# ETEST01.net
KiCad netlist of a schematic drawn in EAGLE
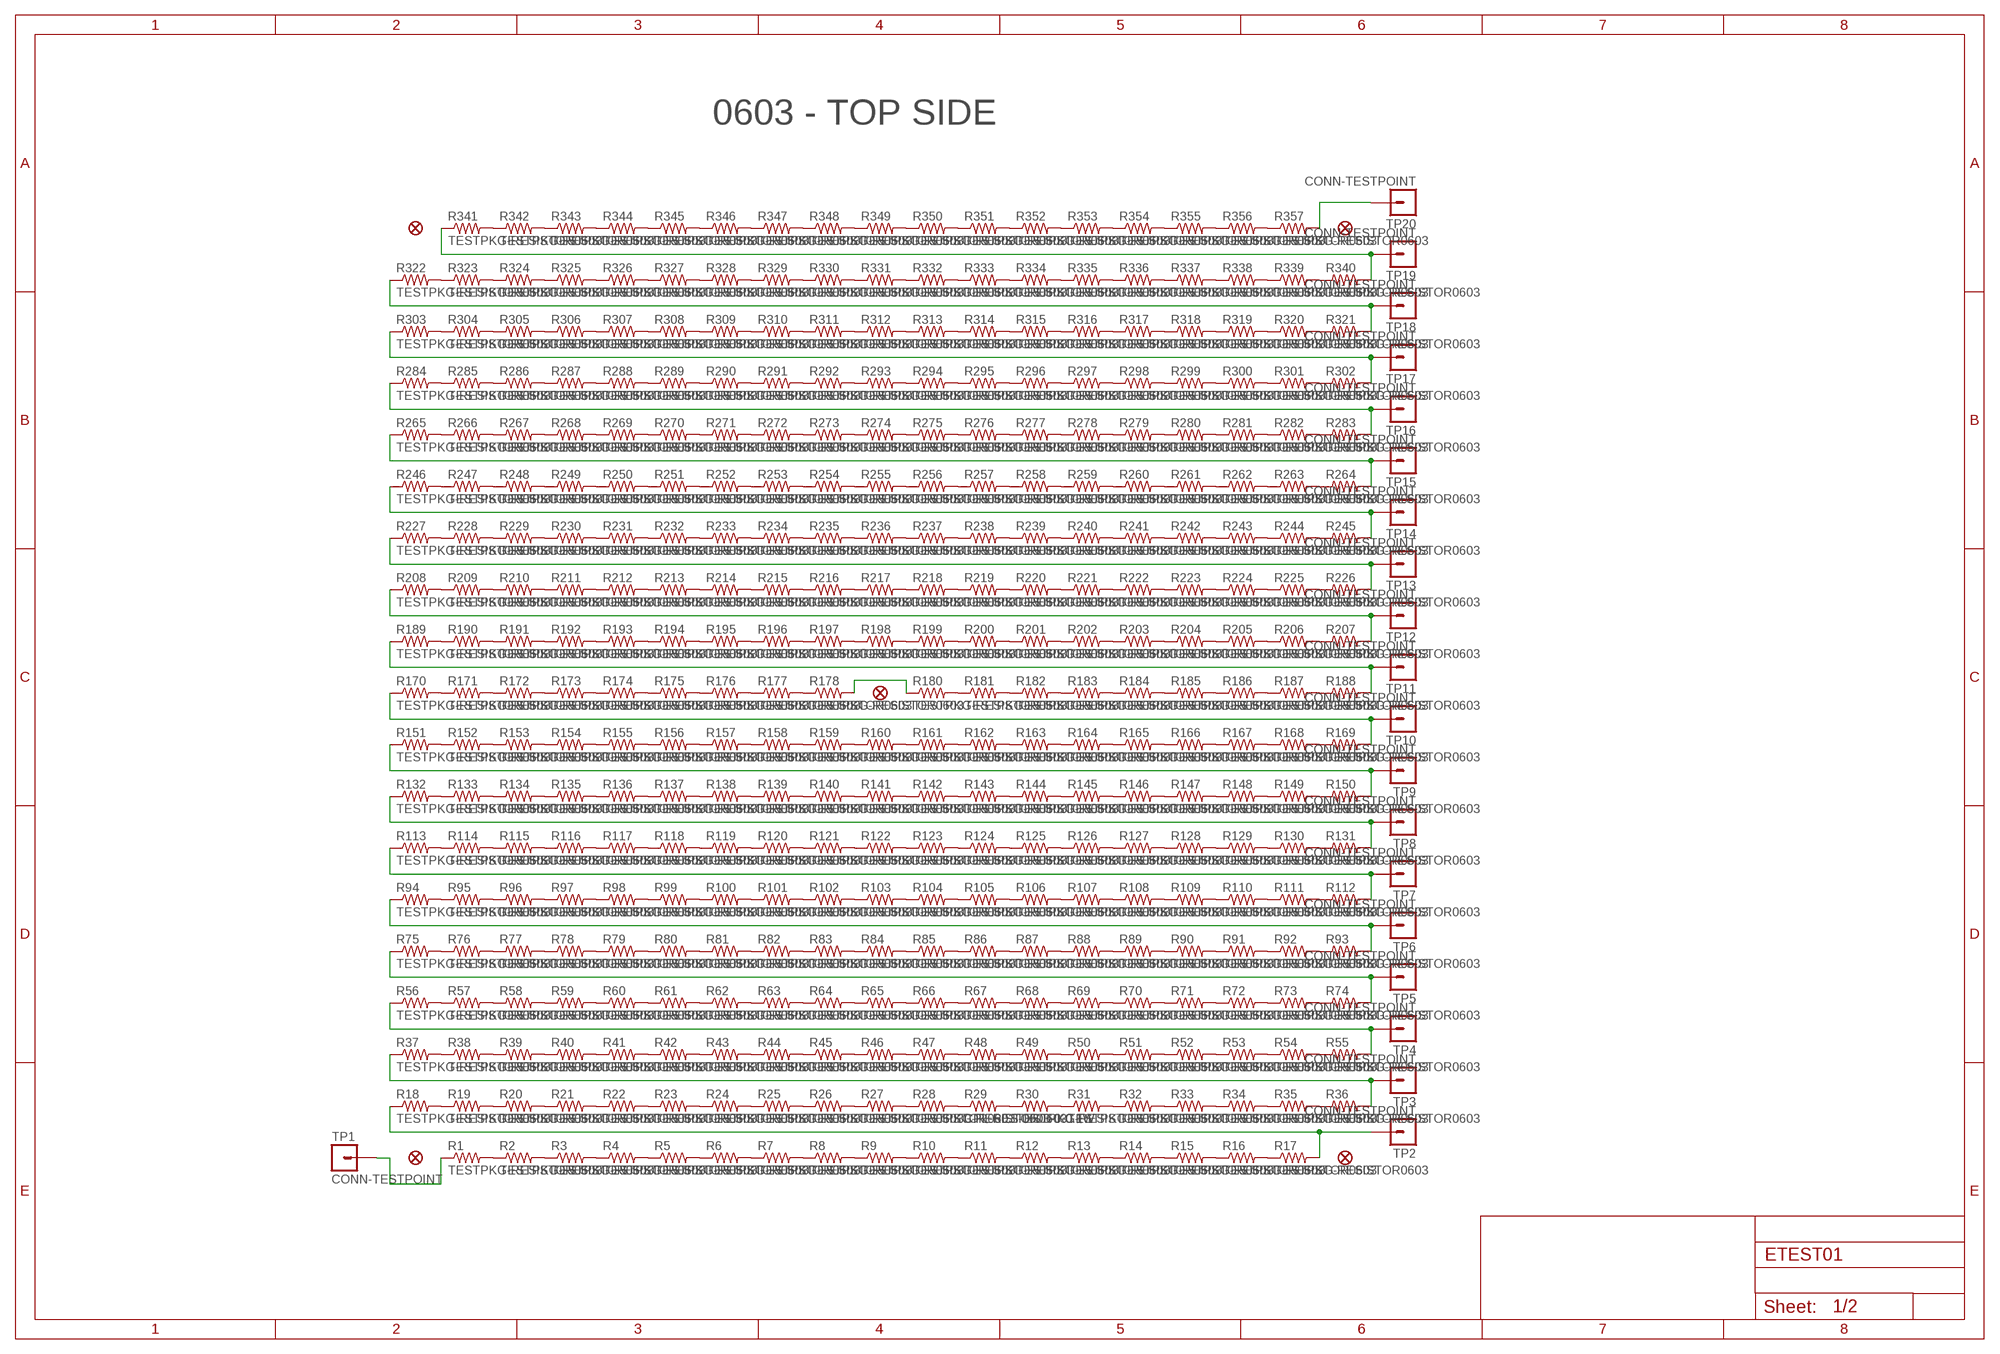
[diagram p0: schematic, sheet 1]
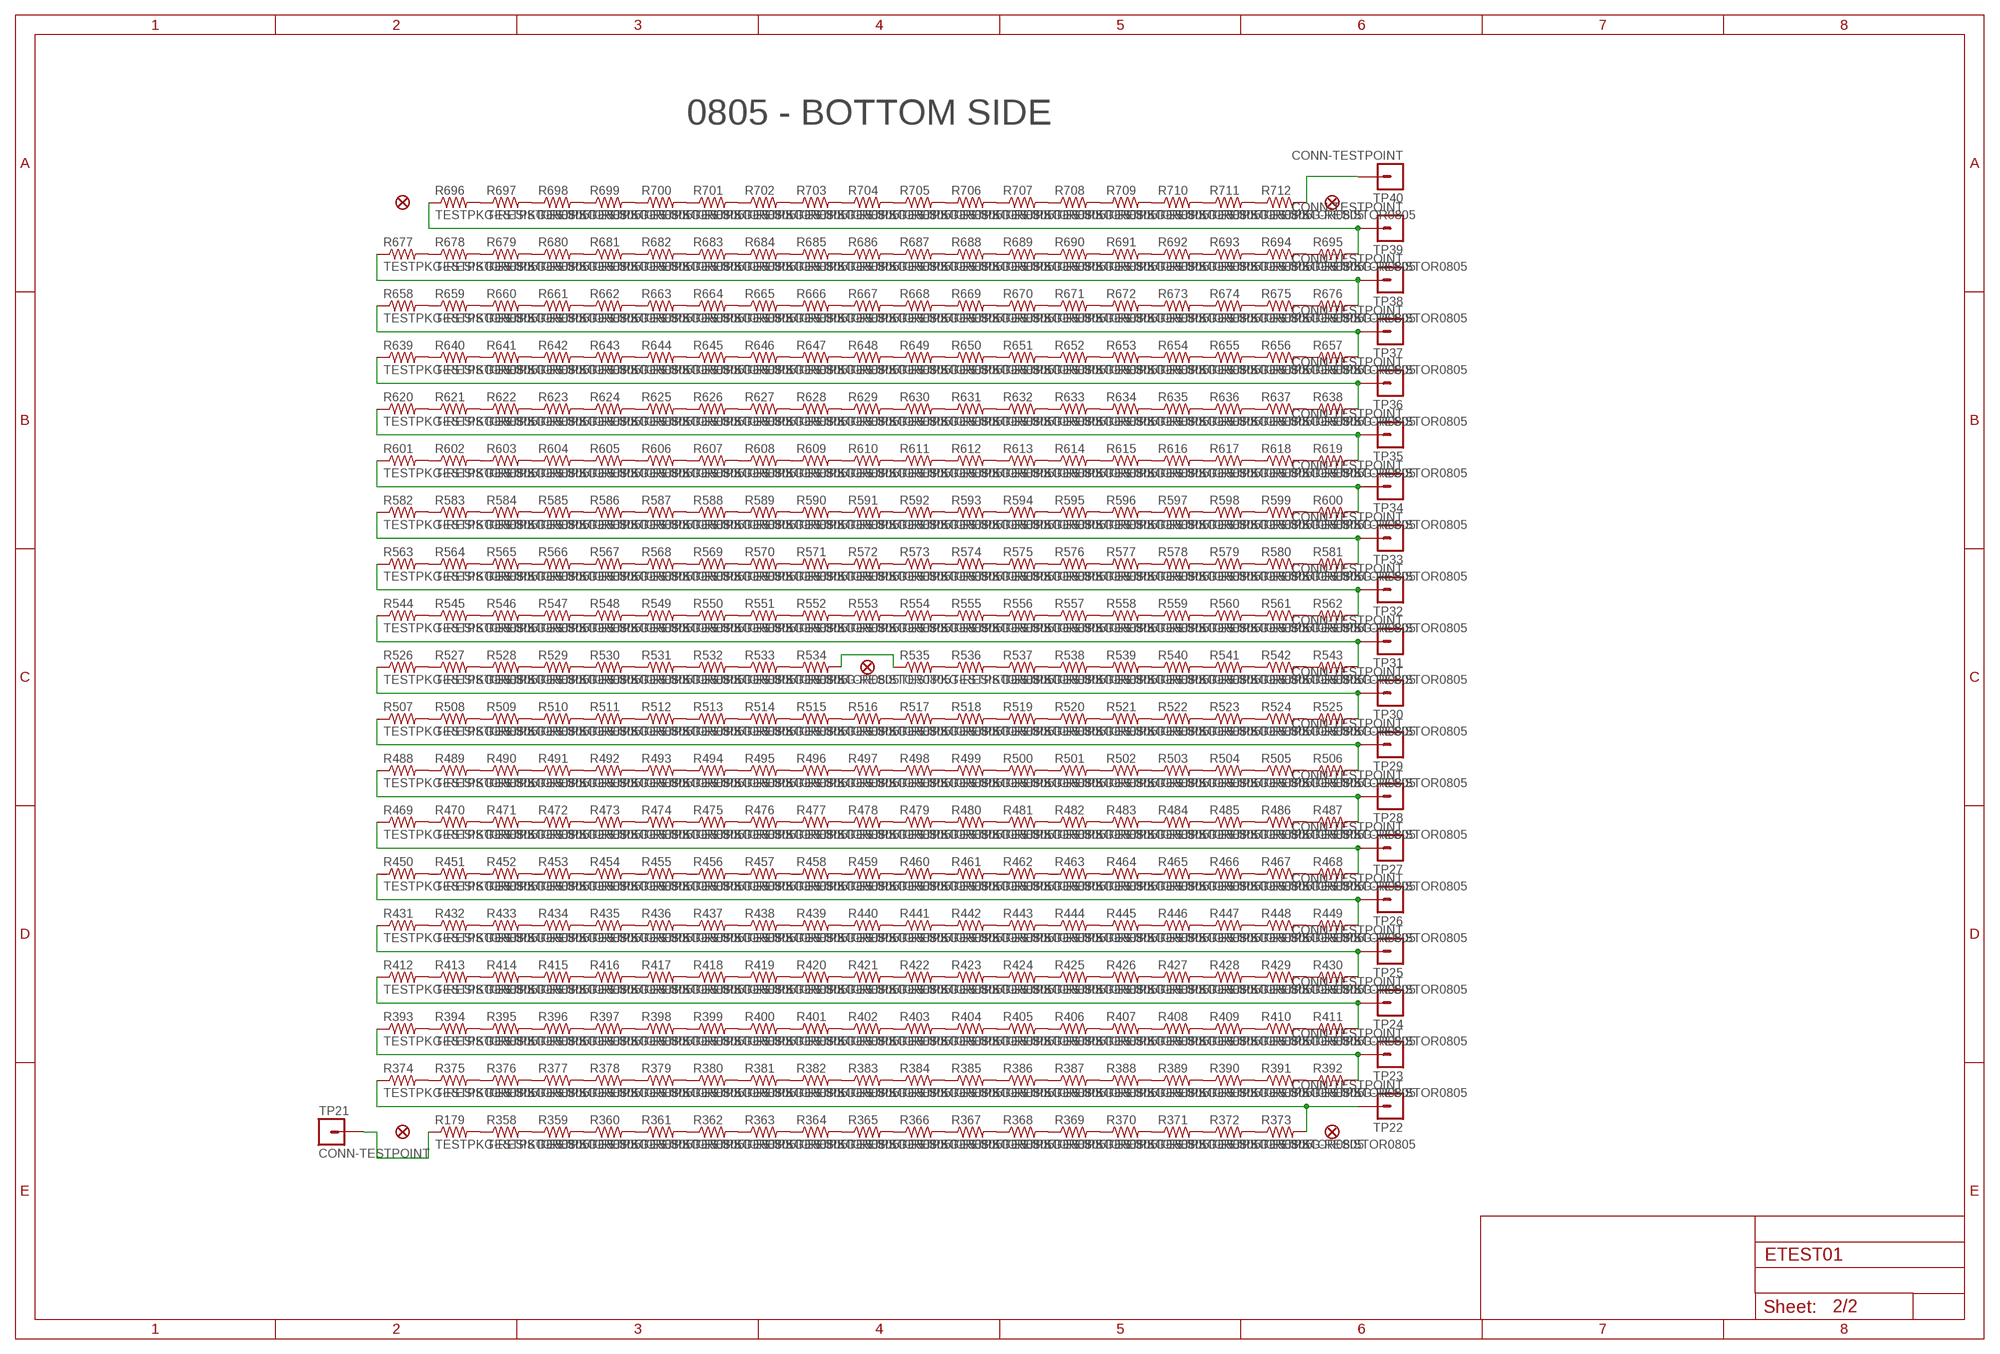
[diagram p1: schematic, sheet 2]

(export (version "E")
  (design (tool "Eeschema 10.0.6"))
  (components
    (comp (ref "FID1")
      (value "FIDUCIAL")
      (footprint "eagle-import:FIDUCIAL")
      (libsource (lib "eagle-import") (part "FIDUCIAL"))
    )
    (comp (ref "FID2")
      (value "FIDUCIAL")
      (footprint "eagle-import:FIDUCIAL")
      (libsource (lib "eagle-import") (part "FIDUCIAL"))
    )
    (comp (ref "FID3")
      (value "FIDUCIAL")
      (footprint "eagle-import:FIDUCIAL")
      (libsource (lib "eagle-import") (part "FIDUCIAL"))
    )
    (comp (ref "FID4")
      (value "FIDUCIAL")
      (footprint "eagle-import:FIDUCIAL")
      (libsource (lib "eagle-import") (part "FIDUCIAL"))
    )
    (comp (ref "FID5")
      (value "FIDUCIAL")
      (footprint "eagle-import:FIDUCIAL")
      (libsource (lib "eagle-import") (part "FIDUCIAL"))
    )
    (comp (ref "R1")
      (value "TESTPKG-RESISTOR0603")
      (footprint "eagle-import:TESTPKG-R0603")
      (libsource (lib "eagle-import") (part "TESTPKG-RESISTOR0603"))
    )
    (comp (ref "R2")
      (value "TESTPKG-RESISTOR0603")
      (footprint "eagle-import:TESTPKG-R0603")
      (libsource (lib "eagle-import") (part "TESTPKG-RESISTOR0603"))
    )
    (comp (ref "R3")
      (value "TESTPKG-RESISTOR0603")
      (footprint "eagle-import:TESTPKG-R0603")
      (libsource (lib "eagle-import") (part "TESTPKG-RESISTOR0603"))
    )
    (comp (ref "R4")
      (value "TESTPKG-RESISTOR0603")
      (footprint "eagle-import:TESTPKG-R0603")
      (libsource (lib "eagle-import") (part "TESTPKG-RESISTOR0603"))
    )
    (comp (ref "R5")
      (value "TESTPKG-RESISTOR0603")
      (footprint "eagle-import:TESTPKG-R0603")
      (libsource (lib "eagle-import") (part "TESTPKG-RESISTOR0603"))
    )
    (comp (ref "R6")
      (value "TESTPKG-RESISTOR0603")
      (footprint "eagle-import:TESTPKG-R0603")
      (libsource (lib "eagle-import") (part "TESTPKG-RESISTOR0603"))
    )
    (comp (ref "R7")
      (value "TESTPKG-RESISTOR0603")
      (footprint "eagle-import:TESTPKG-R0603")
      (libsource (lib "eagle-import") (part "TESTPKG-RESISTOR0603"))
    )
    (comp (ref "R8")
      (value "TESTPKG-RESISTOR0603")
      (footprint "eagle-import:TESTPKG-R0603")
      (libsource (lib "eagle-import") (part "TESTPKG-RESISTOR0603"))
    )
    (comp (ref "R9")
      (value "TESTPKG-RESISTOR0603")
      (footprint "eagle-import:TESTPKG-R0603")
      (libsource (lib "eagle-import") (part "TESTPKG-RESISTOR0603"))
    )
    (comp (ref "R10")
      (value "TESTPKG-RESISTOR0603")
      (footprint "eagle-import:TESTPKG-R0603")
      (libsource (lib "eagle-import") (part "TESTPKG-RESISTOR0603"))
    )
    (comp (ref "R11")
      (value "TESTPKG-RESISTOR0603")
      (footprint "eagle-import:TESTPKG-R0603")
      (libsource (lib "eagle-import") (part "TESTPKG-RESISTOR0603"))
    )
    (comp (ref "R12")
      (value "TESTPKG-RESISTOR0603")
      (footprint "eagle-import:TESTPKG-R0603")
      (libsource (lib "eagle-import") (part "TESTPKG-RESISTOR0603"))
    )
    (comp (ref "R13")
      (value "TESTPKG-RESISTOR0603")
      (footprint "eagle-import:TESTPKG-R0603")
      (libsource (lib "eagle-import") (part "TESTPKG-RESISTOR0603"))
    )
    (comp (ref "R14")
      (value "TESTPKG-RESISTOR0603")
      (footprint "eagle-import:TESTPKG-R0603")
      (libsource (lib "eagle-import") (part "TESTPKG-RESISTOR0603"))
    )
    (comp (ref "R15")
      (value "TESTPKG-RESISTOR0603")
      (footprint "eagle-import:TESTPKG-R0603")
      (libsource (lib "eagle-import") (part "TESTPKG-RESISTOR0603"))
    )
    (comp (ref "R16")
      (value "TESTPKG-RESISTOR0603")
      (footprint "eagle-import:TESTPKG-R0603")
      (libsource (lib "eagle-import") (part "TESTPKG-RESISTOR0603"))
    )
    (comp (ref "R17")
      (value "TESTPKG-RESISTOR0603")
      (footprint "eagle-import:TESTPKG-R0603")
      (libsource (lib "eagle-import") (part "TESTPKG-RESISTOR0603"))
    )
    (comp (ref "R18")
      (value "TESTPKG-RESISTOR0603")
      (footprint "eagle-import:TESTPKG-R0603")
      (libsource (lib "eagle-import") (part "TESTPKG-RESISTOR0603"))
    )
    (comp (ref "R19")
      (value "TESTPKG-RESISTOR0603")
      (footprint "eagle-import:TESTPKG-R0603")
      (libsource (lib "eagle-import") (part "TESTPKG-RESISTOR0603"))
    )
    (comp (ref "R20")
      (value "TESTPKG-RESISTOR0603")
      (footprint "eagle-import:TESTPKG-R0603")
      (libsource (lib "eagle-import") (part "TESTPKG-RESISTOR0603"))
    )
    (comp (ref "R21")
      (value "TESTPKG-RESISTOR0603")
      (footprint "eagle-import:TESTPKG-R0603")
      (libsource (lib "eagle-import") (part "TESTPKG-RESISTOR0603"))
    )
    (comp (ref "R22")
      (value "TESTPKG-RESISTOR0603")
      (footprint "eagle-import:TESTPKG-R0603")
      (libsource (lib "eagle-import") (part "TESTPKG-RESISTOR0603"))
    )
    (comp (ref "R23")
      (value "TESTPKG-RESISTOR0603")
      (footprint "eagle-import:TESTPKG-R0603")
      (libsource (lib "eagle-import") (part "TESTPKG-RESISTOR0603"))
    )
    (comp (ref "R24")
      (value "TESTPKG-RESISTOR0603")
      (footprint "eagle-import:TESTPKG-R0603")
      (libsource (lib "eagle-import") (part "TESTPKG-RESISTOR0603"))
    )
    (comp (ref "R25")
      (value "TESTPKG-RESISTOR0603")
      (footprint "eagle-import:TESTPKG-R0603")
      (libsource (lib "eagle-import") (part "TESTPKG-RESISTOR0603"))
    )
    (comp (ref "R26")
      (value "TESTPKG-RESISTOR0603")
      (footprint "eagle-import:TESTPKG-R0603")
      (libsource (lib "eagle-import") (part "TESTPKG-RESISTOR0603"))
    )
    (comp (ref "R27")
      (value "TESTPKG-RESISTOR0603")
      (footprint "eagle-import:TESTPKG-R0603")
      (libsource (lib "eagle-import") (part "TESTPKG-RESISTOR0603"))
    )
    (comp (ref "R28")
      (value "TESTPKG-RESISTOR0603")
      (footprint "eagle-import:TESTPKG-R0603")
      (libsource (lib "eagle-import") (part "TESTPKG-RESISTOR0603"))
    )
    (comp (ref "R29")
      (value "CPL-RES-0603-0-0.1W")
      (footprint "eagle-import:R0603")
      (libsource (lib "eagle-import") (part "CPL-RES-0603-0-0.1W"))
    )
    (comp (ref "R30")
      (value "TESTPKG-RESISTOR0603")
      (footprint "eagle-import:TESTPKG-R0603")
      (libsource (lib "eagle-import") (part "TESTPKG-RESISTOR0603"))
    )
    (comp (ref "R31")
      (value "TESTPKG-RESISTOR0603")
      (footprint "eagle-import:TESTPKG-R0603")
      (libsource (lib "eagle-import") (part "TESTPKG-RESISTOR0603"))
    )
    (comp (ref "R32")
      (value "TESTPKG-RESISTOR0603")
      (footprint "eagle-import:TESTPKG-R0603")
      (libsource (lib "eagle-import") (part "TESTPKG-RESISTOR0603"))
    )
    (comp (ref "R33")
      (value "TESTPKG-RESISTOR0603")
      (footprint "eagle-import:TESTPKG-R0603")
      (libsource (lib "eagle-import") (part "TESTPKG-RESISTOR0603"))
    )
    (comp (ref "R34")
      (value "TESTPKG-RESISTOR0603")
      (footprint "eagle-import:TESTPKG-R0603")
      (libsource (lib "eagle-import") (part "TESTPKG-RESISTOR0603"))
    )
    (comp (ref "R35")
      (value "TESTPKG-RESISTOR0603")
      (footprint "eagle-import:TESTPKG-R0603")
      (libsource (lib "eagle-import") (part "TESTPKG-RESISTOR0603"))
    )
    (comp (ref "R36")
      (value "TESTPKG-RESISTOR0603")
      (footprint "eagle-import:TESTPKG-R0603")
      (libsource (lib "eagle-import") (part "TESTPKG-RESISTOR0603"))
    )
    (comp (ref "R37")
      (value "TESTPKG-RESISTOR0603")
      (footprint "eagle-import:TESTPKG-R0603")
      (libsource (lib "eagle-import") (part "TESTPKG-RESISTOR0603"))
    )
    (comp (ref "R38")
      (value "TESTPKG-RESISTOR0603")
      (footprint "eagle-import:TESTPKG-R0603")
      (libsource (lib "eagle-import") (part "TESTPKG-RESISTOR0603"))
    )
    (comp (ref "R39")
      (value "TESTPKG-RESISTOR0603")
      (footprint "eagle-import:TESTPKG-R0603")
      (libsource (lib "eagle-import") (part "TESTPKG-RESISTOR0603"))
    )
    (comp (ref "R40")
      (value "TESTPKG-RESISTOR0603")
      (footprint "eagle-import:TESTPKG-R0603")
      (libsource (lib "eagle-import") (part "TESTPKG-RESISTOR0603"))
    )
    (comp (ref "R41")
      (value "TESTPKG-RESISTOR0603")
      (footprint "eagle-import:TESTPKG-R0603")
      (libsource (lib "eagle-import") (part "TESTPKG-RESISTOR0603"))
    )
    (comp (ref "R42")
      (value "TESTPKG-RESISTOR0603")
      (footprint "eagle-import:TESTPKG-R0603")
      (libsource (lib "eagle-import") (part "TESTPKG-RESISTOR0603"))
    )
    (comp (ref "R43")
      (value "TESTPKG-RESISTOR0603")
      (footprint "eagle-import:TESTPKG-R0603")
      (libsource (lib "eagle-import") (part "TESTPKG-RESISTOR0603"))
    )
    (comp (ref "R44")
      (value "TESTPKG-RESISTOR0603")
      (footprint "eagle-import:TESTPKG-R0603")
      (libsource (lib "eagle-import") (part "TESTPKG-RESISTOR0603"))
    )
    (comp (ref "R45")
      (value "TESTPKG-RESISTOR0603")
      (footprint "eagle-import:TESTPKG-R0603")
      (libsource (lib "eagle-import") (part "TESTPKG-RESISTOR0603"))
    )
    (comp (ref "R46")
      (value "TESTPKG-RESISTOR0603")
      (footprint "eagle-import:TESTPKG-R0603")
      (libsource (lib "eagle-import") (part "TESTPKG-RESISTOR0603"))
    )
    (comp (ref "R47")
      (value "TESTPKG-RESISTOR0603")
      (footprint "eagle-import:TESTPKG-R0603")
      (libsource (lib "eagle-import") (part "TESTPKG-RESISTOR0603"))
    )
    (comp (ref "R48")
      (value "TESTPKG-RESISTOR0603")
      (footprint "eagle-import:TESTPKG-R0603")
      (libsource (lib "eagle-import") (part "TESTPKG-RESISTOR0603"))
    )
    (comp (ref "R49")
      (value "TESTPKG-RESISTOR0603")
      (footprint "eagle-import:TESTPKG-R0603")
      (libsource (lib "eagle-import") (part "TESTPKG-RESISTOR0603"))
    )
    (comp (ref "R50")
      (value "TESTPKG-RESISTOR0603")
      (footprint "eagle-import:TESTPKG-R0603")
      (libsource (lib "eagle-import") (part "TESTPKG-RESISTOR0603"))
    )
    (comp (ref "R51")
      (value "TESTPKG-RESISTOR0603")
      (footprint "eagle-import:TESTPKG-R0603")
      (libsource (lib "eagle-import") (part "TESTPKG-RESISTOR0603"))
    )
    (comp (ref "R52")
      (value "TESTPKG-RESISTOR0603")
      (footprint "eagle-import:TESTPKG-R0603")
      (libsource (lib "eagle-import") (part "TESTPKG-RESISTOR0603"))
    )
    (comp (ref "R53")
      (value "TESTPKG-RESISTOR0603")
      (footprint "eagle-import:TESTPKG-R0603")
      (libsource (lib "eagle-import") (part "TESTPKG-RESISTOR0603"))
    )
    (comp (ref "R54")
      (value "TESTPKG-RESISTOR0603")
      (footprint "eagle-import:TESTPKG-R0603")
      (libsource (lib "eagle-import") (part "TESTPKG-RESISTOR0603"))
    )
    (comp (ref "R55")
      (value "TESTPKG-RESISTOR0603")
      (footprint "eagle-import:TESTPKG-R0603")
      (libsource (lib "eagle-import") (part "TESTPKG-RESISTOR0603"))
    )
    (comp (ref "R56")
      (value "TESTPKG-RESISTOR0603")
      (footprint "eagle-import:TESTPKG-R0603")
      (libsource (lib "eagle-import") (part "TESTPKG-RESISTOR0603"))
    )
    (comp (ref "R57")
      (value "TESTPKG-RESISTOR0603")
      (footprint "eagle-import:TESTPKG-R0603")
      (libsource (lib "eagle-import") (part "TESTPKG-RESISTOR0603"))
    )
    (comp (ref "R58")
      (value "TESTPKG-RESISTOR0603")
      (footprint "eagle-import:TESTPKG-R0603")
      (libsource (lib "eagle-import") (part "TESTPKG-RESISTOR0603"))
    )
    (comp (ref "R59")
      (value "TESTPKG-RESISTOR0603")
      (footprint "eagle-import:TESTPKG-R0603")
      (libsource (lib "eagle-import") (part "TESTPKG-RESISTOR0603"))
    )
    (comp (ref "R60")
      (value "TESTPKG-RESISTOR0603")
      (footprint "eagle-import:TESTPKG-R0603")
      (libsource (lib "eagle-import") (part "TESTPKG-RESISTOR0603"))
    )
    (comp (ref "R61")
      (value "TESTPKG-RESISTOR0603")
      (footprint "eagle-import:TESTPKG-R0603")
      (libsource (lib "eagle-import") (part "TESTPKG-RESISTOR0603"))
    )
    (comp (ref "R62")
      (value "TESTPKG-RESISTOR0603")
      (footprint "eagle-import:TESTPKG-R0603")
      (libsource (lib "eagle-import") (part "TESTPKG-RESISTOR0603"))
    )
    (comp (ref "R63")
      (value "TESTPKG-RESISTOR0603")
      (footprint "eagle-import:TESTPKG-R0603")
      (libsource (lib "eagle-import") (part "TESTPKG-RESISTOR0603"))
    )
    (comp (ref "R64")
      (value "TESTPKG-RESISTOR0603")
      (footprint "eagle-import:TESTPKG-R0603")
      (libsource (lib "eagle-import") (part "TESTPKG-RESISTOR0603"))
    )
    (comp (ref "R65")
      (value "TESTPKG-RESISTOR0603")
      (footprint "eagle-import:TESTPKG-R0603")
      (libsource (lib "eagle-import") (part "TESTPKG-RESISTOR0603"))
    )
    (comp (ref "R66")
      (value "TESTPKG-RESISTOR0603")
      (footprint "eagle-import:TESTPKG-R0603")
      (libsource (lib "eagle-import") (part "TESTPKG-RESISTOR0603"))
    )
    (comp (ref "R67")
      (value "TESTPKG-RESISTOR0603")
      (footprint "eagle-import:TESTPKG-R0603")
      (libsource (lib "eagle-import") (part "TESTPKG-RESISTOR0603"))
    )
    (comp (ref "R68")
      (value "TESTPKG-RESISTOR0603")
      (footprint "eagle-import:TESTPKG-R0603")
      (libsource (lib "eagle-import") (part "TESTPKG-RESISTOR0603"))
    )
    (comp (ref "R69")
      (value "TESTPKG-RESISTOR0603")
      (footprint "eagle-import:TESTPKG-R0603")
      (libsource (lib "eagle-import") (part "TESTPKG-RESISTOR0603"))
    )
    (comp (ref "R70")
      (value "TESTPKG-RESISTOR0603")
      (footprint "eagle-import:TESTPKG-R0603")
      (libsource (lib "eagle-import") (part "TESTPKG-RESISTOR0603"))
    )
    (comp (ref "R71")
      (value "TESTPKG-RESISTOR0603")
      (footprint "eagle-import:TESTPKG-R0603")
      (libsource (lib "eagle-import") (part "TESTPKG-RESISTOR0603"))
    )
    (comp (ref "R72")
      (value "TESTPKG-RESISTOR0603")
      (footprint "eagle-import:TESTPKG-R0603")
      (libsource (lib "eagle-import") (part "TESTPKG-RESISTOR0603"))
    )
    (comp (ref "R73")
      (value "TESTPKG-RESISTOR0603")
      (footprint "eagle-import:TESTPKG-R0603")
      (libsource (lib "eagle-import") (part "TESTPKG-RESISTOR0603"))
    )
    (comp (ref "R74")
      (value "TESTPKG-RESISTOR0603")
      (footprint "eagle-import:TESTPKG-R0603")
      (libsource (lib "eagle-import") (part "TESTPKG-RESISTOR0603"))
    )
    (comp (ref "R75")
      (value "TESTPKG-RESISTOR0603")
      (footprint "eagle-import:TESTPKG-R0603")
      (libsource (lib "eagle-import") (part "TESTPKG-RESISTOR0603"))
    )
    (comp (ref "R76")
      (value "TESTPKG-RESISTOR0603")
      (footprint "eagle-import:TESTPKG-R0603")
      (libsource (lib "eagle-import") (part "TESTPKG-RESISTOR0603"))
    )
    (comp (ref "R77")
      (value "TESTPKG-RESISTOR0603")
      (footprint "eagle-import:TESTPKG-R0603")
      (libsource (lib "eagle-import") (part "TESTPKG-RESISTOR0603"))
    )
    (comp (ref "R78")
      (value "TESTPKG-RESISTOR0603")
      (footprint "eagle-import:TESTPKG-R0603")
      (libsource (lib "eagle-import") (part "TESTPKG-RESISTOR0603"))
    )
    (comp (ref "R79")
      (value "TESTPKG-RESISTOR0603")
      (footprint "eagle-import:TESTPKG-R0603")
      (libsource (lib "eagle-import") (part "TESTPKG-RESISTOR0603"))
    )
    (comp (ref "R80")
      (value "TESTPKG-RESISTOR0603")
      (footprint "eagle-import:TESTPKG-R0603")
      (libsource (lib "eagle-import") (part "TESTPKG-RESISTOR0603"))
    )
    (comp (ref "R81")
      (value "TESTPKG-RESISTOR0603")
      (footprint "eagle-import:TESTPKG-R0603")
      (libsource (lib "eagle-import") (part "TESTPKG-RESISTOR0603"))
    )
    (comp (ref "R82")
      (value "TESTPKG-RESISTOR0603")
      (footprint "eagle-import:TESTPKG-R0603")
      (libsource (lib "eagle-import") (part "TESTPKG-RESISTOR0603"))
    )
    (comp (ref "R83")
      (value "TESTPKG-RESISTOR0603")
      (footprint "eagle-import:TESTPKG-R0603")
      (libsource (lib "eagle-import") (part "TESTPKG-RESISTOR0603"))
    )
    (comp (ref "R84")
      (value "TESTPKG-RESISTOR0603")
      (footprint "eagle-import:TESTPKG-R0603")
      (libsource (lib "eagle-import") (part "TESTPKG-RESISTOR0603"))
    )
    (comp (ref "R85")
      (value "TESTPKG-RESISTOR0603")
      (footprint "eagle-import:TESTPKG-R0603")
      (libsource (lib "eagle-import") (part "TESTPKG-RESISTOR0603"))
    )
    (comp (ref "R86")
      (value "TESTPKG-RESISTOR0603")
      (footprint "eagle-import:TESTPKG-R0603")
      (libsource (lib "eagle-import") (part "TESTPKG-RESISTOR0603"))
    )
    (comp (ref "R87")
      (value "TESTPKG-RESISTOR0603")
      (footprint "eagle-import:TESTPKG-R0603")
      (libsource (lib "eagle-import") (part "TESTPKG-RESISTOR0603"))
    )
    (comp (ref "R88")
      (value "TESTPKG-RESISTOR0603")
      (footprint "eagle-import:TESTPKG-R0603")
      (libsource (lib "eagle-import") (part "TESTPKG-RESISTOR0603"))
    )
    (comp (ref "R89")
      (value "TESTPKG-RESISTOR0603")
      (footprint "eagle-import:TESTPKG-R0603")
      (libsource (lib "eagle-import") (part "TESTPKG-RESISTOR0603"))
    )
    (comp (ref "R90")
      (value "TESTPKG-RESISTOR0603")
      (footprint "eagle-import:TESTPKG-R0603")
      (libsource (lib "eagle-import") (part "TESTPKG-RESISTOR0603"))
    )
    (comp (ref "R91")
      (value "TESTPKG-RESISTOR0603")
      (footprint "eagle-import:TESTPKG-R0603")
      (libsource (lib "eagle-import") (part "TESTPKG-RESISTOR0603"))
    )
    (comp (ref "R92")
      (value "TESTPKG-RESISTOR0603")
      (footprint "eagle-import:TESTPKG-R0603")
      (libsource (lib "eagle-import") (part "TESTPKG-RESISTOR0603"))
    )
    (comp (ref "R93")
      (value "TESTPKG-RESISTOR0603")
      (footprint "eagle-import:TESTPKG-R0603")
      (libsource (lib "eagle-import") (part "TESTPKG-RESISTOR0603"))
    )
    (comp (ref "R94")
      (value "TESTPKG-RESISTOR0603")
      (footprint "eagle-import:TESTPKG-R0603")
      (libsource (lib "eagle-import") (part "TESTPKG-RESISTOR0603"))
    )
    (comp (ref "R95")
      (value "TESTPKG-RESISTOR0603")
      (footprint "eagle-import:TESTPKG-R0603")
      (libsource (lib "eagle-import") (part "TESTPKG-RESISTOR0603"))
    )
    (comp (ref "R96")
      (value "TESTPKG-RESISTOR0603")
      (footprint "eagle-import:TESTPKG-R0603")
      (libsource (lib "eagle-import") (part "TESTPKG-RESISTOR0603"))
    )
    (comp (ref "R97")
      (value "TESTPKG-RESISTOR0603")
      (footprint "eagle-import:TESTPKG-R0603")
      (libsource (lib "eagle-import") (part "TESTPKG-RESISTOR0603"))
    )
    (comp (ref "R98")
      (value "TESTPKG-RESISTOR0603")
      (footprint "eagle-import:TESTPKG-R0603")
      (libsource (lib "eagle-import") (part "TESTPKG-RESISTOR0603"))
    )
    (comp (ref "R99")
      (value "TESTPKG-RESISTOR0603")
      (footprint "eagle-import:TESTPKG-R0603")
      (libsource (lib "eagle-import") (part "TESTPKG-RESISTOR0603"))
    )
    (comp (ref "R100")
      (value "TESTPKG-RESISTOR0603")
      (footprint "eagle-import:TESTPKG-R0603")
      (libsource (lib "eagle-import") (part "TESTPKG-RESISTOR0603"))
    )
    (comp (ref "R101")
      (value "TESTPKG-RESISTOR0603")
      (footprint "eagle-import:TESTPKG-R0603")
      (libsource (lib "eagle-import") (part "TESTPKG-RESISTOR0603"))
    )
    (comp (ref "R102")
      (value "TESTPKG-RESISTOR0603")
      (footprint "eagle-import:TESTPKG-R0603")
      (libsource (lib "eagle-import") (part "TESTPKG-RESISTOR0603"))
    )
    (comp (ref "R103")
      (value "TESTPKG-RESISTOR0603")
      (footprint "eagle-import:TESTPKG-R0603")
      (libsource (lib "eagle-import") (part "TESTPKG-RESISTOR0603"))
    )
    (comp (ref "R104")
      (value "TESTPKG-RESISTOR0603")
      (footprint "eagle-import:TESTPKG-R0603")
      (libsource (lib "eagle-import") (part "TESTPKG-RESISTOR0603"))
    )
    (comp (ref "R105")
      (value "TESTPKG-RESISTOR0603")
      (footprint "eagle-import:TESTPKG-R0603")
      (libsource (lib "eagle-import") (part "TESTPKG-RESISTOR0603"))
    )
    (comp (ref "R106")
      (value "TESTPKG-RESISTOR0603")
      (footprint "eagle-import:TESTPKG-R0603")
      (libsource (lib "eagle-import") (part "TESTPKG-RESISTOR0603"))
    )
    (comp (ref "R107")
      (value "TESTPKG-RESISTOR0603")
      (footprint "eagle-import:TESTPKG-R0603")
      (libsource (lib "eagle-import") (part "TESTPKG-RESISTOR0603"))
    )
    (comp (ref "R108")
      (value "TESTPKG-RESISTOR0603")
      (footprint "eagle-import:TESTPKG-R0603")
      (libsource (lib "eagle-import") (part "TESTPKG-RESISTOR0603"))
    )
    (comp (ref "R109")
      (value "TESTPKG-RESISTOR0603")
      (footprint "eagle-import:TESTPKG-R0603")
      (libsource (lib "eagle-import") (part "TESTPKG-RESISTOR0603"))
    )
    (comp (ref "R110")
      (value "TESTPKG-RESISTOR0603")
      (footprint "eagle-import:TESTPKG-R0603")
      (libsource (lib "eagle-import") (part "TESTPKG-RESISTOR0603"))
    )
    (comp (ref "R111")
      (value "TESTPKG-RESISTOR0603")
      (footprint "eagle-import:TESTPKG-R0603")
      (libsource (lib "eagle-import") (part "TESTPKG-RESISTOR0603"))
    )
    (comp (ref "R112")
      (value "TESTPKG-RESISTOR0603")
      (footprint "eagle-import:TESTPKG-R0603")
      (libsource (lib "eagle-import") (part "TESTPKG-RESISTOR0603"))
    )
    (comp (ref "R113")
      (value "TESTPKG-RESISTOR0603")
      (footprint "eagle-import:TESTPKG-R0603")
      (libsource (lib "eagle-import") (part "TESTPKG-RESISTOR0603"))
    )
    (comp (ref "R114")
      (value "TESTPKG-RESISTOR0603")
      (footprint "eagle-import:TESTPKG-R0603")
      (libsource (lib "eagle-import") (part "TESTPKG-RESISTOR0603"))
    )
    (comp (ref "R115")
      (value "TESTPKG-RESISTOR0603")
      (footprint "eagle-import:TESTPKG-R0603")
      (libsource (lib "eagle-import") (part "TESTPKG-RESISTOR0603"))
    )
    (comp (ref "R116")
      (value "TESTPKG-RESISTOR0603")
      (footprint "eagle-import:TESTPKG-R0603")
      (libsource (lib "eagle-import") (part "TESTPKG-RESISTOR0603"))
    )
    (comp (ref "R117")
      (value "TESTPKG-RESISTOR0603")
      (footprint "eagle-import:TESTPKG-R0603")
      (libsource (lib "eagle-import") (part "TESTPKG-RESISTOR0603"))
    )
    (comp (ref "R118")
      (value "TESTPKG-RESISTOR0603")
      (footprint "eagle-import:TESTPKG-R0603")
      (libsource (lib "eagle-import") (part "TESTPKG-RESISTOR0603"))
    )
    (comp (ref "R119")
      (value "TESTPKG-RESISTOR0603")
      (footprint "eagle-import:TESTPKG-R0603")
      (libsource (lib "eagle-import") (part "TESTPKG-RESISTOR0603"))
    )
    (comp (ref "R120")
      (value "TESTPKG-RESISTOR0603")
      (footprint "eagle-import:TESTPKG-R0603")
      (libsource (lib "eagle-import") (part "TESTPKG-RESISTOR0603"))
    )
    (comp (ref "R121")
      (value "TESTPKG-RESISTOR0603")
      (footprint "eagle-import:TESTPKG-R0603")
      (libsource (lib "eagle-import") (part "TESTPKG-RESISTOR0603"))
    )
    (comp (ref "R122")
      (value "TESTPKG-RESISTOR0603")
      (footprint "eagle-import:TESTPKG-R0603")
      (libsource (lib "eagle-import") (part "TESTPKG-RESISTOR0603"))
    )
    (comp (ref "R123")
      (value "TESTPKG-RESISTOR0603")
      (footprint "eagle-import:TESTPKG-R0603")
      (libsource (lib "eagle-import") (part "TESTPKG-RESISTOR0603"))
    )
    (comp (ref "R124")
      (value "TESTPKG-RESISTOR0603")
      (footprint "eagle-import:TESTPKG-R0603")
      (libsource (lib "eagle-import") (part "TESTPKG-RESISTOR0603"))
    )
    (comp (ref "R125")
      (value "TESTPKG-RESISTOR0603")
      (footprint "eagle-import:TESTPKG-R0603")
      (libsource (lib "eagle-import") (part "TESTPKG-RESISTOR0603"))
    )
    (comp (ref "R126")
      (value "TESTPKG-RESISTOR0603")
      (footprint "eagle-import:TESTPKG-R0603")
      (libsource (lib "eagle-import") (part "TESTPKG-RESISTOR0603"))
    )
    (comp (ref "R127")
      (value "TESTPKG-RESISTOR0603")
      (footprint "eagle-import:TESTPKG-R0603")
      (libsource (lib "eagle-import") (part "TESTPKG-RESISTOR0603"))
    )
    (comp (ref "R128")
      (value "TESTPKG-RESISTOR0603")
      (footprint "eagle-import:TESTPKG-R0603")
      (libsource (lib "eagle-import") (part "TESTPKG-RESISTOR0603"))
    )
    (comp (ref "R129")
      (value "TESTPKG-RESISTOR0603")
      (footprint "eagle-import:TESTPKG-R0603")
      (libsource (lib "eagle-import") (part "TESTPKG-RESISTOR0603"))
    )
    (comp (ref "R130")
      (value "TESTPKG-RESISTOR0603")
      (footprint "eagle-import:TESTPKG-R0603")
      (libsource (lib "eagle-import") (part "TESTPKG-RESISTOR0603"))
    )
    (comp (ref "R131")
      (value "TESTPKG-RESISTOR0603")
      (footprint "eagle-import:TESTPKG-R0603")
      (libsource (lib "eagle-import") (part "TESTPKG-RESISTOR0603"))
    )
    (comp (ref "R132")
      (value "TESTPKG-RESISTOR0603")
      (footprint "eagle-import:TESTPKG-R0603")
      (libsource (lib "eagle-import") (part "TESTPKG-RESISTOR0603"))
    )
    (comp (ref "R133")
      (value "TESTPKG-RESISTOR0603")
      (footprint "eagle-import:TESTPKG-R0603")
      (libsource (lib "eagle-import") (part "TESTPKG-RESISTOR0603"))
    )
    (comp (ref "R134")
      (value "TESTPKG-RESISTOR0603")
      (footprint "eagle-import:TESTPKG-R0603")
      (libsource (lib "eagle-import") (part "TESTPKG-RESISTOR0603"))
    )
    (comp (ref "R135")
      (value "TESTPKG-RESISTOR0603")
      (footprint "eagle-import:TESTPKG-R0603")
      (libsource (lib "eagle-import") (part "TESTPKG-RESISTOR0603"))
    )
    (comp (ref "R136")
      (value "TESTPKG-RESISTOR0603")
      (footprint "eagle-import:TESTPKG-R0603")
      (libsource (lib "eagle-import") (part "TESTPKG-RESISTOR0603"))
    )
    (comp (ref "R137")
      (value "TESTPKG-RESISTOR0603")
      (footprint "eagle-import:TESTPKG-R0603")
      (libsource (lib "eagle-import") (part "TESTPKG-RESISTOR0603"))
    )
    (comp (ref "R138")
      (value "TESTPKG-RESISTOR0603")
      (footprint "eagle-import:TESTPKG-R0603")
      (libsource (lib "eagle-import") (part "TESTPKG-RESISTOR0603"))
    )
    (comp (ref "R139")
      (value "TESTPKG-RESISTOR0603")
      (footprint "eagle-import:TESTPKG-R0603")
      (libsource (lib "eagle-import") (part "TESTPKG-RESISTOR0603"))
    )
    (comp (ref "R140")
      (value "TESTPKG-RESISTOR0603")
      (footprint "eagle-import:TESTPKG-R0603")
      (libsource (lib "eagle-import") (part "TESTPKG-RESISTOR0603"))
    )
    (comp (ref "R141")
      (value "TESTPKG-RESISTOR0603")
      (footprint "eagle-import:TESTPKG-R0603")
      (libsource (lib "eagle-import") (part "TESTPKG-RESISTOR0603"))
    )
    (comp (ref "R142")
      (value "TESTPKG-RESISTOR0603")
      (footprint "eagle-import:TESTPKG-R0603")
      (libsource (lib "eagle-import") (part "TESTPKG-RESISTOR0603"))
    )
    (comp (ref "R143")
      (value "TESTPKG-RESISTOR0603")
      (footprint "eagle-import:TESTPKG-R0603")
      (libsource (lib "eagle-import") (part "TESTPKG-RESISTOR0603"))
    )
    (comp (ref "R144")
      (value "TESTPKG-RESISTOR0603")
      (footprint "eagle-import:TESTPKG-R0603")
      (libsource (lib "eagle-import") (part "TESTPKG-RESISTOR0603"))
    )
    (comp (ref "R145")
      (value "TESTPKG-RESISTOR0603")
      (footprint "eagle-import:TESTPKG-R0603")
      (libsource (lib "eagle-import") (part "TESTPKG-RESISTOR0603"))
    )
    (comp (ref "R146")
      (value "TESTPKG-RESISTOR0603")
      (footprint "eagle-import:TESTPKG-R0603")
      (libsource (lib "eagle-import") (part "TESTPKG-RESISTOR0603"))
    )
    (comp (ref "R147")
      (value "TESTPKG-RESISTOR0603")
      (footprint "eagle-import:TESTPKG-R0603")
      (libsource (lib "eagle-import") (part "TESTPKG-RESISTOR0603"))
    )
    (comp (ref "R148")
      (value "TESTPKG-RESISTOR0603")
      (footprint "eagle-import:TESTPKG-R0603")
      (libsource (lib "eagle-import") (part "TESTPKG-RESISTOR0603"))
    )
    (comp (ref "R149")
      (value "TESTPKG-RESISTOR0603")
      (footprint "eagle-import:TESTPKG-R0603")
      (libsource (lib "eagle-import") (part "TESTPKG-RESISTOR0603"))
    )
    (comp (ref "R150")
      (value "TESTPKG-RESISTOR0603")
      (footprint "eagle-import:TESTPKG-R0603")
      (libsource (lib "eagle-import") (part "TESTPKG-RESISTOR0603"))
    )
    (comp (ref "R151")
      (value "TESTPKG-RESISTOR0603")
      (footprint "eagle-import:TESTPKG-R0603")
      (libsource (lib "eagle-import") (part "TESTPKG-RESISTOR0603"))
    )
    (comp (ref "R152")
      (value "TESTPKG-RESISTOR0603")
      (footprint "eagle-import:TESTPKG-R0603")
      (libsource (lib "eagle-import") (part "TESTPKG-RESISTOR0603"))
    )
    (comp (ref "R153")
      (value "TESTPKG-RESISTOR0603")
      (footprint "eagle-import:TESTPKG-R0603")
      (libsource (lib "eagle-import") (part "TESTPKG-RESISTOR0603"))
    )
    (comp (ref "R154")
      (value "TESTPKG-RESISTOR0603")
      (footprint "eagle-import:TESTPKG-R0603")
      (libsource (lib "eagle-import") (part "TESTPKG-RESISTOR0603"))
    )
    (comp (ref "R155")
      (value "TESTPKG-RESISTOR0603")
      (footprint "eagle-import:TESTPKG-R0603")
      (libsource (lib "eagle-import") (part "TESTPKG-RESISTOR0603"))
    )
    (comp (ref "R156")
      (value "TESTPKG-RESISTOR0603")
      (footprint "eagle-import:TESTPKG-R0603")
      (libsource (lib "eagle-import") (part "TESTPKG-RESISTOR0603"))
    )
    (comp (ref "R157")
      (value "TESTPKG-RESISTOR0603")
      (footprint "eagle-import:TESTPKG-R0603")
      (libsource (lib "eagle-import") (part "TESTPKG-RESISTOR0603"))
    )
    (comp (ref "R158")
      (value "TESTPKG-RESISTOR0603")
      (footprint "eagle-import:TESTPKG-R0603")
      (libsource (lib "eagle-import") (part "TESTPKG-RESISTOR0603"))
    )
    (comp (ref "R159")
      (value "TESTPKG-RESISTOR0603")
      (footprint "eagle-import:TESTPKG-R0603")
      (libsource (lib "eagle-import") (part "TESTPKG-RESISTOR0603"))
    )
    (comp (ref "R160")
      (value "TESTPKG-RESISTOR0603")
      (footprint "eagle-import:TESTPKG-R0603")
      (libsource (lib "eagle-import") (part "TESTPKG-RESISTOR0603"))
    )
    (comp (ref "R161")
      (value "TESTPKG-RESISTOR0603")
      (footprint "eagle-import:TESTPKG-R0603")
      (libsource (lib "eagle-import") (part "TESTPKG-RESISTOR0603"))
    )
    (comp (ref "R162")
      (value "TESTPKG-RESISTOR0603")
      (footprint "eagle-import:TESTPKG-R0603")
      (libsource (lib "eagle-import") (part "TESTPKG-RESISTOR0603"))
    )
    (comp (ref "R163")
      (value "TESTPKG-RESISTOR0603")
      (footprint "eagle-import:TESTPKG-R0603")
      (libsource (lib "eagle-import") (part "TESTPKG-RESISTOR0603"))
    )
    (comp (ref "R164")
      (value "TESTPKG-RESISTOR0603")
      (footprint "eagle-import:TESTPKG-R0603")
      (libsource (lib "eagle-import") (part "TESTPKG-RESISTOR0603"))
    )
    (comp (ref "R165")
      (value "TESTPKG-RESISTOR0603")
      (footprint "eagle-import:TESTPKG-R0603")
      (libsource (lib "eagle-import") (part "TESTPKG-RESISTOR0603"))
    )
    (comp (ref "R166")
      (value "TESTPKG-RESISTOR0603")
      (footprint "eagle-import:TESTPKG-R0603")
      (libsource (lib "eagle-import") (part "TESTPKG-RESISTOR0603"))
    )
    (comp (ref "R167")
      (value "TESTPKG-RESISTOR0603")
      (footprint "eagle-import:TESTPKG-R0603")
      (libsource (lib "eagle-import") (part "TESTPKG-RESISTOR0603"))
    )
    (comp (ref "R168")
      (value "TESTPKG-RESISTOR0603")
      (footprint "eagle-import:TESTPKG-R0603")
      (libsource (lib "eagle-import") (part "TESTPKG-RESISTOR0603"))
    )
    (comp (ref "R169")
      (value "TESTPKG-RESISTOR0603")
      (footprint "eagle-import:TESTPKG-R0603")
      (libsource (lib "eagle-import") (part "TESTPKG-RESISTOR0603"))
    )
    (comp (ref "R170")
      (value "TESTPKG-RESISTOR0603")
      (footprint "eagle-import:TESTPKG-R0603")
      (libsource (lib "eagle-import") (part "TESTPKG-RESISTOR0603"))
    )
    (comp (ref "R171")
      (value "TESTPKG-RESISTOR0603")
      (footprint "eagle-import:TESTPKG-R0603")
      (libsource (lib "eagle-import") (part "TESTPKG-RESISTOR0603"))
    )
    (comp (ref "R172")
      (value "TESTPKG-RESISTOR0603")
      (footprint "eagle-import:TESTPKG-R0603")
      (libsource (lib "eagle-import") (part "TESTPKG-RESISTOR0603"))
    )
    (comp (ref "R173")
      (value "TESTPKG-RESISTOR0603")
      (footprint "eagle-import:TESTPKG-R0603")
      (libsource (lib "eagle-import") (part "TESTPKG-RESISTOR0603"))
    )
    (comp (ref "R174")
      (value "TESTPKG-RESISTOR0603")
      (footprint "eagle-import:TESTPKG-R0603")
      (libsource (lib "eagle-import") (part "TESTPKG-RESISTOR0603"))
    )
    (comp (ref "R175")
      (value "TESTPKG-RESISTOR0603")
      (footprint "eagle-import:TESTPKG-R0603")
      (libsource (lib "eagle-import") (part "TESTPKG-RESISTOR0603"))
    )
    (comp (ref "R176")
      (value "TESTPKG-RESISTOR0603")
      (footprint "eagle-import:TESTPKG-R0603")
      (libsource (lib "eagle-import") (part "TESTPKG-RESISTOR0603"))
    )
    (comp (ref "R177")
      (value "TESTPKG-RESISTOR0603")
      (footprint "eagle-import:TESTPKG-R0603")
      (libsource (lib "eagle-import") (part "TESTPKG-RESISTOR0603"))
    )
    (comp (ref "R178")
      (value "TESTPKG-RESISTOR0603")
      (footprint "eagle-import:TESTPKG-R0603")
      (libsource (lib "eagle-import") (part "TESTPKG-RESISTOR0603"))
    )
    (comp (ref "R180")
      (value "TESTPKG-RESISTOR0603")
      (footprint "eagle-import:TESTPKG-R0603")
      (libsource (lib "eagle-import") (part "TESTPKG-RESISTOR0603"))
    )
    (comp (ref "R181")
      (value "TESTPKG-RESISTOR0603")
      (footprint "eagle-import:TESTPKG-R0603")
      (libsource (lib "eagle-import") (part "TESTPKG-RESISTOR0603"))
    )
    (comp (ref "R182")
      (value "TESTPKG-RESISTOR0603")
      (footprint "eagle-import:TESTPKG-R0603")
      (libsource (lib "eagle-import") (part "TESTPKG-RESISTOR0603"))
    )
    (comp (ref "R183")
      (value "TESTPKG-RESISTOR0603")
      (footprint "eagle-import:TESTPKG-R0603")
      (libsource (lib "eagle-import") (part "TESTPKG-RESISTOR0603"))
    )
    (comp (ref "R184")
      (value "TESTPKG-RESISTOR0603")
      (footprint "eagle-import:TESTPKG-R0603")
      (libsource (lib "eagle-import") (part "TESTPKG-RESISTOR0603"))
    )
    (comp (ref "R185")
      (value "TESTPKG-RESISTOR0603")
      (footprint "eagle-import:TESTPKG-R0603")
      (libsource (lib "eagle-import") (part "TESTPKG-RESISTOR0603"))
    )
    (comp (ref "R186")
      (value "TESTPKG-RESISTOR0603")
      (footprint "eagle-import:TESTPKG-R0603")
      (libsource (lib "eagle-import") (part "TESTPKG-RESISTOR0603"))
    )
    (comp (ref "R187")
      (value "TESTPKG-RESISTOR0603")
      (footprint "eagle-import:TESTPKG-R0603")
      (libsource (lib "eagle-import") (part "TESTPKG-RESISTOR0603"))
    )
    (comp (ref "R188")
      (value "TESTPKG-RESISTOR0603")
      (footprint "eagle-import:TESTPKG-R0603")
      (libsource (lib "eagle-import") (part "TESTPKG-RESISTOR0603"))
    )
    (comp (ref "R189")
      (value "TESTPKG-RESISTOR0603")
      (footprint "eagle-import:TESTPKG-R0603")
      (libsource (lib "eagle-import") (part "TESTPKG-RESISTOR0603"))
    )
    (comp (ref "R190")
      (value "TESTPKG-RESISTOR0603")
      (footprint "eagle-import:TESTPKG-R0603")
      (libsource (lib "eagle-import") (part "TESTPKG-RESISTOR0603"))
    )
    (comp (ref "R191")
      (value "TESTPKG-RESISTOR0603")
      (footprint "eagle-import:TESTPKG-R0603")
      (libsource (lib "eagle-import") (part "TESTPKG-RESISTOR0603"))
    )
    (comp (ref "R192")
      (value "TESTPKG-RESISTOR0603")
      (footprint "eagle-import:TESTPKG-R0603")
      (libsource (lib "eagle-import") (part "TESTPKG-RESISTOR0603"))
    )
    (comp (ref "R193")
      (value "TESTPKG-RESISTOR0603")
      (footprint "eagle-import:TESTPKG-R0603")
      (libsource (lib "eagle-import") (part "TESTPKG-RESISTOR0603"))
    )
    (comp (ref "R194")
      (value "TESTPKG-RESISTOR0603")
      (footprint "eagle-import:TESTPKG-R0603")
      (libsource (lib "eagle-import") (part "TESTPKG-RESISTOR0603"))
    )
    (comp (ref "R195")
      (value "TESTPKG-RESISTOR0603")
      (footprint "eagle-import:TESTPKG-R0603")
      (libsource (lib "eagle-import") (part "TESTPKG-RESISTOR0603"))
    )
    (comp (ref "R196")
      (value "TESTPKG-RESISTOR0603")
      (footprint "eagle-import:TESTPKG-R0603")
      (libsource (lib "eagle-import") (part "TESTPKG-RESISTOR0603"))
    )
    (comp (ref "R197")
      (value "TESTPKG-RESISTOR0603")
      (footprint "eagle-import:TESTPKG-R0603")
      (libsource (lib "eagle-import") (part "TESTPKG-RESISTOR0603"))
    )
    (comp (ref "R198")
      (value "TESTPKG-RESISTOR0603")
      (footprint "eagle-import:TESTPKG-R0603")
      (libsource (lib "eagle-import") (part "TESTPKG-RESISTOR0603"))
    )
    (comp (ref "R199")
      (value "TESTPKG-RESISTOR0603")
      (footprint "eagle-import:TESTPKG-R0603")
      (libsource (lib "eagle-import") (part "TESTPKG-RESISTOR0603"))
    )
    (comp (ref "R200")
      (value "TESTPKG-RESISTOR0603")
      (footprint "eagle-import:TESTPKG-R0603")
      (libsource (lib "eagle-import") (part "TESTPKG-RESISTOR0603"))
    )
    (comp (ref "R201")
      (value "TESTPKG-RESISTOR0603")
      (footprint "eagle-import:TESTPKG-R0603")
      (libsource (lib "eagle-import") (part "TESTPKG-RESISTOR0603"))
    )
    (comp (ref "R202")
      (value "TESTPKG-RESISTOR0603")
      (footprint "eagle-import:TESTPKG-R0603")
      (libsource (lib "eagle-import") (part "TESTPKG-RESISTOR0603"))
    )
    (comp (ref "R203")
      (value "TESTPKG-RESISTOR0603")
      (footprint "eagle-import:TESTPKG-R0603")
      (libsource (lib "eagle-import") (part "TESTPKG-RESISTOR0603"))
    )
    (comp (ref "R204")
      (value "TESTPKG-RESISTOR0603")
      (footprint "eagle-import:TESTPKG-R0603")
      (libsource (lib "eagle-import") (part "TESTPKG-RESISTOR0603"))
    )
    (comp (ref "R205")
      (value "TESTPKG-RESISTOR0603")
      (footprint "eagle-import:TESTPKG-R0603")
      (libsource (lib "eagle-import") (part "TESTPKG-RESISTOR0603"))
    )
    (comp (ref "R206")
      (value "TESTPKG-RESISTOR0603")
      (footprint "eagle-import:TESTPKG-R0603")
      (libsource (lib "eagle-import") (part "TESTPKG-RESISTOR0603"))
    )
    (comp (ref "R207")
      (value "TESTPKG-RESISTOR0603")
      (footprint "eagle-import:TESTPKG-R0603")
      (libsource (lib "eagle-import") (part "TESTPKG-RESISTOR0603"))
    )
    (comp (ref "R208")
      (value "TESTPKG-RESISTOR0603")
      (footprint "eagle-import:TESTPKG-R0603")
      (libsource (lib "eagle-import") (part "TESTPKG-RESISTOR0603"))
    )
    (comp (ref "R209")
      (value "TESTPKG-RESISTOR0603")
      (footprint "eagle-import:TESTPKG-R0603")
      (libsource (lib "eagle-import") (part "TESTPKG-RESISTOR0603"))
    )
    (comp (ref "R210")
      (value "TESTPKG-RESISTOR0603")
      (footprint "eagle-import:TESTPKG-R0603")
      (libsource (lib "eagle-import") (part "TESTPKG-RESISTOR0603"))
    )
    (comp (ref "R211")
      (value "TESTPKG-RESISTOR0603")
      (footprint "eagle-import:TESTPKG-R0603")
      (libsource (lib "eagle-import") (part "TESTPKG-RESISTOR0603"))
    )
    (comp (ref "R212")
      (value "TESTPKG-RESISTOR0603")
      (footprint "eagle-import:TESTPKG-R0603")
      (libsource (lib "eagle-import") (part "TESTPKG-RESISTOR0603"))
    )
    (comp (ref "R213")
      (value "TESTPKG-RESISTOR0603")
      (footprint "eagle-import:TESTPKG-R0603")
      (libsource (lib "eagle-import") (part "TESTPKG-RESISTOR0603"))
    )
    (comp (ref "R214")
      (value "TESTPKG-RESISTOR0603")
      (footprint "eagle-import:TESTPKG-R0603")
      (libsource (lib "eagle-import") (part "TESTPKG-RESISTOR0603"))
    )
    (comp (ref "R215")
      (value "TESTPKG-RESISTOR0603")
      (footprint "eagle-import:TESTPKG-R0603")
      (libsource (lib "eagle-import") (part "TESTPKG-RESISTOR0603"))
    )
    (comp (ref "R216")
      (value "TESTPKG-RESISTOR0603")
      (footprint "eagle-import:TESTPKG-R0603")
      (libsource (lib "eagle-import") (part "TESTPKG-RESISTOR0603"))
    )
    (comp (ref "R217")
      (value "TESTPKG-RESISTOR0603")
      (footprint "eagle-import:TESTPKG-R0603")
      (libsource (lib "eagle-import") (part "TESTPKG-RESISTOR0603"))
    )
    (comp (ref "R218")
      (value "TESTPKG-RESISTOR0603")
      (footprint "eagle-import:TESTPKG-R0603")
      (libsource (lib "eagle-import") (part "TESTPKG-RESISTOR0603"))
    )
    (comp (ref "R219")
      (value "TESTPKG-RESISTOR0603")
      (footprint "eagle-import:TESTPKG-R0603")
      (libsource (lib "eagle-import") (part "TESTPKG-RESISTOR0603"))
    )
    (comp (ref "R220")
      (value "TESTPKG-RESISTOR0603")
      (footprint "eagle-import:TESTPKG-R0603")
      (libsource (lib "eagle-import") (part "TESTPKG-RESISTOR0603"))
    )
    (comp (ref "R221")
      (value "TESTPKG-RESISTOR0603")
      (footprint "eagle-import:TESTPKG-R0603")
      (libsource (lib "eagle-import") (part "TESTPKG-RESISTOR0603"))
    )
    (comp (ref "R222")
      (value "TESTPKG-RESISTOR0603")
      (footprint "eagle-import:TESTPKG-R0603")
      (libsource (lib "eagle-import") (part "TESTPKG-RESISTOR0603"))
    )
    (comp (ref "R223")
      (value "TESTPKG-RESISTOR0603")
      (footprint "eagle-import:TESTPKG-R0603")
      (libsource (lib "eagle-import") (part "TESTPKG-RESISTOR0603"))
    )
    (comp (ref "R224")
      (value "TESTPKG-RESISTOR0603")
      (footprint "eagle-import:TESTPKG-R0603")
      (libsource (lib "eagle-import") (part "TESTPKG-RESISTOR0603"))
    )
    (comp (ref "R225")
      (value "TESTPKG-RESISTOR0603")
      (footprint "eagle-import:TESTPKG-R0603")
      (libsource (lib "eagle-import") (part "TESTPKG-RESISTOR0603"))
    )
    (comp (ref "R226")
      (value "TESTPKG-RESISTOR0603")
      (footprint "eagle-import:TESTPKG-R0603")
      (libsource (lib "eagle-import") (part "TESTPKG-RESISTOR0603"))
    )
    (comp (ref "R227")
      (value "TESTPKG-RESISTOR0603")
      (footprint "eagle-import:TESTPKG-R0603")
      (libsource (lib "eagle-import") (part "TESTPKG-RESISTOR0603"))
    )
    (comp (ref "R228")
      (value "TESTPKG-RESISTOR0603")
      (footprint "eagle-import:TESTPKG-R0603")
      (libsource (lib "eagle-import") (part "TESTPKG-RESISTOR0603"))
    )
    (comp (ref "R229")
      (value "TESTPKG-RESISTOR0603")
      (footprint "eagle-import:TESTPKG-R0603")
      (libsource (lib "eagle-import") (part "TESTPKG-RESISTOR0603"))
    )
    (comp (ref "R230")
      (value "TESTPKG-RESISTOR0603")
      (footprint "eagle-import:TESTPKG-R0603")
      (libsource (lib "eagle-import") (part "TESTPKG-RESISTOR0603"))
    )
    (comp (ref "R231")
      (value "TESTPKG-RESISTOR0603")
      (footprint "eagle-import:TESTPKG-R0603")
      (libsource (lib "eagle-import") (part "TESTPKG-RESISTOR0603"))
    )
    (comp (ref "R232")
      (value "TESTPKG-RESISTOR0603")
      (footprint "eagle-import:TESTPKG-R0603")
      (libsource (lib "eagle-import") (part "TESTPKG-RESISTOR0603"))
    )
    (comp (ref "R233")
      (value "TESTPKG-RESISTOR0603")
      (footprint "eagle-import:TESTPKG-R0603")
      (libsource (lib "eagle-import") (part "TESTPKG-RESISTOR0603"))
    )
    (comp (ref "R234")
      (value "TESTPKG-RESISTOR0603")
      (footprint "eagle-import:TESTPKG-R0603")
      (libsource (lib "eagle-import") (part "TESTPKG-RESISTOR0603"))
    )
    (comp (ref "R235")
      (value "TESTPKG-RESISTOR0603")
      (footprint "eagle-import:TESTPKG-R0603")
      (libsource (lib "eagle-import") (part "TESTPKG-RESISTOR0603"))
    )
    (comp (ref "R236")
      (value "TESTPKG-RESISTOR0603")
      (footprint "eagle-import:TESTPKG-R0603")
      (libsource (lib "eagle-import") (part "TESTPKG-RESISTOR0603"))
    )
    (comp (ref "R237")
      (value "TESTPKG-RESISTOR0603")
      (footprint "eagle-import:TESTPKG-R0603")
      (libsource (lib "eagle-import") (part "TESTPKG-RESISTOR0603"))
    )
    (comp (ref "R238")
      (value "TESTPKG-RESISTOR0603")
      (footprint "eagle-import:TESTPKG-R0603")
      (libsource (lib "eagle-import") (part "TESTPKG-RESISTOR0603"))
    )
    (comp (ref "R239")
      (value "TESTPKG-RESISTOR0603")
      (footprint "eagle-import:TESTPKG-R0603")
      (libsource (lib "eagle-import") (part "TESTPKG-RESISTOR0603"))
    )
    (comp (ref "R240")
      (value "TESTPKG-RESISTOR0603")
      (footprint "eagle-import:TESTPKG-R0603")
      (libsource (lib "eagle-import") (part "TESTPKG-RESISTOR0603"))
    )
    (comp (ref "R241")
      (value "TESTPKG-RESISTOR0603")
      (footprint "eagle-import:TESTPKG-R0603")
      (libsource (lib "eagle-import") (part "TESTPKG-RESISTOR0603"))
    )
    (comp (ref "R242")
      (value "TESTPKG-RESISTOR0603")
      (footprint "eagle-import:TESTPKG-R0603")
      (libsource (lib "eagle-import") (part "TESTPKG-RESISTOR0603"))
    )
    (comp (ref "R243")
      (value "TESTPKG-RESISTOR0603")
      (footprint "eagle-import:TESTPKG-R0603")
      (libsource (lib "eagle-import") (part "TESTPKG-RESISTOR0603"))
    )
    (comp (ref "R244")
      (value "TESTPKG-RESISTOR0603")
      (footprint "eagle-import:TESTPKG-R0603")
      (libsource (lib "eagle-import") (part "TESTPKG-RESISTOR0603"))
    )
    (comp (ref "R245")
      (value "TESTPKG-RESISTOR0603")
      (footprint "eagle-import:TESTPKG-R0603")
      (libsource (lib "eagle-import") (part "TESTPKG-RESISTOR0603"))
    )
    (comp (ref "R246")
      (value "TESTPKG-RESISTOR0603")
      (footprint "eagle-import:TESTPKG-R0603")
      (libsource (lib "eagle-import") (part "TESTPKG-RESISTOR0603"))
    )
    (comp (ref "R247")
      (value "TESTPKG-RESISTOR0603")
      (footprint "eagle-import:TESTPKG-R0603")
      (libsource (lib "eagle-import") (part "TESTPKG-RESISTOR0603"))
    )
    (comp (ref "R248")
      (value "TESTPKG-RESISTOR0603")
      (footprint "eagle-import:TESTPKG-R0603")
      (libsource (lib "eagle-import") (part "TESTPKG-RESISTOR0603"))
    )
    (comp (ref "R249")
      (value "TESTPKG-RESISTOR0603")
      (footprint "eagle-import:TESTPKG-R0603")
      (libsource (lib "eagle-import") (part "TESTPKG-RESISTOR0603"))
    )
    (comp (ref "R250")
      (value "TESTPKG-RESISTOR0603")
      (footprint "eagle-import:TESTPKG-R0603")
      (libsource (lib "eagle-import") (part "TESTPKG-RESISTOR0603"))
    )
    (comp (ref "R251")
      (value "TESTPKG-RESISTOR0603")
      (footprint "eagle-import:TESTPKG-R0603")
      (libsource (lib "eagle-import") (part "TESTPKG-RESISTOR0603"))
    )
    (comp (ref "R252")
      (value "TESTPKG-RESISTOR0603")
      (footprint "eagle-import:TESTPKG-R0603")
      (libsource (lib "eagle-import") (part "TESTPKG-RESISTOR0603"))
    )
    (comp (ref "R253")
      (value "TESTPKG-RESISTOR0603")
      (footprint "eagle-import:TESTPKG-R0603")
      (libsource (lib "eagle-import") (part "TESTPKG-RESISTOR0603"))
    )
    (comp (ref "R254")
      (value "TESTPKG-RESISTOR0603")
      (footprint "eagle-import:TESTPKG-R0603")
      (libsource (lib "eagle-import") (part "TESTPKG-RESISTOR0603"))
    )
    (comp (ref "R255")
      (value "TESTPKG-RESISTOR0603")
      (footprint "eagle-import:TESTPKG-R0603")
      (libsource (lib "eagle-import") (part "TESTPKG-RESISTOR0603"))
    )
    (comp (ref "R256")
      (value "TESTPKG-RESISTOR0603")
      (footprint "eagle-import:TESTPKG-R0603")
      (libsource (lib "eagle-import") (part "TESTPKG-RESISTOR0603"))
    )
    (comp (ref "R257")
      (value "TESTPKG-RESISTOR0603")
      (footprint "eagle-import:TESTPKG-R0603")
      (libsource (lib "eagle-import") (part "TESTPKG-RESISTOR0603"))
    )
    (comp (ref "R258")
      (value "TESTPKG-RESISTOR0603")
      (footprint "eagle-import:TESTPKG-R0603")
      (libsource (lib "eagle-import") (part "TESTPKG-RESISTOR0603"))
    )
    (comp (ref "R259")
      (value "TESTPKG-RESISTOR0603")
      (footprint "eagle-import:TESTPKG-R0603")
      (libsource (lib "eagle-import") (part "TESTPKG-RESISTOR0603"))
    )
    (comp (ref "R260")
      (value "TESTPKG-RESISTOR0603")
      (footprint "eagle-import:TESTPKG-R0603")
      (libsource (lib "eagle-import") (part "TESTPKG-RESISTOR0603"))
    )
    (comp (ref "R261")
      (value "TESTPKG-RESISTOR0603")
      (footprint "eagle-import:TESTPKG-R0603")
      (libsource (lib "eagle-import") (part "TESTPKG-RESISTOR0603"))
    )
    (comp (ref "R262")
      (value "TESTPKG-RESISTOR0603")
      (footprint "eagle-import:TESTPKG-R0603")
      (libsource (lib "eagle-import") (part "TESTPKG-RESISTOR0603"))
    )
    (comp (ref "R263")
      (value "TESTPKG-RESISTOR0603")
      (footprint "eagle-import:TESTPKG-R0603")
      (libsource (lib "eagle-import") (part "TESTPKG-RESISTOR0603"))
    )
    (comp (ref "R264")
      (value "TESTPKG-RESISTOR0603")
      (footprint "eagle-import:TESTPKG-R0603")
      (libsource (lib "eagle-import") (part "TESTPKG-RESISTOR0603"))
    )
    (comp (ref "R265")
      (value "TESTPKG-RESISTOR0603")
      (footprint "eagle-import:TESTPKG-R0603")
      (libsource (lib "eagle-import") (part "TESTPKG-RESISTOR0603"))
    )
    (comp (ref "R266")
      (value "TESTPKG-RESISTOR0603")
      (footprint "eagle-import:TESTPKG-R0603")
      (libsource (lib "eagle-import") (part "TESTPKG-RESISTOR0603"))
    )
    (comp (ref "R267")
      (value "TESTPKG-RESISTOR0603")
      (footprint "eagle-import:TESTPKG-R0603")
      (libsource (lib "eagle-import") (part "TESTPKG-RESISTOR0603"))
    )
    (comp (ref "R268")
      (value "TESTPKG-RESISTOR0603")
      (footprint "eagle-import:TESTPKG-R0603")
      (libsource (lib "eagle-import") (part "TESTPKG-RESISTOR0603"))
    )
    (comp (ref "R269")
      (value "TESTPKG-RESISTOR0603")
      (footprint "eagle-import:TESTPKG-R0603")
      (libsource (lib "eagle-import") (part "TESTPKG-RESISTOR0603"))
    )
    (comp (ref "R270")
      (value "TESTPKG-RESISTOR0603")
      (footprint "eagle-import:TESTPKG-R0603")
      (libsource (lib "eagle-import") (part "TESTPKG-RESISTOR0603"))
    )
    (comp (ref "R271")
      (value "TESTPKG-RESISTOR0603")
      (footprint "eagle-import:TESTPKG-R0603")
      (libsource (lib "eagle-import") (part "TESTPKG-RESISTOR0603"))
    )
    (comp (ref "R272")
      (value "TESTPKG-RESISTOR0603")
      (footprint "eagle-import:TESTPKG-R0603")
      (libsource (lib "eagle-import") (part "TESTPKG-RESISTOR0603"))
    )
    (comp (ref "R273")
      (value "TESTPKG-RESISTOR0603")
      (footprint "eagle-import:TESTPKG-R0603")
      (libsource (lib "eagle-import") (part "TESTPKG-RESISTOR0603"))
    )
    (comp (ref "R274")
      (value "TESTPKG-RESISTOR0603")
      (footprint "eagle-import:TESTPKG-R0603")
      (libsource (lib "eagle-import") (part "TESTPKG-RESISTOR0603"))
    )
    (comp (ref "R275")
      (value "TESTPKG-RESISTOR0603")
      (footprint "eagle-import:TESTPKG-R0603")
      (libsource (lib "eagle-import") (part "TESTPKG-RESISTOR0603"))
    )
    (comp (ref "R276")
      (value "TESTPKG-RESISTOR0603")
      (footprint "eagle-import:TESTPKG-R0603")
      (libsource (lib "eagle-import") (part "TESTPKG-RESISTOR0603"))
    )
    (comp (ref "R277")
      (value "TESTPKG-RESISTOR0603")
      (footprint "eagle-import:TESTPKG-R0603")
      (libsource (lib "eagle-import") (part "TESTPKG-RESISTOR0603"))
    )
    (comp (ref "R278")
      (value "TESTPKG-RESISTOR0603")
      (footprint "eagle-import:TESTPKG-R0603")
      (libsource (lib "eagle-import") (part "TESTPKG-RESISTOR0603"))
    )
    (comp (ref "R279")
      (value "TESTPKG-RESISTOR0603")
      (footprint "eagle-import:TESTPKG-R0603")
      (libsource (lib "eagle-import") (part "TESTPKG-RESISTOR0603"))
    )
    (comp (ref "R280")
      (value "TESTPKG-RESISTOR0603")
      (footprint "eagle-import:TESTPKG-R0603")
      (libsource (lib "eagle-import") (part "TESTPKG-RESISTOR0603"))
    )
    (comp (ref "R281")
      (value "TESTPKG-RESISTOR0603")
      (footprint "eagle-import:TESTPKG-R0603")
      (libsource (lib "eagle-import") (part "TESTPKG-RESISTOR0603"))
    )
    (comp (ref "R282")
      (value "TESTPKG-RESISTOR0603")
      (footprint "eagle-import:TESTPKG-R0603")
      (libsource (lib "eagle-import") (part "TESTPKG-RESISTOR0603"))
    )
    (comp (ref "R283")
      (value "TESTPKG-RESISTOR0603")
      (footprint "eagle-import:TESTPKG-R0603")
      (libsource (lib "eagle-import") (part "TESTPKG-RESISTOR0603"))
    )
    (comp (ref "R284")
      (value "TESTPKG-RESISTOR0603")
      (footprint "eagle-import:TESTPKG-R0603")
      (libsource (lib "eagle-import") (part "TESTPKG-RESISTOR0603"))
    )
    (comp (ref "R285")
      (value "TESTPKG-RESISTOR0603")
      (footprint "eagle-import:TESTPKG-R0603")
      (libsource (lib "eagle-import") (part "TESTPKG-RESISTOR0603"))
    )
    (comp (ref "R286")
      (value "TESTPKG-RESISTOR0603")
      (footprint "eagle-import:TESTPKG-R0603")
      (libsource (lib "eagle-import") (part "TESTPKG-RESISTOR0603"))
    )
    (comp (ref "R287")
      (value "TESTPKG-RESISTOR0603")
      (footprint "eagle-import:TESTPKG-R0603")
      (libsource (lib "eagle-import") (part "TESTPKG-RESISTOR0603"))
    )
    (comp (ref "R288")
      (value "TESTPKG-RESISTOR0603")
      (footprint "eagle-import:TESTPKG-R0603")
      (libsource (lib "eagle-import") (part "TESTPKG-RESISTOR0603"))
    )
    (comp (ref "R289")
      (value "TESTPKG-RESISTOR0603")
      (footprint "eagle-import:TESTPKG-R0603")
      (libsource (lib "eagle-import") (part "TESTPKG-RESISTOR0603"))
    )
    (comp (ref "R290")
      (value "TESTPKG-RESISTOR0603")
      (footprint "eagle-import:TESTPKG-R0603")
      (libsource (lib "eagle-import") (part "TESTPKG-RESISTOR0603"))
    )
    (comp (ref "R291")
      (value "TESTPKG-RESISTOR0603")
      (footprint "eagle-import:TESTPKG-R0603")
      (libsource (lib "eagle-import") (part "TESTPKG-RESISTOR0603"))
    )
    (comp (ref "R292")
      (value "TESTPKG-RESISTOR0603")
      (footprint "eagle-import:TESTPKG-R0603")
      (libsource (lib "eagle-import") (part "TESTPKG-RESISTOR0603"))
    )
    (comp (ref "R293")
      (value "TESTPKG-RESISTOR0603")
      (footprint "eagle-import:TESTPKG-R0603")
      (libsource (lib "eagle-import") (part "TESTPKG-RESISTOR0603"))
    )
    (comp (ref "R294")
      (value "TESTPKG-RESISTOR0603")
      (footprint "eagle-import:TESTPKG-R0603")
      (libsource (lib "eagle-import") (part "TESTPKG-RESISTOR0603"))
    )
    (comp (ref "R295")
      (value "TESTPKG-RESISTOR0603")
      (footprint "eagle-import:TESTPKG-R0603")
      (libsource (lib "eagle-import") (part "TESTPKG-RESISTOR0603"))
    )
    (comp (ref "R296")
      (value "TESTPKG-RESISTOR0603")
      (footprint "eagle-import:TESTPKG-R0603")
      (libsource (lib "eagle-import") (part "TESTPKG-RESISTOR0603"))
    )
    (comp (ref "R297")
      (value "TESTPKG-RESISTOR0603")
      (footprint "eagle-import:TESTPKG-R0603")
      (libsource (lib "eagle-import") (part "TESTPKG-RESISTOR0603"))
    )
    (comp (ref "R298")
      (value "TESTPKG-RESISTOR0603")
      (footprint "eagle-import:TESTPKG-R0603")
      (libsource (lib "eagle-import") (part "TESTPKG-RESISTOR0603"))
    )
    (comp (ref "R299")
      (value "TESTPKG-RESISTOR0603")
      (footprint "eagle-import:TESTPKG-R0603")
      (libsource (lib "eagle-import") (part "TESTPKG-RESISTOR0603"))
    )
    (comp (ref "R300")
      (value "TESTPKG-RESISTOR0603")
      (footprint "eagle-import:TESTPKG-R0603")
      (libsource (lib "eagle-import") (part "TESTPKG-RESISTOR0603"))
    )
    (comp (ref "R301")
      (value "TESTPKG-RESISTOR0603")
      (footprint "eagle-import:TESTPKG-R0603")
      (libsource (lib "eagle-import") (part "TESTPKG-RESISTOR0603"))
    )
    (comp (ref "R302")
      (value "TESTPKG-RESISTOR0603")
      (footprint "eagle-import:TESTPKG-R0603")
      (libsource (lib "eagle-import") (part "TESTPKG-RESISTOR0603"))
    )
    (comp (ref "R303")
      (value "TESTPKG-RESISTOR0603")
      (footprint "eagle-import:TESTPKG-R0603")
      (libsource (lib "eagle-import") (part "TESTPKG-RESISTOR0603"))
    )
    (comp (ref "R304")
      (value "TESTPKG-RESISTOR0603")
      (footprint "eagle-import:TESTPKG-R0603")
      (libsource (lib "eagle-import") (part "TESTPKG-RESISTOR0603"))
    )
    (comp (ref "R305")
      (value "TESTPKG-RESISTOR0603")
      (footprint "eagle-import:TESTPKG-R0603")
      (libsource (lib "eagle-import") (part "TESTPKG-RESISTOR0603"))
    )
    (comp (ref "R306")
      (value "TESTPKG-RESISTOR0603")
      (footprint "eagle-import:TESTPKG-R0603")
      (libsource (lib "eagle-import") (part "TESTPKG-RESISTOR0603"))
    )
    (comp (ref "R307")
      (value "TESTPKG-RESISTOR0603")
      (footprint "eagle-import:TESTPKG-R0603")
      (libsource (lib "eagle-import") (part "TESTPKG-RESISTOR0603"))
    )
    (comp (ref "R308")
      (value "TESTPKG-RESISTOR0603")
      (footprint "eagle-import:TESTPKG-R0603")
      (libsource (lib "eagle-import") (part "TESTPKG-RESISTOR0603"))
    )
    (comp (ref "R309")
      (value "TESTPKG-RESISTOR0603")
      (footprint "eagle-import:TESTPKG-R0603")
      (libsource (lib "eagle-import") (part "TESTPKG-RESISTOR0603"))
    )
    (comp (ref "R310")
      (value "TESTPKG-RESISTOR0603")
      (footprint "eagle-import:TESTPKG-R0603")
      (libsource (lib "eagle-import") (part "TESTPKG-RESISTOR0603"))
    )
    (comp (ref "R311")
      (value "TESTPKG-RESISTOR0603")
      (footprint "eagle-import:TESTPKG-R0603")
      (libsource (lib "eagle-import") (part "TESTPKG-RESISTOR0603"))
    )
    (comp (ref "R312")
      (value "TESTPKG-RESISTOR0603")
      (footprint "eagle-import:TESTPKG-R0603")
      (libsource (lib "eagle-import") (part "TESTPKG-RESISTOR0603"))
    )
    (comp (ref "R313")
      (value "TESTPKG-RESISTOR0603")
      (footprint "eagle-import:TESTPKG-R0603")
      (libsource (lib "eagle-import") (part "TESTPKG-RESISTOR0603"))
    )
    (comp (ref "R314")
      (value "TESTPKG-RESISTOR0603")
      (footprint "eagle-import:TESTPKG-R0603")
      (libsource (lib "eagle-import") (part "TESTPKG-RESISTOR0603"))
    )
    (comp (ref "R315")
      (value "TESTPKG-RESISTOR0603")
      (footprint "eagle-import:TESTPKG-R0603")
      (libsource (lib "eagle-import") (part "TESTPKG-RESISTOR0603"))
    )
    (comp (ref "R316")
      (value "TESTPKG-RESISTOR0603")
      (footprint "eagle-import:TESTPKG-R0603")
      (libsource (lib "eagle-import") (part "TESTPKG-RESISTOR0603"))
    )
    (comp (ref "R317")
      (value "TESTPKG-RESISTOR0603")
      (footprint "eagle-import:TESTPKG-R0603")
      (libsource (lib "eagle-import") (part "TESTPKG-RESISTOR0603"))
    )
    (comp (ref "R318")
      (value "TESTPKG-RESISTOR0603")
      (footprint "eagle-import:TESTPKG-R0603")
      (libsource (lib "eagle-import") (part "TESTPKG-RESISTOR0603"))
    )
    (comp (ref "R319")
      (value "TESTPKG-RESISTOR0603")
      (footprint "eagle-import:TESTPKG-R0603")
      (libsource (lib "eagle-import") (part "TESTPKG-RESISTOR0603"))
    )
    (comp (ref "R320")
      (value "TESTPKG-RESISTOR0603")
      (footprint "eagle-import:TESTPKG-R0603")
      (libsource (lib "eagle-import") (part "TESTPKG-RESISTOR0603"))
    )
    (comp (ref "R321")
      (value "TESTPKG-RESISTOR0603")
      (footprint "eagle-import:TESTPKG-R0603")
      (libsource (lib "eagle-import") (part "TESTPKG-RESISTOR0603"))
    )
    (comp (ref "R322")
      (value "TESTPKG-RESISTOR0603")
      (footprint "eagle-import:TESTPKG-R0603")
      (libsource (lib "eagle-import") (part "TESTPKG-RESISTOR0603"))
    )
    (comp (ref "R323")
      (value "TESTPKG-RESISTOR0603")
      (footprint "eagle-import:TESTPKG-R0603")
      (libsource (lib "eagle-import") (part "TESTPKG-RESISTOR0603"))
    )
    (comp (ref "R324")
      (value "TESTPKG-RESISTOR0603")
      (footprint "eagle-import:TESTPKG-R0603")
      (libsource (lib "eagle-import") (part "TESTPKG-RESISTOR0603"))
    )
    (comp (ref "R325")
      (value "TESTPKG-RESISTOR0603")
      (footprint "eagle-import:TESTPKG-R0603")
      (libsource (lib "eagle-import") (part "TESTPKG-RESISTOR0603"))
    )
    (comp (ref "R326")
      (value "TESTPKG-RESISTOR0603")
      (footprint "eagle-import:TESTPKG-R0603")
      (libsource (lib "eagle-import") (part "TESTPKG-RESISTOR0603"))
    )
    (comp (ref "R327")
      (value "TESTPKG-RESISTOR0603")
      (footprint "eagle-import:TESTPKG-R0603")
      (libsource (lib "eagle-import") (part "TESTPKG-RESISTOR0603"))
    )
    (comp (ref "R328")
      (value "TESTPKG-RESISTOR0603")
      (footprint "eagle-import:TESTPKG-R0603")
      (libsource (lib "eagle-import") (part "TESTPKG-RESISTOR0603"))
    )
    (comp (ref "R329")
      (value "TESTPKG-RESISTOR0603")
      (footprint "eagle-import:TESTPKG-R0603")
      (libsource (lib "eagle-import") (part "TESTPKG-RESISTOR0603"))
    )
    (comp (ref "R330")
      (value "TESTPKG-RESISTOR0603")
      (footprint "eagle-import:TESTPKG-R0603")
      (libsource (lib "eagle-import") (part "TESTPKG-RESISTOR0603"))
    )
    (comp (ref "R331")
      (value "TESTPKG-RESISTOR0603")
      (footprint "eagle-import:TESTPKG-R0603")
      (libsource (lib "eagle-import") (part "TESTPKG-RESISTOR0603"))
    )
    (comp (ref "R332")
      (value "TESTPKG-RESISTOR0603")
      (footprint "eagle-import:TESTPKG-R0603")
      (libsource (lib "eagle-import") (part "TESTPKG-RESISTOR0603"))
    )
    (comp (ref "R333")
      (value "TESTPKG-RESISTOR0603")
      (footprint "eagle-import:TESTPKG-R0603")
      (libsource (lib "eagle-import") (part "TESTPKG-RESISTOR0603"))
    )
    (comp (ref "R334")
      (value "TESTPKG-RESISTOR0603")
      (footprint "eagle-import:TESTPKG-R0603")
      (libsource (lib "eagle-import") (part "TESTPKG-RESISTOR0603"))
    )
    (comp (ref "R335")
      (value "TESTPKG-RESISTOR0603")
      (footprint "eagle-import:TESTPKG-R0603")
      (libsource (lib "eagle-import") (part "TESTPKG-RESISTOR0603"))
    )
    (comp (ref "R336")
      (value "TESTPKG-RESISTOR0603")
      (footprint "eagle-import:TESTPKG-R0603")
      (libsource (lib "eagle-import") (part "TESTPKG-RESISTOR0603"))
    )
    (comp (ref "R337")
      (value "TESTPKG-RESISTOR0603")
      (footprint "eagle-import:TESTPKG-R0603")
      (libsource (lib "eagle-import") (part "TESTPKG-RESISTOR0603"))
    )
    (comp (ref "R338")
      (value "TESTPKG-RESISTOR0603")
      (footprint "eagle-import:TESTPKG-R0603")
      (libsource (lib "eagle-import") (part "TESTPKG-RESISTOR0603"))
    )
    (comp (ref "R339")
      (value "TESTPKG-RESISTOR0603")
      (footprint "eagle-import:TESTPKG-R0603")
      (libsource (lib "eagle-import") (part "TESTPKG-RESISTOR0603"))
    )
    (comp (ref "R340")
      (value "TESTPKG-RESISTOR0603")
      (footprint "eagle-import:TESTPKG-R0603")
      (libsource (lib "eagle-import") (part "TESTPKG-RESISTOR0603"))
    )
    (comp (ref "R341")
      (value "TESTPKG-RESISTOR0603")
      (footprint "eagle-import:TESTPKG-R0603")
      (libsource (lib "eagle-import") (part "TESTPKG-RESISTOR0603"))
    )
    (comp (ref "R342")
      (value "TESTPKG-RESISTOR0603")
      (footprint "eagle-import:TESTPKG-R0603")
      (libsource (lib "eagle-import") (part "TESTPKG-RESISTOR0603"))
    )
    (comp (ref "R343")
      (value "TESTPKG-RESISTOR0603")
      (footprint "eagle-import:TESTPKG-R0603")
      (libsource (lib "eagle-import") (part "TESTPKG-RESISTOR0603"))
    )
    (comp (ref "R344")
      (value "TESTPKG-RESISTOR0603")
      (footprint "eagle-import:TESTPKG-R0603")
      (libsource (lib "eagle-import") (part "TESTPKG-RESISTOR0603"))
    )
    (comp (ref "R345")
      (value "TESTPKG-RESISTOR0603")
      (footprint "eagle-import:TESTPKG-R0603")
      (libsource (lib "eagle-import") (part "TESTPKG-RESISTOR0603"))
    )
    (comp (ref "R346")
      (value "TESTPKG-RESISTOR0603")
      (footprint "eagle-import:TESTPKG-R0603")
      (libsource (lib "eagle-import") (part "TESTPKG-RESISTOR0603"))
    )
    (comp (ref "R347")
      (value "TESTPKG-RESISTOR0603")
      (footprint "eagle-import:TESTPKG-R0603")
      (libsource (lib "eagle-import") (part "TESTPKG-RESISTOR0603"))
    )
    (comp (ref "R348")
      (value "TESTPKG-RESISTOR0603")
      (footprint "eagle-import:TESTPKG-R0603")
      (libsource (lib "eagle-import") (part "TESTPKG-RESISTOR0603"))
    )
    (comp (ref "R349")
      (value "TESTPKG-RESISTOR0603")
      (footprint "eagle-import:TESTPKG-R0603")
      (libsource (lib "eagle-import") (part "TESTPKG-RESISTOR0603"))
    )
    (comp (ref "R350")
      (value "TESTPKG-RESISTOR0603")
      (footprint "eagle-import:TESTPKG-R0603")
      (libsource (lib "eagle-import") (part "TESTPKG-RESISTOR0603"))
    )
    (comp (ref "R351")
      (value "TESTPKG-RESISTOR0603")
      (footprint "eagle-import:TESTPKG-R0603")
      (libsource (lib "eagle-import") (part "TESTPKG-RESISTOR0603"))
    )
    (comp (ref "R352")
      (value "TESTPKG-RESISTOR0603")
      (footprint "eagle-import:TESTPKG-R0603")
      (libsource (lib "eagle-import") (part "TESTPKG-RESISTOR0603"))
    )
    (comp (ref "R353")
      (value "TESTPKG-RESISTOR0603")
      (footprint "eagle-import:TESTPKG-R0603")
      (libsource (lib "eagle-import") (part "TESTPKG-RESISTOR0603"))
    )
    (comp (ref "R354")
      (value "TESTPKG-RESISTOR0603")
      (footprint "eagle-import:TESTPKG-R0603")
      (libsource (lib "eagle-import") (part "TESTPKG-RESISTOR0603"))
    )
    (comp (ref "R355")
      (value "TESTPKG-RESISTOR0603")
      (footprint "eagle-import:TESTPKG-R0603")
      (libsource (lib "eagle-import") (part "TESTPKG-RESISTOR0603"))
    )
    (comp (ref "R356")
      (value "TESTPKG-RESISTOR0603")
      (footprint "eagle-import:TESTPKG-R0603")
      (libsource (lib "eagle-import") (part "TESTPKG-RESISTOR0603"))
    )
    (comp (ref "R357")
      (value "TESTPKG-RESISTOR0603")
      (footprint "eagle-import:TESTPKG-R0603")
      (libsource (lib "eagle-import") (part "TESTPKG-RESISTOR0603"))
    )
    (comp (ref "TP1")
      (value "CONN-TESTPOINT")
      (footprint "eagle-import:CON-TESTPOINT")
      (libsource (lib "eagle-import") (part "CONN-TESTPOINT"))
    )
    (comp (ref "TP2")
      (value "CONN-TESTPOINT")
      (footprint "eagle-import:CON-TESTPOINT")
      (libsource (lib "eagle-import") (part "CONN-TESTPOINT"))
    )
    (comp (ref "TP3")
      (value "CONN-TESTPOINT")
      (footprint "eagle-import:CON-TESTPOINT")
      (libsource (lib "eagle-import") (part "CONN-TESTPOINT"))
    )
    (comp (ref "TP4")
      (value "CONN-TESTPOINT")
      (footprint "eagle-import:CON-TESTPOINT")
      (libsource (lib "eagle-import") (part "CONN-TESTPOINT"))
    )
    (comp (ref "TP5")
      (value "CONN-TESTPOINT")
      (footprint "eagle-import:CON-TESTPOINT")
      (libsource (lib "eagle-import") (part "CONN-TESTPOINT"))
    )
    (comp (ref "TP6")
      (value "CONN-TESTPOINT")
      (footprint "eagle-import:CON-TESTPOINT")
      (libsource (lib "eagle-import") (part "CONN-TESTPOINT"))
    )
    (comp (ref "TP7")
      (value "CONN-TESTPOINT")
      (footprint "eagle-import:CON-TESTPOINT")
      (libsource (lib "eagle-import") (part "CONN-TESTPOINT"))
    )
    (comp (ref "TP8")
      (value "CONN-TESTPOINT")
      (footprint "eagle-import:CON-TESTPOINT")
      (libsource (lib "eagle-import") (part "CONN-TESTPOINT"))
    )
    (comp (ref "TP9")
      (value "CONN-TESTPOINT")
      (footprint "eagle-import:CON-TESTPOINT")
      (libsource (lib "eagle-import") (part "CONN-TESTPOINT"))
    )
    (comp (ref "TP10")
      (value "CONN-TESTPOINT")
      (footprint "eagle-import:CON-TESTPOINT")
      (libsource (lib "eagle-import") (part "CONN-TESTPOINT"))
    )
    (comp (ref "TP11")
      (value "CONN-TESTPOINT")
      (footprint "eagle-import:CON-TESTPOINT")
      (libsource (lib "eagle-import") (part "CONN-TESTPOINT"))
    )
    (comp (ref "TP12")
      (value "CONN-TESTPOINT")
      (footprint "eagle-import:CON-TESTPOINT")
      (libsource (lib "eagle-import") (part "CONN-TESTPOINT"))
    )
    (comp (ref "TP13")
      (value "CONN-TESTPOINT")
      (footprint "eagle-import:CON-TESTPOINT")
      (libsource (lib "eagle-import") (part "CONN-TESTPOINT"))
    )
    (comp (ref "TP14")
      (value "CONN-TESTPOINT")
      (footprint "eagle-import:CON-TESTPOINT")
      (libsource (lib "eagle-import") (part "CONN-TESTPOINT"))
    )
    (comp (ref "TP15")
      (value "CONN-TESTPOINT")
      (footprint "eagle-import:CON-TESTPOINT")
      (libsource (lib "eagle-import") (part "CONN-TESTPOINT"))
    )
    (comp (ref "TP16")
      (value "CONN-TESTPOINT")
      (footprint "eagle-import:CON-TESTPOINT")
      (libsource (lib "eagle-import") (part "CONN-TESTPOINT"))
    )
    (comp (ref "TP17")
      (value "CONN-TESTPOINT")
      (footprint "eagle-import:CON-TESTPOINT")
      (libsource (lib "eagle-import") (part "CONN-TESTPOINT"))
    )
    (comp (ref "TP18")
      (value "CONN-TESTPOINT")
      (footprint "eagle-import:CON-TESTPOINT")
      (libsource (lib "eagle-import") (part "CONN-TESTPOINT"))
    )
    (comp (ref "TP19")
      (value "CONN-TESTPOINT")
      (footprint "eagle-import:CON-TESTPOINT")
      (libsource (lib "eagle-import") (part "CONN-TESTPOINT"))
    )
    (comp (ref "TP20")
      (value "CONN-TESTPOINT")
      (footprint "eagle-import:CON-TESTPOINT")
      (libsource (lib "eagle-import") (part "CONN-TESTPOINT"))
    )
    (comp (ref "FID6")
      (value "FIDUCIAL")
      (footprint "eagle-import:FIDUCIAL")
      (libsource (lib "eagle-import") (part "FIDUCIAL"))
    )
    (comp (ref "FID7")
      (value "FIDUCIAL")
      (footprint "eagle-import:FIDUCIAL")
      (libsource (lib "eagle-import") (part "FIDUCIAL"))
    )
    (comp (ref "FID8")
      (value "FIDUCIAL")
      (footprint "eagle-import:FIDUCIAL")
      (libsource (lib "eagle-import") (part "FIDUCIAL"))
    )
    (comp (ref "FID9")
      (value "FIDUCIAL")
      (footprint "eagle-import:FIDUCIAL")
      (libsource (lib "eagle-import") (part "FIDUCIAL"))
    )
    (comp (ref "FID10")
      (value "FIDUCIAL")
      (footprint "eagle-import:FIDUCIAL")
      (libsource (lib "eagle-import") (part "FIDUCIAL"))
    )
    (comp (ref "R179")
      (value "TESTPKG-RESISTOR0805")
      (footprint "eagle-import:TESTPKG-R0805")
      (libsource (lib "eagle-import") (part "TESTPKG-RESISTOR0805"))
    )
    (comp (ref "R358")
      (value "TESTPKG-RESISTOR0805")
      (footprint "eagle-import:TESTPKG-R0805")
      (libsource (lib "eagle-import") (part "TESTPKG-RESISTOR0805"))
    )
    (comp (ref "R359")
      (value "TESTPKG-RESISTOR0805")
      (footprint "eagle-import:TESTPKG-R0805")
      (libsource (lib "eagle-import") (part "TESTPKG-RESISTOR0805"))
    )
    (comp (ref "R360")
      (value "TESTPKG-RESISTOR0805")
      (footprint "eagle-import:TESTPKG-R0805")
      (libsource (lib "eagle-import") (part "TESTPKG-RESISTOR0805"))
    )
    (comp (ref "R361")
      (value "TESTPKG-RESISTOR0805")
      (footprint "eagle-import:TESTPKG-R0805")
      (libsource (lib "eagle-import") (part "TESTPKG-RESISTOR0805"))
    )
    (comp (ref "R362")
      (value "TESTPKG-RESISTOR0805")
      (footprint "eagle-import:TESTPKG-R0805")
      (libsource (lib "eagle-import") (part "TESTPKG-RESISTOR0805"))
    )
    (comp (ref "R363")
      (value "TESTPKG-RESISTOR0805")
      (footprint "eagle-import:TESTPKG-R0805")
      (libsource (lib "eagle-import") (part "TESTPKG-RESISTOR0805"))
    )
    (comp (ref "R364")
      (value "TESTPKG-RESISTOR0805")
      (footprint "eagle-import:TESTPKG-R0805")
      (libsource (lib "eagle-import") (part "TESTPKG-RESISTOR0805"))
    )
    (comp (ref "R365")
      (value "TESTPKG-RESISTOR0805")
      (footprint "eagle-import:TESTPKG-R0805")
      (libsource (lib "eagle-import") (part "TESTPKG-RESISTOR0805"))
    )
    (comp (ref "R366")
      (value "TESTPKG-RESISTOR0805")
      (footprint "eagle-import:TESTPKG-R0805")
      (libsource (lib "eagle-import") (part "TESTPKG-RESISTOR0805"))
    )
    (comp (ref "R367")
      (value "TESTPKG-RESISTOR0805")
      (footprint "eagle-import:TESTPKG-R0805")
      (libsource (lib "eagle-import") (part "TESTPKG-RESISTOR0805"))
    )
    (comp (ref "R368")
      (value "TESTPKG-RESISTOR0805")
      (footprint "eagle-import:TESTPKG-R0805")
      (libsource (lib "eagle-import") (part "TESTPKG-RESISTOR0805"))
    )
    (comp (ref "R369")
      (value "TESTPKG-RESISTOR0805")
      (footprint "eagle-import:TESTPKG-R0805")
      (libsource (lib "eagle-import") (part "TESTPKG-RESISTOR0805"))
    )
    (comp (ref "R370")
      (value "TESTPKG-RESISTOR0805")
      (footprint "eagle-import:TESTPKG-R0805")
      (libsource (lib "eagle-import") (part "TESTPKG-RESISTOR0805"))
    )
    (comp (ref "R371")
      (value "TESTPKG-RESISTOR0805")
      (footprint "eagle-import:TESTPKG-R0805")
      (libsource (lib "eagle-import") (part "TESTPKG-RESISTOR0805"))
    )
    (comp (ref "R372")
      (value "TESTPKG-RESISTOR0805")
      (footprint "eagle-import:TESTPKG-R0805")
      (libsource (lib "eagle-import") (part "TESTPKG-RESISTOR0805"))
    )
    (comp (ref "R373")
      (value "TESTPKG-RESISTOR0805")
      (footprint "eagle-import:TESTPKG-R0805")
      (libsource (lib "eagle-import") (part "TESTPKG-RESISTOR0805"))
    )
    (comp (ref "R374")
      (value "TESTPKG-RESISTOR0805")
      (footprint "eagle-import:TESTPKG-R0805")
      (libsource (lib "eagle-import") (part "TESTPKG-RESISTOR0805"))
    )
    (comp (ref "R375")
      (value "TESTPKG-RESISTOR0805")
      (footprint "eagle-import:TESTPKG-R0805")
      (libsource (lib "eagle-import") (part "TESTPKG-RESISTOR0805"))
    )
    (comp (ref "R376")
      (value "TESTPKG-RESISTOR0805")
      (footprint "eagle-import:TESTPKG-R0805")
      (libsource (lib "eagle-import") (part "TESTPKG-RESISTOR0805"))
    )
    (comp (ref "R377")
      (value "TESTPKG-RESISTOR0805")
      (footprint "eagle-import:TESTPKG-R0805")
      (libsource (lib "eagle-import") (part "TESTPKG-RESISTOR0805"))
    )
    (comp (ref "R378")
      (value "TESTPKG-RESISTOR0805")
      (footprint "eagle-import:TESTPKG-R0805")
      (libsource (lib "eagle-import") (part "TESTPKG-RESISTOR0805"))
    )
    (comp (ref "R379")
      (value "TESTPKG-RESISTOR0805")
      (footprint "eagle-import:TESTPKG-R0805")
      (libsource (lib "eagle-import") (part "TESTPKG-RESISTOR0805"))
    )
    (comp (ref "R380")
      (value "TESTPKG-RESISTOR0805")
      (footprint "eagle-import:TESTPKG-R0805")
      (libsource (lib "eagle-import") (part "TESTPKG-RESISTOR0805"))
    )
    (comp (ref "R381")
      (value "TESTPKG-RESISTOR0805")
      (footprint "eagle-import:TESTPKG-R0805")
      (libsource (lib "eagle-import") (part "TESTPKG-RESISTOR0805"))
    )
    (comp (ref "R382")
      (value "TESTPKG-RESISTOR0805")
      (footprint "eagle-import:TESTPKG-R0805")
      (libsource (lib "eagle-import") (part "TESTPKG-RESISTOR0805"))
    )
    (comp (ref "R383")
      (value "TESTPKG-RESISTOR0805")
      (footprint "eagle-import:TESTPKG-R0805")
      (libsource (lib "eagle-import") (part "TESTPKG-RESISTOR0805"))
    )
    (comp (ref "R384")
      (value "TESTPKG-RESISTOR0805")
      (footprint "eagle-import:TESTPKG-R0805")
      (libsource (lib "eagle-import") (part "TESTPKG-RESISTOR0805"))
    )
    (comp (ref "R385")
      (value "TESTPKG-RESISTOR0805")
      (footprint "eagle-import:TESTPKG-R0805")
      (libsource (lib "eagle-import") (part "TESTPKG-RESISTOR0805"))
    )
    (comp (ref "R386")
      (value "TESTPKG-RESISTOR0805")
      (footprint "eagle-import:TESTPKG-R0805")
      (libsource (lib "eagle-import") (part "TESTPKG-RESISTOR0805"))
    )
    (comp (ref "R387")
      (value "TESTPKG-RESISTOR0805")
      (footprint "eagle-import:TESTPKG-R0805")
      (libsource (lib "eagle-import") (part "TESTPKG-RESISTOR0805"))
    )
    (comp (ref "R388")
      (value "TESTPKG-RESISTOR0805")
      (footprint "eagle-import:TESTPKG-R0805")
      (libsource (lib "eagle-import") (part "TESTPKG-RESISTOR0805"))
    )
    (comp (ref "R389")
      (value "TESTPKG-RESISTOR0805")
      (footprint "eagle-import:TESTPKG-R0805")
      (libsource (lib "eagle-import") (part "TESTPKG-RESISTOR0805"))
    )
    (comp (ref "R390")
      (value "TESTPKG-RESISTOR0805")
      (footprint "eagle-import:TESTPKG-R0805")
      (libsource (lib "eagle-import") (part "TESTPKG-RESISTOR0805"))
    )
    (comp (ref "R391")
      (value "TESTPKG-RESISTOR0805")
      (footprint "eagle-import:TESTPKG-R0805")
      (libsource (lib "eagle-import") (part "TESTPKG-RESISTOR0805"))
    )
    (comp (ref "R392")
      (value "TESTPKG-RESISTOR0805")
      (footprint "eagle-import:TESTPKG-R0805")
      (libsource (lib "eagle-import") (part "TESTPKG-RESISTOR0805"))
    )
    (comp (ref "R393")
      (value "TESTPKG-RESISTOR0805")
      (footprint "eagle-import:TESTPKG-R0805")
      (libsource (lib "eagle-import") (part "TESTPKG-RESISTOR0805"))
    )
    (comp (ref "R394")
      (value "TESTPKG-RESISTOR0805")
      (footprint "eagle-import:TESTPKG-R0805")
      (libsource (lib "eagle-import") (part "TESTPKG-RESISTOR0805"))
    )
    (comp (ref "R395")
      (value "TESTPKG-RESISTOR0805")
      (footprint "eagle-import:TESTPKG-R0805")
      (libsource (lib "eagle-import") (part "TESTPKG-RESISTOR0805"))
    )
    (comp (ref "R396")
      (value "TESTPKG-RESISTOR0805")
      (footprint "eagle-import:TESTPKG-R0805")
      (libsource (lib "eagle-import") (part "TESTPKG-RESISTOR0805"))
    )
    (comp (ref "R397")
      (value "TESTPKG-RESISTOR0805")
      (footprint "eagle-import:TESTPKG-R0805")
      (libsource (lib "eagle-import") (part "TESTPKG-RESISTOR0805"))
    )
    (comp (ref "R398")
      (value "TESTPKG-RESISTOR0805")
      (footprint "eagle-import:TESTPKG-R0805")
      (libsource (lib "eagle-import") (part "TESTPKG-RESISTOR0805"))
    )
    (comp (ref "R399")
      (value "TESTPKG-RESISTOR0805")
      (footprint "eagle-import:TESTPKG-R0805")
      (libsource (lib "eagle-import") (part "TESTPKG-RESISTOR0805"))
    )
    (comp (ref "R400")
      (value "TESTPKG-RESISTOR0805")
      (footprint "eagle-import:TESTPKG-R0805")
      (libsource (lib "eagle-import") (part "TESTPKG-RESISTOR0805"))
    )
    (comp (ref "R401")
      (value "TESTPKG-RESISTOR0805")
      (footprint "eagle-import:TESTPKG-R0805")
      (libsource (lib "eagle-import") (part "TESTPKG-RESISTOR0805"))
    )
    (comp (ref "R402")
      (value "TESTPKG-RESISTOR0805")
      (footprint "eagle-import:TESTPKG-R0805")
      (libsource (lib "eagle-import") (part "TESTPKG-RESISTOR0805"))
    )
    (comp (ref "R403")
      (value "TESTPKG-RESISTOR0805")
      (footprint "eagle-import:TESTPKG-R0805")
      (libsource (lib "eagle-import") (part "TESTPKG-RESISTOR0805"))
    )
    (comp (ref "R404")
      (value "TESTPKG-RESISTOR0805")
      (footprint "eagle-import:TESTPKG-R0805")
      (libsource (lib "eagle-import") (part "TESTPKG-RESISTOR0805"))
    )
    (comp (ref "R405")
      (value "TESTPKG-RESISTOR0805")
      (footprint "eagle-import:TESTPKG-R0805")
      (libsource (lib "eagle-import") (part "TESTPKG-RESISTOR0805"))
    )
    (comp (ref "R406")
      (value "TESTPKG-RESISTOR0805")
      (footprint "eagle-import:TESTPKG-R0805")
      (libsource (lib "eagle-import") (part "TESTPKG-RESISTOR0805"))
    )
    (comp (ref "R407")
      (value "TESTPKG-RESISTOR0805")
      (footprint "eagle-import:TESTPKG-R0805")
      (libsource (lib "eagle-import") (part "TESTPKG-RESISTOR0805"))
    )
    (comp (ref "R408")
      (value "TESTPKG-RESISTOR0805")
      (footprint "eagle-import:TESTPKG-R0805")
      (libsource (lib "eagle-import") (part "TESTPKG-RESISTOR0805"))
    )
    (comp (ref "R409")
      (value "TESTPKG-RESISTOR0805")
      (footprint "eagle-import:TESTPKG-R0805")
      (libsource (lib "eagle-import") (part "TESTPKG-RESISTOR0805"))
    )
    (comp (ref "R410")
      (value "TESTPKG-RESISTOR0805")
      (footprint "eagle-import:TESTPKG-R0805")
      (libsource (lib "eagle-import") (part "TESTPKG-RESISTOR0805"))
    )
    (comp (ref "R411")
      (value "TESTPKG-RESISTOR0805")
      (footprint "eagle-import:TESTPKG-R0805")
      (libsource (lib "eagle-import") (part "TESTPKG-RESISTOR0805"))
    )
    (comp (ref "R412")
      (value "TESTPKG-RESISTOR0805")
      (footprint "eagle-import:TESTPKG-R0805")
      (libsource (lib "eagle-import") (part "TESTPKG-RESISTOR0805"))
    )
    (comp (ref "R413")
      (value "TESTPKG-RESISTOR0805")
      (footprint "eagle-import:TESTPKG-R0805")
      (libsource (lib "eagle-import") (part "TESTPKG-RESISTOR0805"))
    )
    (comp (ref "R414")
      (value "TESTPKG-RESISTOR0805")
      (footprint "eagle-import:TESTPKG-R0805")
      (libsource (lib "eagle-import") (part "TESTPKG-RESISTOR0805"))
    )
    (comp (ref "R415")
      (value "TESTPKG-RESISTOR0805")
      (footprint "eagle-import:TESTPKG-R0805")
      (libsource (lib "eagle-import") (part "TESTPKG-RESISTOR0805"))
    )
    (comp (ref "R416")
      (value "TESTPKG-RESISTOR0805")
      (footprint "eagle-import:TESTPKG-R0805")
      (libsource (lib "eagle-import") (part "TESTPKG-RESISTOR0805"))
    )
    (comp (ref "R417")
      (value "TESTPKG-RESISTOR0805")
      (footprint "eagle-import:TESTPKG-R0805")
      (libsource (lib "eagle-import") (part "TESTPKG-RESISTOR0805"))
    )
    (comp (ref "R418")
      (value "TESTPKG-RESISTOR0805")
      (footprint "eagle-import:TESTPKG-R0805")
      (libsource (lib "eagle-import") (part "TESTPKG-RESISTOR0805"))
    )
    (comp (ref "R419")
      (value "TESTPKG-RESISTOR0805")
      (footprint "eagle-import:TESTPKG-R0805")
      (libsource (lib "eagle-import") (part "TESTPKG-RESISTOR0805"))
    )
    (comp (ref "R420")
      (value "TESTPKG-RESISTOR0805")
      (footprint "eagle-import:TESTPKG-R0805")
      (libsource (lib "eagle-import") (part "TESTPKG-RESISTOR0805"))
    )
    (comp (ref "R421")
      (value "TESTPKG-RESISTOR0805")
      (footprint "eagle-import:TESTPKG-R0805")
      (libsource (lib "eagle-import") (part "TESTPKG-RESISTOR0805"))
    )
    (comp (ref "R422")
      (value "TESTPKG-RESISTOR0805")
      (footprint "eagle-import:TESTPKG-R0805")
      (libsource (lib "eagle-import") (part "TESTPKG-RESISTOR0805"))
    )
    (comp (ref "R423")
      (value "TESTPKG-RESISTOR0805")
      (footprint "eagle-import:TESTPKG-R0805")
      (libsource (lib "eagle-import") (part "TESTPKG-RESISTOR0805"))
    )
    (comp (ref "R424")
      (value "TESTPKG-RESISTOR0805")
      (footprint "eagle-import:TESTPKG-R0805")
      (libsource (lib "eagle-import") (part "TESTPKG-RESISTOR0805"))
    )
    (comp (ref "R425")
      (value "TESTPKG-RESISTOR0805")
      (footprint "eagle-import:TESTPKG-R0805")
      (libsource (lib "eagle-import") (part "TESTPKG-RESISTOR0805"))
    )
    (comp (ref "R426")
      (value "TESTPKG-RESISTOR0805")
      (footprint "eagle-import:TESTPKG-R0805")
      (libsource (lib "eagle-import") (part "TESTPKG-RESISTOR0805"))
    )
    (comp (ref "R427")
      (value "TESTPKG-RESISTOR0805")
      (footprint "eagle-import:TESTPKG-R0805")
      (libsource (lib "eagle-import") (part "TESTPKG-RESISTOR0805"))
    )
    (comp (ref "R428")
      (value "TESTPKG-RESISTOR0805")
      (footprint "eagle-import:TESTPKG-R0805")
      (libsource (lib "eagle-import") (part "TESTPKG-RESISTOR0805"))
    )
    (comp (ref "R429")
      (value "TESTPKG-RESISTOR0805")
      (footprint "eagle-import:TESTPKG-R0805")
      (libsource (lib "eagle-import") (part "TESTPKG-RESISTOR0805"))
    )
    (comp (ref "R430")
      (value "TESTPKG-RESISTOR0805")
      (footprint "eagle-import:TESTPKG-R0805")
      (libsource (lib "eagle-import") (part "TESTPKG-RESISTOR0805"))
    )
    (comp (ref "R431")
      (value "TESTPKG-RESISTOR0805")
      (footprint "eagle-import:TESTPKG-R0805")
      (libsource (lib "eagle-import") (part "TESTPKG-RESISTOR0805"))
    )
    (comp (ref "R432")
      (value "TESTPKG-RESISTOR0805")
      (footprint "eagle-import:TESTPKG-R0805")
      (libsource (lib "eagle-import") (part "TESTPKG-RESISTOR0805"))
    )
    (comp (ref "R433")
      (value "TESTPKG-RESISTOR0805")
      (footprint "eagle-import:TESTPKG-R0805")
      (libsource (lib "eagle-import") (part "TESTPKG-RESISTOR0805"))
    )
    (comp (ref "R434")
      (value "TESTPKG-RESISTOR0805")
      (footprint "eagle-import:TESTPKG-R0805")
      (libsource (lib "eagle-import") (part "TESTPKG-RESISTOR0805"))
    )
    (comp (ref "R435")
      (value "TESTPKG-RESISTOR0805")
      (footprint "eagle-import:TESTPKG-R0805")
      (libsource (lib "eagle-import") (part "TESTPKG-RESISTOR0805"))
    )
    (comp (ref "R436")
      (value "TESTPKG-RESISTOR0805")
      (footprint "eagle-import:TESTPKG-R0805")
      (libsource (lib "eagle-import") (part "TESTPKG-RESISTOR0805"))
    )
    (comp (ref "R437")
      (value "TESTPKG-RESISTOR0805")
      (footprint "eagle-import:TESTPKG-R0805")
      (libsource (lib "eagle-import") (part "TESTPKG-RESISTOR0805"))
    )
    (comp (ref "R438")
      (value "TESTPKG-RESISTOR0805")
      (footprint "eagle-import:TESTPKG-R0805")
      (libsource (lib "eagle-import") (part "TESTPKG-RESISTOR0805"))
    )
    (comp (ref "R439")
      (value "TESTPKG-RESISTOR0805")
      (footprint "eagle-import:TESTPKG-R0805")
      (libsource (lib "eagle-import") (part "TESTPKG-RESISTOR0805"))
    )
    (comp (ref "R440")
      (value "TESTPKG-RESISTOR0805")
      (footprint "eagle-import:TESTPKG-R0805")
      (libsource (lib "eagle-import") (part "TESTPKG-RESISTOR0805"))
    )
    (comp (ref "R441")
      (value "TESTPKG-RESISTOR0805")
      (footprint "eagle-import:TESTPKG-R0805")
      (libsource (lib "eagle-import") (part "TESTPKG-RESISTOR0805"))
    )
    (comp (ref "R442")
      (value "TESTPKG-RESISTOR0805")
      (footprint "eagle-import:TESTPKG-R0805")
      (libsource (lib "eagle-import") (part "TESTPKG-RESISTOR0805"))
    )
    (comp (ref "R443")
      (value "TESTPKG-RESISTOR0805")
      (footprint "eagle-import:TESTPKG-R0805")
      (libsource (lib "eagle-import") (part "TESTPKG-RESISTOR0805"))
    )
    (comp (ref "R444")
      (value "TESTPKG-RESISTOR0805")
      (footprint "eagle-import:TESTPKG-R0805")
      (libsource (lib "eagle-import") (part "TESTPKG-RESISTOR0805"))
    )
    (comp (ref "R445")
      (value "TESTPKG-RESISTOR0805")
      (footprint "eagle-import:TESTPKG-R0805")
      (libsource (lib "eagle-import") (part "TESTPKG-RESISTOR0805"))
    )
    (comp (ref "R446")
      (value "TESTPKG-RESISTOR0805")
      (footprint "eagle-import:TESTPKG-R0805")
      (libsource (lib "eagle-import") (part "TESTPKG-RESISTOR0805"))
    )
    (comp (ref "R447")
      (value "TESTPKG-RESISTOR0805")
      (footprint "eagle-import:TESTPKG-R0805")
      (libsource (lib "eagle-import") (part "TESTPKG-RESISTOR0805"))
    )
    (comp (ref "R448")
      (value "TESTPKG-RESISTOR0805")
      (footprint "eagle-import:TESTPKG-R0805")
      (libsource (lib "eagle-import") (part "TESTPKG-RESISTOR0805"))
    )
    (comp (ref "R449")
      (value "TESTPKG-RESISTOR0805")
      (footprint "eagle-import:TESTPKG-R0805")
      (libsource (lib "eagle-import") (part "TESTPKG-RESISTOR0805"))
    )
    (comp (ref "R450")
      (value "TESTPKG-RESISTOR0805")
      (footprint "eagle-import:TESTPKG-R0805")
      (libsource (lib "eagle-import") (part "TESTPKG-RESISTOR0805"))
    )
    (comp (ref "R451")
      (value "TESTPKG-RESISTOR0805")
      (footprint "eagle-import:TESTPKG-R0805")
      (libsource (lib "eagle-import") (part "TESTPKG-RESISTOR0805"))
    )
    (comp (ref "R452")
      (value "TESTPKG-RESISTOR0805")
      (footprint "eagle-import:TESTPKG-R0805")
      (libsource (lib "eagle-import") (part "TESTPKG-RESISTOR0805"))
    )
    (comp (ref "R453")
      (value "TESTPKG-RESISTOR0805")
      (footprint "eagle-import:TESTPKG-R0805")
      (libsource (lib "eagle-import") (part "TESTPKG-RESISTOR0805"))
    )
    (comp (ref "R454")
      (value "TESTPKG-RESISTOR0805")
      (footprint "eagle-import:TESTPKG-R0805")
      (libsource (lib "eagle-import") (part "TESTPKG-RESISTOR0805"))
    )
    (comp (ref "R455")
      (value "TESTPKG-RESISTOR0805")
      (footprint "eagle-import:TESTPKG-R0805")
      (libsource (lib "eagle-import") (part "TESTPKG-RESISTOR0805"))
    )
    (comp (ref "R456")
      (value "TESTPKG-RESISTOR0805")
      (footprint "eagle-import:TESTPKG-R0805")
      (libsource (lib "eagle-import") (part "TESTPKG-RESISTOR0805"))
    )
    (comp (ref "R457")
      (value "TESTPKG-RESISTOR0805")
      (footprint "eagle-import:TESTPKG-R0805")
      (libsource (lib "eagle-import") (part "TESTPKG-RESISTOR0805"))
    )
    (comp (ref "R458")
      (value "TESTPKG-RESISTOR0805")
      (footprint "eagle-import:TESTPKG-R0805")
      (libsource (lib "eagle-import") (part "TESTPKG-RESISTOR0805"))
    )
    (comp (ref "R459")
      (value "TESTPKG-RESISTOR0805")
      (footprint "eagle-import:TESTPKG-R0805")
      (libsource (lib "eagle-import") (part "TESTPKG-RESISTOR0805"))
    )
    (comp (ref "R460")
      (value "TESTPKG-RESISTOR0805")
      (footprint "eagle-import:TESTPKG-R0805")
      (libsource (lib "eagle-import") (part "TESTPKG-RESISTOR0805"))
    )
    (comp (ref "R461")
      (value "TESTPKG-RESISTOR0805")
      (footprint "eagle-import:TESTPKG-R0805")
      (libsource (lib "eagle-import") (part "TESTPKG-RESISTOR0805"))
    )
    (comp (ref "R462")
      (value "TESTPKG-RESISTOR0805")
      (footprint "eagle-import:TESTPKG-R0805")
      (libsource (lib "eagle-import") (part "TESTPKG-RESISTOR0805"))
    )
    (comp (ref "R463")
      (value "TESTPKG-RESISTOR0805")
      (footprint "eagle-import:TESTPKG-R0805")
      (libsource (lib "eagle-import") (part "TESTPKG-RESISTOR0805"))
    )
    (comp (ref "R464")
      (value "TESTPKG-RESISTOR0805")
      (footprint "eagle-import:TESTPKG-R0805")
      (libsource (lib "eagle-import") (part "TESTPKG-RESISTOR0805"))
    )
    (comp (ref "R465")
      (value "TESTPKG-RESISTOR0805")
      (footprint "eagle-import:TESTPKG-R0805")
      (libsource (lib "eagle-import") (part "TESTPKG-RESISTOR0805"))
    )
    (comp (ref "R466")
      (value "TESTPKG-RESISTOR0805")
      (footprint "eagle-import:TESTPKG-R0805")
      (libsource (lib "eagle-import") (part "TESTPKG-RESISTOR0805"))
    )
    (comp (ref "R467")
      (value "TESTPKG-RESISTOR0805")
      (footprint "eagle-import:TESTPKG-R0805")
      (libsource (lib "eagle-import") (part "TESTPKG-RESISTOR0805"))
    )
    (comp (ref "R468")
      (value "TESTPKG-RESISTOR0805")
      (footprint "eagle-import:TESTPKG-R0805")
      (libsource (lib "eagle-import") (part "TESTPKG-RESISTOR0805"))
    )
    (comp (ref "R469")
      (value "TESTPKG-RESISTOR0805")
      (footprint "eagle-import:TESTPKG-R0805")
      (libsource (lib "eagle-import") (part "TESTPKG-RESISTOR0805"))
    )
    (comp (ref "R470")
      (value "TESTPKG-RESISTOR0805")
      (footprint "eagle-import:TESTPKG-R0805")
      (libsource (lib "eagle-import") (part "TESTPKG-RESISTOR0805"))
    )
    (comp (ref "R471")
      (value "TESTPKG-RESISTOR0805")
      (footprint "eagle-import:TESTPKG-R0805")
      (libsource (lib "eagle-import") (part "TESTPKG-RESISTOR0805"))
    )
    (comp (ref "R472")
      (value "TESTPKG-RESISTOR0805")
      (footprint "eagle-import:TESTPKG-R0805")
      (libsource (lib "eagle-import") (part "TESTPKG-RESISTOR0805"))
    )
    (comp (ref "R473")
      (value "TESTPKG-RESISTOR0805")
      (footprint "eagle-import:TESTPKG-R0805")
      (libsource (lib "eagle-import") (part "TESTPKG-RESISTOR0805"))
    )
    (comp (ref "R474")
      (value "TESTPKG-RESISTOR0805")
      (footprint "eagle-import:TESTPKG-R0805")
      (libsource (lib "eagle-import") (part "TESTPKG-RESISTOR0805"))
    )
    (comp (ref "R475")
      (value "TESTPKG-RESISTOR0805")
      (footprint "eagle-import:TESTPKG-R0805")
      (libsource (lib "eagle-import") (part "TESTPKG-RESISTOR0805"))
    )
    (comp (ref "R476")
      (value "TESTPKG-RESISTOR0805")
      (footprint "eagle-import:TESTPKG-R0805")
      (libsource (lib "eagle-import") (part "TESTPKG-RESISTOR0805"))
    )
    (comp (ref "R477")
      (value "TESTPKG-RESISTOR0805")
      (footprint "eagle-import:TESTPKG-R0805")
      (libsource (lib "eagle-import") (part "TESTPKG-RESISTOR0805"))
    )
    (comp (ref "R478")
      (value "TESTPKG-RESISTOR0805")
      (footprint "eagle-import:TESTPKG-R0805")
      (libsource (lib "eagle-import") (part "TESTPKG-RESISTOR0805"))
    )
    (comp (ref "R479")
      (value "TESTPKG-RESISTOR0805")
      (footprint "eagle-import:TESTPKG-R0805")
      (libsource (lib "eagle-import") (part "TESTPKG-RESISTOR0805"))
    )
    (comp (ref "R480")
      (value "TESTPKG-RESISTOR0805")
      (footprint "eagle-import:TESTPKG-R0805")
      (libsource (lib "eagle-import") (part "TESTPKG-RESISTOR0805"))
    )
    (comp (ref "R481")
      (value "TESTPKG-RESISTOR0805")
      (footprint "eagle-import:TESTPKG-R0805")
      (libsource (lib "eagle-import") (part "TESTPKG-RESISTOR0805"))
    )
    (comp (ref "R482")
      (value "TESTPKG-RESISTOR0805")
      (footprint "eagle-import:TESTPKG-R0805")
      (libsource (lib "eagle-import") (part "TESTPKG-RESISTOR0805"))
    )
    (comp (ref "R483")
      (value "TESTPKG-RESISTOR0805")
      (footprint "eagle-import:TESTPKG-R0805")
      (libsource (lib "eagle-import") (part "TESTPKG-RESISTOR0805"))
    )
    (comp (ref "R484")
      (value "TESTPKG-RESISTOR0805")
      (footprint "eagle-import:TESTPKG-R0805")
      (libsource (lib "eagle-import") (part "TESTPKG-RESISTOR0805"))
    )
    (comp (ref "R485")
      (value "TESTPKG-RESISTOR0805")
      (footprint "eagle-import:TESTPKG-R0805")
      (libsource (lib "eagle-import") (part "TESTPKG-RESISTOR0805"))
    )
    (comp (ref "R486")
      (value "TESTPKG-RESISTOR0805")
      (footprint "eagle-import:TESTPKG-R0805")
      (libsource (lib "eagle-import") (part "TESTPKG-RESISTOR0805"))
    )
    (comp (ref "R487")
      (value "TESTPKG-RESISTOR0805")
      (footprint "eagle-import:TESTPKG-R0805")
      (libsource (lib "eagle-import") (part "TESTPKG-RESISTOR0805"))
    )
    (comp (ref "R488")
      (value "TESTPKG-RESISTOR0805")
      (footprint "eagle-import:TESTPKG-R0805")
      (libsource (lib "eagle-import") (part "TESTPKG-RESISTOR0805"))
    )
    (comp (ref "R489")
      (value "TESTPKG-RESISTOR0805")
      (footprint "eagle-import:TESTPKG-R0805")
      (libsource (lib "eagle-import") (part "TESTPKG-RESISTOR0805"))
    )
    (comp (ref "R490")
      (value "TESTPKG-RESISTOR0805")
      (footprint "eagle-import:TESTPKG-R0805")
      (libsource (lib "eagle-import") (part "TESTPKG-RESISTOR0805"))
    )
    (comp (ref "R491")
      (value "TESTPKG-RESISTOR0805")
      (footprint "eagle-import:TESTPKG-R0805")
      (libsource (lib "eagle-import") (part "TESTPKG-RESISTOR0805"))
    )
    (comp (ref "R492")
      (value "TESTPKG-RESISTOR0805")
      (footprint "eagle-import:TESTPKG-R0805")
      (libsource (lib "eagle-import") (part "TESTPKG-RESISTOR0805"))
    )
    (comp (ref "R493")
      (value "TESTPKG-RESISTOR0805")
      (footprint "eagle-import:TESTPKG-R0805")
      (libsource (lib "eagle-import") (part "TESTPKG-RESISTOR0805"))
    )
    (comp (ref "R494")
      (value "TESTPKG-RESISTOR0805")
      (footprint "eagle-import:TESTPKG-R0805")
      (libsource (lib "eagle-import") (part "TESTPKG-RESISTOR0805"))
    )
    (comp (ref "R495")
      (value "TESTPKG-RESISTOR0805")
      (footprint "eagle-import:TESTPKG-R0805")
      (libsource (lib "eagle-import") (part "TESTPKG-RESISTOR0805"))
    )
    (comp (ref "R496")
      (value "TESTPKG-RESISTOR0805")
      (footprint "eagle-import:TESTPKG-R0805")
      (libsource (lib "eagle-import") (part "TESTPKG-RESISTOR0805"))
    )
    (comp (ref "R497")
      (value "TESTPKG-RESISTOR0805")
      (footprint "eagle-import:TESTPKG-R0805")
      (libsource (lib "eagle-import") (part "TESTPKG-RESISTOR0805"))
    )
    (comp (ref "R498")
      (value "TESTPKG-RESISTOR0805")
      (footprint "eagle-import:TESTPKG-R0805")
      (libsource (lib "eagle-import") (part "TESTPKG-RESISTOR0805"))
    )
    (comp (ref "R499")
      (value "TESTPKG-RESISTOR0805")
      (footprint "eagle-import:TESTPKG-R0805")
      (libsource (lib "eagle-import") (part "TESTPKG-RESISTOR0805"))
    )
    (comp (ref "R500")
      (value "TESTPKG-RESISTOR0805")
      (footprint "eagle-import:TESTPKG-R0805")
      (libsource (lib "eagle-import") (part "TESTPKG-RESISTOR0805"))
    )
    (comp (ref "R501")
      (value "TESTPKG-RESISTOR0805")
      (footprint "eagle-import:TESTPKG-R0805")
      (libsource (lib "eagle-import") (part "TESTPKG-RESISTOR0805"))
    )
    (comp (ref "R502")
      (value "TESTPKG-RESISTOR0805")
      (footprint "eagle-import:TESTPKG-R0805")
      (libsource (lib "eagle-import") (part "TESTPKG-RESISTOR0805"))
    )
    (comp (ref "R503")
      (value "TESTPKG-RESISTOR0805")
      (footprint "eagle-import:TESTPKG-R0805")
      (libsource (lib "eagle-import") (part "TESTPKG-RESISTOR0805"))
    )
    (comp (ref "R504")
      (value "TESTPKG-RESISTOR0805")
      (footprint "eagle-import:TESTPKG-R0805")
      (libsource (lib "eagle-import") (part "TESTPKG-RESISTOR0805"))
    )
    (comp (ref "R505")
      (value "TESTPKG-RESISTOR0805")
      (footprint "eagle-import:TESTPKG-R0805")
      (libsource (lib "eagle-import") (part "TESTPKG-RESISTOR0805"))
    )
    (comp (ref "R506")
      (value "TESTPKG-RESISTOR0805")
      (footprint "eagle-import:TESTPKG-R0805")
      (libsource (lib "eagle-import") (part "TESTPKG-RESISTOR0805"))
    )
    (comp (ref "R507")
      (value "TESTPKG-RESISTOR0805")
      (footprint "eagle-import:TESTPKG-R0805")
      (libsource (lib "eagle-import") (part "TESTPKG-RESISTOR0805"))
    )
    (comp (ref "R508")
      (value "TESTPKG-RESISTOR0805")
      (footprint "eagle-import:TESTPKG-R0805")
      (libsource (lib "eagle-import") (part "TESTPKG-RESISTOR0805"))
    )
    (comp (ref "R509")
      (value "TESTPKG-RESISTOR0805")
      (footprint "eagle-import:TESTPKG-R0805")
      (libsource (lib "eagle-import") (part "TESTPKG-RESISTOR0805"))
    )
    (comp (ref "R510")
      (value "TESTPKG-RESISTOR0805")
      (footprint "eagle-import:TESTPKG-R0805")
      (libsource (lib "eagle-import") (part "TESTPKG-RESISTOR0805"))
    )
    (comp (ref "R511")
      (value "TESTPKG-RESISTOR0805")
      (footprint "eagle-import:TESTPKG-R0805")
      (libsource (lib "eagle-import") (part "TESTPKG-RESISTOR0805"))
    )
    (comp (ref "R512")
      (value "TESTPKG-RESISTOR0805")
      (footprint "eagle-import:TESTPKG-R0805")
      (libsource (lib "eagle-import") (part "TESTPKG-RESISTOR0805"))
    )
    (comp (ref "R513")
      (value "TESTPKG-RESISTOR0805")
      (footprint "eagle-import:TESTPKG-R0805")
      (libsource (lib "eagle-import") (part "TESTPKG-RESISTOR0805"))
    )
    (comp (ref "R514")
      (value "TESTPKG-RESISTOR0805")
      (footprint "eagle-import:TESTPKG-R0805")
      (libsource (lib "eagle-import") (part "TESTPKG-RESISTOR0805"))
    )
    (comp (ref "R515")
      (value "TESTPKG-RESISTOR0805")
      (footprint "eagle-import:TESTPKG-R0805")
      (libsource (lib "eagle-import") (part "TESTPKG-RESISTOR0805"))
    )
    (comp (ref "R516")
      (value "TESTPKG-RESISTOR0805")
      (footprint "eagle-import:TESTPKG-R0805")
      (libsource (lib "eagle-import") (part "TESTPKG-RESISTOR0805"))
    )
    (comp (ref "R517")
      (value "TESTPKG-RESISTOR0805")
      (footprint "eagle-import:TESTPKG-R0805")
      (libsource (lib "eagle-import") (part "TESTPKG-RESISTOR0805"))
    )
    (comp (ref "R518")
      (value "TESTPKG-RESISTOR0805")
      (footprint "eagle-import:TESTPKG-R0805")
      (libsource (lib "eagle-import") (part "TESTPKG-RESISTOR0805"))
    )
    (comp (ref "R519")
      (value "TESTPKG-RESISTOR0805")
      (footprint "eagle-import:TESTPKG-R0805")
      (libsource (lib "eagle-import") (part "TESTPKG-RESISTOR0805"))
    )
    (comp (ref "R520")
      (value "TESTPKG-RESISTOR0805")
      (footprint "eagle-import:TESTPKG-R0805")
      (libsource (lib "eagle-import") (part "TESTPKG-RESISTOR0805"))
    )
    (comp (ref "R521")
      (value "TESTPKG-RESISTOR0805")
      (footprint "eagle-import:TESTPKG-R0805")
      (libsource (lib "eagle-import") (part "TESTPKG-RESISTOR0805"))
    )
    (comp (ref "R522")
      (value "TESTPKG-RESISTOR0805")
      (footprint "eagle-import:TESTPKG-R0805")
      (libsource (lib "eagle-import") (part "TESTPKG-RESISTOR0805"))
    )
    (comp (ref "R523")
      (value "TESTPKG-RESISTOR0805")
      (footprint "eagle-import:TESTPKG-R0805")
      (libsource (lib "eagle-import") (part "TESTPKG-RESISTOR0805"))
    )
    (comp (ref "R524")
      (value "TESTPKG-RESISTOR0805")
      (footprint "eagle-import:TESTPKG-R0805")
      (libsource (lib "eagle-import") (part "TESTPKG-RESISTOR0805"))
    )
    (comp (ref "R525")
      (value "TESTPKG-RESISTOR0805")
      (footprint "eagle-import:TESTPKG-R0805")
      (libsource (lib "eagle-import") (part "TESTPKG-RESISTOR0805"))
    )
    (comp (ref "R526")
      (value "TESTPKG-RESISTOR0805")
      (footprint "eagle-import:TESTPKG-R0805")
      (libsource (lib "eagle-import") (part "TESTPKG-RESISTOR0805"))
    )
    (comp (ref "R527")
      (value "TESTPKG-RESISTOR0805")
      (footprint "eagle-import:TESTPKG-R0805")
      (libsource (lib "eagle-import") (part "TESTPKG-RESISTOR0805"))
    )
    (comp (ref "R528")
      (value "TESTPKG-RESISTOR0805")
      (footprint "eagle-import:TESTPKG-R0805")
      (libsource (lib "eagle-import") (part "TESTPKG-RESISTOR0805"))
    )
    (comp (ref "R529")
      (value "TESTPKG-RESISTOR0805")
      (footprint "eagle-import:TESTPKG-R0805")
      (libsource (lib "eagle-import") (part "TESTPKG-RESISTOR0805"))
    )
    (comp (ref "R530")
      (value "TESTPKG-RESISTOR0805")
      (footprint "eagle-import:TESTPKG-R0805")
      (libsource (lib "eagle-import") (part "TESTPKG-RESISTOR0805"))
    )
    (comp (ref "R531")
      (value "TESTPKG-RESISTOR0805")
      (footprint "eagle-import:TESTPKG-R0805")
      (libsource (lib "eagle-import") (part "TESTPKG-RESISTOR0805"))
    )
    (comp (ref "R532")
      (value "TESTPKG-RESISTOR0805")
      (footprint "eagle-import:TESTPKG-R0805")
      (libsource (lib "eagle-import") (part "TESTPKG-RESISTOR0805"))
    )
    (comp (ref "R533")
      (value "TESTPKG-RESISTOR0805")
      (footprint "eagle-import:TESTPKG-R0805")
      (libsource (lib "eagle-import") (part "TESTPKG-RESISTOR0805"))
    )
    (comp (ref "R534")
      (value "TESTPKG-RESISTOR0805")
      (footprint "eagle-import:TESTPKG-R0805")
      (libsource (lib "eagle-import") (part "TESTPKG-RESISTOR0805"))
    )
    (comp (ref "R535")
      (value "TESTPKG-RESISTOR0805")
      (footprint "eagle-import:TESTPKG-R0805")
      (libsource (lib "eagle-import") (part "TESTPKG-RESISTOR0805"))
    )
    (comp (ref "R536")
      (value "TESTPKG-RESISTOR0805")
      (footprint "eagle-import:TESTPKG-R0805")
      (libsource (lib "eagle-import") (part "TESTPKG-RESISTOR0805"))
    )
    (comp (ref "R537")
      (value "TESTPKG-RESISTOR0805")
      (footprint "eagle-import:TESTPKG-R0805")
      (libsource (lib "eagle-import") (part "TESTPKG-RESISTOR0805"))
    )
    (comp (ref "R538")
      (value "TESTPKG-RESISTOR0805")
      (footprint "eagle-import:TESTPKG-R0805")
      (libsource (lib "eagle-import") (part "TESTPKG-RESISTOR0805"))
    )
    (comp (ref "R539")
      (value "TESTPKG-RESISTOR0805")
      (footprint "eagle-import:TESTPKG-R0805")
      (libsource (lib "eagle-import") (part "TESTPKG-RESISTOR0805"))
    )
    (comp (ref "R540")
      (value "TESTPKG-RESISTOR0805")
      (footprint "eagle-import:TESTPKG-R0805")
      (libsource (lib "eagle-import") (part "TESTPKG-RESISTOR0805"))
    )
    (comp (ref "R541")
      (value "TESTPKG-RESISTOR0805")
      (footprint "eagle-import:TESTPKG-R0805")
      (libsource (lib "eagle-import") (part "TESTPKG-RESISTOR0805"))
    )
    (comp (ref "R542")
      (value "TESTPKG-RESISTOR0805")
      (footprint "eagle-import:TESTPKG-R0805")
      (libsource (lib "eagle-import") (part "TESTPKG-RESISTOR0805"))
    )
    (comp (ref "R543")
      (value "TESTPKG-RESISTOR0805")
      (footprint "eagle-import:TESTPKG-R0805")
      (libsource (lib "eagle-import") (part "TESTPKG-RESISTOR0805"))
    )
    (comp (ref "R544")
      (value "TESTPKG-RESISTOR0805")
      (footprint "eagle-import:TESTPKG-R0805")
      (libsource (lib "eagle-import") (part "TESTPKG-RESISTOR0805"))
    )
    (comp (ref "R545")
      (value "TESTPKG-RESISTOR0805")
      (footprint "eagle-import:TESTPKG-R0805")
      (libsource (lib "eagle-import") (part "TESTPKG-RESISTOR0805"))
    )
    (comp (ref "R546")
      (value "TESTPKG-RESISTOR0805")
      (footprint "eagle-import:TESTPKG-R0805")
      (libsource (lib "eagle-import") (part "TESTPKG-RESISTOR0805"))
    )
    (comp (ref "R547")
      (value "TESTPKG-RESISTOR0805")
      (footprint "eagle-import:TESTPKG-R0805")
      (libsource (lib "eagle-import") (part "TESTPKG-RESISTOR0805"))
    )
    (comp (ref "R548")
      (value "TESTPKG-RESISTOR0805")
      (footprint "eagle-import:TESTPKG-R0805")
      (libsource (lib "eagle-import") (part "TESTPKG-RESISTOR0805"))
    )
    (comp (ref "R549")
      (value "TESTPKG-RESISTOR0805")
      (footprint "eagle-import:TESTPKG-R0805")
      (libsource (lib "eagle-import") (part "TESTPKG-RESISTOR0805"))
    )
    (comp (ref "R550")
      (value "TESTPKG-RESISTOR0805")
      (footprint "eagle-import:TESTPKG-R0805")
      (libsource (lib "eagle-import") (part "TESTPKG-RESISTOR0805"))
    )
    (comp (ref "R551")
      (value "TESTPKG-RESISTOR0805")
      (footprint "eagle-import:TESTPKG-R0805")
      (libsource (lib "eagle-import") (part "TESTPKG-RESISTOR0805"))
    )
    (comp (ref "R552")
      (value "TESTPKG-RESISTOR0805")
      (footprint "eagle-import:TESTPKG-R0805")
      (libsource (lib "eagle-import") (part "TESTPKG-RESISTOR0805"))
    )
    (comp (ref "R553")
      (value "TESTPKG-RESISTOR0805")
      (footprint "eagle-import:TESTPKG-R0805")
      (libsource (lib "eagle-import") (part "TESTPKG-RESISTOR0805"))
    )
    (comp (ref "R554")
      (value "TESTPKG-RESISTOR0805")
      (footprint "eagle-import:TESTPKG-R0805")
      (libsource (lib "eagle-import") (part "TESTPKG-RESISTOR0805"))
    )
    (comp (ref "R555")
      (value "TESTPKG-RESISTOR0805")
      (footprint "eagle-import:TESTPKG-R0805")
      (libsource (lib "eagle-import") (part "TESTPKG-RESISTOR0805"))
    )
    (comp (ref "R556")
      (value "TESTPKG-RESISTOR0805")
      (footprint "eagle-import:TESTPKG-R0805")
      (libsource (lib "eagle-import") (part "TESTPKG-RESISTOR0805"))
    )
    (comp (ref "R557")
      (value "TESTPKG-RESISTOR0805")
      (footprint "eagle-import:TESTPKG-R0805")
      (libsource (lib "eagle-import") (part "TESTPKG-RESISTOR0805"))
    )
    (comp (ref "R558")
      (value "TESTPKG-RESISTOR0805")
      (footprint "eagle-import:TESTPKG-R0805")
      (libsource (lib "eagle-import") (part "TESTPKG-RESISTOR0805"))
    )
    (comp (ref "R559")
      (value "TESTPKG-RESISTOR0805")
      (footprint "eagle-import:TESTPKG-R0805")
      (libsource (lib "eagle-import") (part "TESTPKG-RESISTOR0805"))
    )
    (comp (ref "R560")
      (value "TESTPKG-RESISTOR0805")
      (footprint "eagle-import:TESTPKG-R0805")
      (libsource (lib "eagle-import") (part "TESTPKG-RESISTOR0805"))
    )
    (comp (ref "R561")
      (value "TESTPKG-RESISTOR0805")
      (footprint "eagle-import:TESTPKG-R0805")
      (libsource (lib "eagle-import") (part "TESTPKG-RESISTOR0805"))
    )
    (comp (ref "R562")
      (value "TESTPKG-RESISTOR0805")
      (footprint "eagle-import:TESTPKG-R0805")
      (libsource (lib "eagle-import") (part "TESTPKG-RESISTOR0805"))
    )
    (comp (ref "R563")
      (value "TESTPKG-RESISTOR0805")
      (footprint "eagle-import:TESTPKG-R0805")
      (libsource (lib "eagle-import") (part "TESTPKG-RESISTOR0805"))
    )
    (comp (ref "R564")
      (value "TESTPKG-RESISTOR0805")
      (footprint "eagle-import:TESTPKG-R0805")
      (libsource (lib "eagle-import") (part "TESTPKG-RESISTOR0805"))
    )
    (comp (ref "R565")
      (value "TESTPKG-RESISTOR0805")
      (footprint "eagle-import:TESTPKG-R0805")
      (libsource (lib "eagle-import") (part "TESTPKG-RESISTOR0805"))
    )
    (comp (ref "R566")
      (value "TESTPKG-RESISTOR0805")
      (footprint "eagle-import:TESTPKG-R0805")
      (libsource (lib "eagle-import") (part "TESTPKG-RESISTOR0805"))
    )
    (comp (ref "R567")
      (value "TESTPKG-RESISTOR0805")
      (footprint "eagle-import:TESTPKG-R0805")
      (libsource (lib "eagle-import") (part "TESTPKG-RESISTOR0805"))
    )
    (comp (ref "R568")
      (value "TESTPKG-RESISTOR0805")
      (footprint "eagle-import:TESTPKG-R0805")
      (libsource (lib "eagle-import") (part "TESTPKG-RESISTOR0805"))
    )
    (comp (ref "R569")
      (value "TESTPKG-RESISTOR0805")
      (footprint "eagle-import:TESTPKG-R0805")
      (libsource (lib "eagle-import") (part "TESTPKG-RESISTOR0805"))
    )
    (comp (ref "R570")
      (value "TESTPKG-RESISTOR0805")
      (footprint "eagle-import:TESTPKG-R0805")
      (libsource (lib "eagle-import") (part "TESTPKG-RESISTOR0805"))
    )
    (comp (ref "R571")
      (value "TESTPKG-RESISTOR0805")
      (footprint "eagle-import:TESTPKG-R0805")
      (libsource (lib "eagle-import") (part "TESTPKG-RESISTOR0805"))
    )
    (comp (ref "R572")
      (value "TESTPKG-RESISTOR0805")
      (footprint "eagle-import:TESTPKG-R0805")
      (libsource (lib "eagle-import") (part "TESTPKG-RESISTOR0805"))
    )
    (comp (ref "R573")
      (value "TESTPKG-RESISTOR0805")
      (footprint "eagle-import:TESTPKG-R0805")
      (libsource (lib "eagle-import") (part "TESTPKG-RESISTOR0805"))
    )
    (comp (ref "R574")
      (value "TESTPKG-RESISTOR0805")
      (footprint "eagle-import:TESTPKG-R0805")
      (libsource (lib "eagle-import") (part "TESTPKG-RESISTOR0805"))
    )
    (comp (ref "R575")
      (value "TESTPKG-RESISTOR0805")
      (footprint "eagle-import:TESTPKG-R0805")
      (libsource (lib "eagle-import") (part "TESTPKG-RESISTOR0805"))
    )
    (comp (ref "R576")
      (value "TESTPKG-RESISTOR0805")
      (footprint "eagle-import:TESTPKG-R0805")
      (libsource (lib "eagle-import") (part "TESTPKG-RESISTOR0805"))
    )
    (comp (ref "R577")
      (value "TESTPKG-RESISTOR0805")
      (footprint "eagle-import:TESTPKG-R0805")
      (libsource (lib "eagle-import") (part "TESTPKG-RESISTOR0805"))
    )
    (comp (ref "R578")
      (value "TESTPKG-RESISTOR0805")
      (footprint "eagle-import:TESTPKG-R0805")
      (libsource (lib "eagle-import") (part "TESTPKG-RESISTOR0805"))
    )
    (comp (ref "R579")
      (value "TESTPKG-RESISTOR0805")
      (footprint "eagle-import:TESTPKG-R0805")
      (libsource (lib "eagle-import") (part "TESTPKG-RESISTOR0805"))
    )
    (comp (ref "R580")
      (value "TESTPKG-RESISTOR0805")
      (footprint "eagle-import:TESTPKG-R0805")
      (libsource (lib "eagle-import") (part "TESTPKG-RESISTOR0805"))
    )
    (comp (ref "R581")
      (value "TESTPKG-RESISTOR0805")
      (footprint "eagle-import:TESTPKG-R0805")
      (libsource (lib "eagle-import") (part "TESTPKG-RESISTOR0805"))
    )
    (comp (ref "R582")
      (value "TESTPKG-RESISTOR0805")
      (footprint "eagle-import:TESTPKG-R0805")
      (libsource (lib "eagle-import") (part "TESTPKG-RESISTOR0805"))
    )
    (comp (ref "R583")
      (value "TESTPKG-RESISTOR0805")
      (footprint "eagle-import:TESTPKG-R0805")
      (libsource (lib "eagle-import") (part "TESTPKG-RESISTOR0805"))
    )
    (comp (ref "R584")
      (value "TESTPKG-RESISTOR0805")
      (footprint "eagle-import:TESTPKG-R0805")
      (libsource (lib "eagle-import") (part "TESTPKG-RESISTOR0805"))
    )
    (comp (ref "R585")
      (value "TESTPKG-RESISTOR0805")
      (footprint "eagle-import:TESTPKG-R0805")
      (libsource (lib "eagle-import") (part "TESTPKG-RESISTOR0805"))
    )
    (comp (ref "R586")
      (value "TESTPKG-RESISTOR0805")
      (footprint "eagle-import:TESTPKG-R0805")
      (libsource (lib "eagle-import") (part "TESTPKG-RESISTOR0805"))
    )
    (comp (ref "R587")
      (value "TESTPKG-RESISTOR0805")
      (footprint "eagle-import:TESTPKG-R0805")
      (libsource (lib "eagle-import") (part "TESTPKG-RESISTOR0805"))
    )
    (comp (ref "R588")
      (value "TESTPKG-RESISTOR0805")
      (footprint "eagle-import:TESTPKG-R0805")
      (libsource (lib "eagle-import") (part "TESTPKG-RESISTOR0805"))
    )
    (comp (ref "R589")
      (value "TESTPKG-RESISTOR0805")
      (footprint "eagle-import:TESTPKG-R0805")
      (libsource (lib "eagle-import") (part "TESTPKG-RESISTOR0805"))
    )
    (comp (ref "R590")
      (value "TESTPKG-RESISTOR0805")
      (footprint "eagle-import:TESTPKG-R0805")
      (libsource (lib "eagle-import") (part "TESTPKG-RESISTOR0805"))
    )
    (comp (ref "R591")
      (value "TESTPKG-RESISTOR0805")
      (footprint "eagle-import:TESTPKG-R0805")
      (libsource (lib "eagle-import") (part "TESTPKG-RESISTOR0805"))
    )
    (comp (ref "R592")
      (value "TESTPKG-RESISTOR0805")
      (footprint "eagle-import:TESTPKG-R0805")
      (libsource (lib "eagle-import") (part "TESTPKG-RESISTOR0805"))
    )
    (comp (ref "R593")
      (value "TESTPKG-RESISTOR0805")
      (footprint "eagle-import:TESTPKG-R0805")
      (libsource (lib "eagle-import") (part "TESTPKG-RESISTOR0805"))
    )
    (comp (ref "R594")
      (value "TESTPKG-RESISTOR0805")
      (footprint "eagle-import:TESTPKG-R0805")
      (libsource (lib "eagle-import") (part "TESTPKG-RESISTOR0805"))
    )
    (comp (ref "R595")
      (value "TESTPKG-RESISTOR0805")
      (footprint "eagle-import:TESTPKG-R0805")
      (libsource (lib "eagle-import") (part "TESTPKG-RESISTOR0805"))
    )
    (comp (ref "R596")
      (value "TESTPKG-RESISTOR0805")
      (footprint "eagle-import:TESTPKG-R0805")
      (libsource (lib "eagle-import") (part "TESTPKG-RESISTOR0805"))
    )
    (comp (ref "R597")
      (value "TESTPKG-RESISTOR0805")
      (footprint "eagle-import:TESTPKG-R0805")
      (libsource (lib "eagle-import") (part "TESTPKG-RESISTOR0805"))
    )
    (comp (ref "R598")
      (value "TESTPKG-RESISTOR0805")
      (footprint "eagle-import:TESTPKG-R0805")
      (libsource (lib "eagle-import") (part "TESTPKG-RESISTOR0805"))
    )
    (comp (ref "R599")
      (value "TESTPKG-RESISTOR0805")
      (footprint "eagle-import:TESTPKG-R0805")
      (libsource (lib "eagle-import") (part "TESTPKG-RESISTOR0805"))
    )
    (comp (ref "R600")
      (value "TESTPKG-RESISTOR0805")
      (footprint "eagle-import:TESTPKG-R0805")
      (libsource (lib "eagle-import") (part "TESTPKG-RESISTOR0805"))
    )
    (comp (ref "R601")
      (value "TESTPKG-RESISTOR0805")
      (footprint "eagle-import:TESTPKG-R0805")
      (libsource (lib "eagle-import") (part "TESTPKG-RESISTOR0805"))
    )
    (comp (ref "R602")
      (value "TESTPKG-RESISTOR0805")
      (footprint "eagle-import:TESTPKG-R0805")
      (libsource (lib "eagle-import") (part "TESTPKG-RESISTOR0805"))
    )
    (comp (ref "R603")
      (value "TESTPKG-RESISTOR0805")
      (footprint "eagle-import:TESTPKG-R0805")
      (libsource (lib "eagle-import") (part "TESTPKG-RESISTOR0805"))
    )
    (comp (ref "R604")
      (value "TESTPKG-RESISTOR0805")
      (footprint "eagle-import:TESTPKG-R0805")
      (libsource (lib "eagle-import") (part "TESTPKG-RESISTOR0805"))
    )
    (comp (ref "R605")
      (value "TESTPKG-RESISTOR0805")
      (footprint "eagle-import:TESTPKG-R0805")
      (libsource (lib "eagle-import") (part "TESTPKG-RESISTOR0805"))
    )
    (comp (ref "R606")
      (value "TESTPKG-RESISTOR0805")
      (footprint "eagle-import:TESTPKG-R0805")
      (libsource (lib "eagle-import") (part "TESTPKG-RESISTOR0805"))
    )
    (comp (ref "R607")
      (value "TESTPKG-RESISTOR0805")
      (footprint "eagle-import:TESTPKG-R0805")
      (libsource (lib "eagle-import") (part "TESTPKG-RESISTOR0805"))
    )
    (comp (ref "R608")
      (value "TESTPKG-RESISTOR0805")
      (footprint "eagle-import:TESTPKG-R0805")
      (libsource (lib "eagle-import") (part "TESTPKG-RESISTOR0805"))
    )
    (comp (ref "R609")
      (value "TESTPKG-RESISTOR0805")
      (footprint "eagle-import:TESTPKG-R0805")
      (libsource (lib "eagle-import") (part "TESTPKG-RESISTOR0805"))
    )
    (comp (ref "R610")
      (value "TESTPKG-RESISTOR0805")
      (footprint "eagle-import:TESTPKG-R0805")
      (libsource (lib "eagle-import") (part "TESTPKG-RESISTOR0805"))
    )
    (comp (ref "R611")
      (value "TESTPKG-RESISTOR0805")
      (footprint "eagle-import:TESTPKG-R0805")
      (libsource (lib "eagle-import") (part "TESTPKG-RESISTOR0805"))
    )
    (comp (ref "R612")
      (value "TESTPKG-RESISTOR0805")
      (footprint "eagle-import:TESTPKG-R0805")
      (libsource (lib "eagle-import") (part "TESTPKG-RESISTOR0805"))
    )
    (comp (ref "R613")
      (value "TESTPKG-RESISTOR0805")
      (footprint "eagle-import:TESTPKG-R0805")
      (libsource (lib "eagle-import") (part "TESTPKG-RESISTOR0805"))
    )
    (comp (ref "R614")
      (value "TESTPKG-RESISTOR0805")
      (footprint "eagle-import:TESTPKG-R0805")
      (libsource (lib "eagle-import") (part "TESTPKG-RESISTOR0805"))
    )
    (comp (ref "R615")
      (value "TESTPKG-RESISTOR0805")
      (footprint "eagle-import:TESTPKG-R0805")
      (libsource (lib "eagle-import") (part "TESTPKG-RESISTOR0805"))
    )
    (comp (ref "R616")
      (value "TESTPKG-RESISTOR0805")
      (footprint "eagle-import:TESTPKG-R0805")
      (libsource (lib "eagle-import") (part "TESTPKG-RESISTOR0805"))
    )
    (comp (ref "R617")
      (value "TESTPKG-RESISTOR0805")
      (footprint "eagle-import:TESTPKG-R0805")
      (libsource (lib "eagle-import") (part "TESTPKG-RESISTOR0805"))
    )
    (comp (ref "R618")
      (value "TESTPKG-RESISTOR0805")
      (footprint "eagle-import:TESTPKG-R0805")
      (libsource (lib "eagle-import") (part "TESTPKG-RESISTOR0805"))
    )
    (comp (ref "R619")
      (value "TESTPKG-RESISTOR0805")
      (footprint "eagle-import:TESTPKG-R0805")
      (libsource (lib "eagle-import") (part "TESTPKG-RESISTOR0805"))
    )
    (comp (ref "R620")
      (value "TESTPKG-RESISTOR0805")
      (footprint "eagle-import:TESTPKG-R0805")
      (libsource (lib "eagle-import") (part "TESTPKG-RESISTOR0805"))
    )
    (comp (ref "R621")
      (value "TESTPKG-RESISTOR0805")
      (footprint "eagle-import:TESTPKG-R0805")
      (libsource (lib "eagle-import") (part "TESTPKG-RESISTOR0805"))
    )
    (comp (ref "R622")
      (value "TESTPKG-RESISTOR0805")
      (footprint "eagle-import:TESTPKG-R0805")
      (libsource (lib "eagle-import") (part "TESTPKG-RESISTOR0805"))
    )
    (comp (ref "R623")
      (value "TESTPKG-RESISTOR0805")
      (footprint "eagle-import:TESTPKG-R0805")
      (libsource (lib "eagle-import") (part "TESTPKG-RESISTOR0805"))
    )
    (comp (ref "R624")
      (value "TESTPKG-RESISTOR0805")
      (footprint "eagle-import:TESTPKG-R0805")
      (libsource (lib "eagle-import") (part "TESTPKG-RESISTOR0805"))
    )
    (comp (ref "R625")
      (value "TESTPKG-RESISTOR0805")
      (footprint "eagle-import:TESTPKG-R0805")
      (libsource (lib "eagle-import") (part "TESTPKG-RESISTOR0805"))
    )
    (comp (ref "R626")
      (value "TESTPKG-RESISTOR0805")
      (footprint "eagle-import:TESTPKG-R0805")
      (libsource (lib "eagle-import") (part "TESTPKG-RESISTOR0805"))
    )
    (comp (ref "R627")
      (value "TESTPKG-RESISTOR0805")
      (footprint "eagle-import:TESTPKG-R0805")
      (libsource (lib "eagle-import") (part "TESTPKG-RESISTOR0805"))
    )
    (comp (ref "R628")
      (value "TESTPKG-RESISTOR0805")
      (footprint "eagle-import:TESTPKG-R0805")
      (libsource (lib "eagle-import") (part "TESTPKG-RESISTOR0805"))
    )
    (comp (ref "R629")
      (value "TESTPKG-RESISTOR0805")
      (footprint "eagle-import:TESTPKG-R0805")
      (libsource (lib "eagle-import") (part "TESTPKG-RESISTOR0805"))
    )
    (comp (ref "R630")
      (value "TESTPKG-RESISTOR0805")
      (footprint "eagle-import:TESTPKG-R0805")
      (libsource (lib "eagle-import") (part "TESTPKG-RESISTOR0805"))
    )
    (comp (ref "R631")
      (value "TESTPKG-RESISTOR0805")
      (footprint "eagle-import:TESTPKG-R0805")
      (libsource (lib "eagle-import") (part "TESTPKG-RESISTOR0805"))
    )
    (comp (ref "R632")
      (value "TESTPKG-RESISTOR0805")
      (footprint "eagle-import:TESTPKG-R0805")
      (libsource (lib "eagle-import") (part "TESTPKG-RESISTOR0805"))
    )
    (comp (ref "R633")
      (value "TESTPKG-RESISTOR0805")
      (footprint "eagle-import:TESTPKG-R0805")
      (libsource (lib "eagle-import") (part "TESTPKG-RESISTOR0805"))
    )
    (comp (ref "R634")
      (value "TESTPKG-RESISTOR0805")
      (footprint "eagle-import:TESTPKG-R0805")
      (libsource (lib "eagle-import") (part "TESTPKG-RESISTOR0805"))
    )
    (comp (ref "R635")
      (value "TESTPKG-RESISTOR0805")
      (footprint "eagle-import:TESTPKG-R0805")
      (libsource (lib "eagle-import") (part "TESTPKG-RESISTOR0805"))
    )
    (comp (ref "R636")
      (value "TESTPKG-RESISTOR0805")
      (footprint "eagle-import:TESTPKG-R0805")
      (libsource (lib "eagle-import") (part "TESTPKG-RESISTOR0805"))
    )
    (comp (ref "R637")
      (value "TESTPKG-RESISTOR0805")
      (footprint "eagle-import:TESTPKG-R0805")
      (libsource (lib "eagle-import") (part "TESTPKG-RESISTOR0805"))
    )
    (comp (ref "R638")
      (value "TESTPKG-RESISTOR0805")
      (footprint "eagle-import:TESTPKG-R0805")
      (libsource (lib "eagle-import") (part "TESTPKG-RESISTOR0805"))
    )
    (comp (ref "R639")
      (value "TESTPKG-RESISTOR0805")
      (footprint "eagle-import:TESTPKG-R0805")
      (libsource (lib "eagle-import") (part "TESTPKG-RESISTOR0805"))
    )
    (comp (ref "R640")
      (value "TESTPKG-RESISTOR0805")
      (footprint "eagle-import:TESTPKG-R0805")
      (libsource (lib "eagle-import") (part "TESTPKG-RESISTOR0805"))
    )
    (comp (ref "R641")
      (value "TESTPKG-RESISTOR0805")
      (footprint "eagle-import:TESTPKG-R0805")
      (libsource (lib "eagle-import") (part "TESTPKG-RESISTOR0805"))
    )
    (comp (ref "R642")
      (value "TESTPKG-RESISTOR0805")
      (footprint "eagle-import:TESTPKG-R0805")
      (libsource (lib "eagle-import") (part "TESTPKG-RESISTOR0805"))
    )
    (comp (ref "R643")
      (value "TESTPKG-RESISTOR0805")
      (footprint "eagle-import:TESTPKG-R0805")
      (libsource (lib "eagle-import") (part "TESTPKG-RESISTOR0805"))
    )
    (comp (ref "R644")
      (value "TESTPKG-RESISTOR0805")
      (footprint "eagle-import:TESTPKG-R0805")
      (libsource (lib "eagle-import") (part "TESTPKG-RESISTOR0805"))
    )
    (comp (ref "R645")
      (value "TESTPKG-RESISTOR0805")
      (footprint "eagle-import:TESTPKG-R0805")
      (libsource (lib "eagle-import") (part "TESTPKG-RESISTOR0805"))
    )
    (comp (ref "R646")
      (value "TESTPKG-RESISTOR0805")
      (footprint "eagle-import:TESTPKG-R0805")
      (libsource (lib "eagle-import") (part "TESTPKG-RESISTOR0805"))
    )
    (comp (ref "R647")
      (value "TESTPKG-RESISTOR0805")
      (footprint "eagle-import:TESTPKG-R0805")
      (libsource (lib "eagle-import") (part "TESTPKG-RESISTOR0805"))
    )
    (comp (ref "R648")
      (value "TESTPKG-RESISTOR0805")
      (footprint "eagle-import:TESTPKG-R0805")
      (libsource (lib "eagle-import") (part "TESTPKG-RESISTOR0805"))
    )
    (comp (ref "R649")
      (value "TESTPKG-RESISTOR0805")
      (footprint "eagle-import:TESTPKG-R0805")
      (libsource (lib "eagle-import") (part "TESTPKG-RESISTOR0805"))
    )
    (comp (ref "R650")
      (value "TESTPKG-RESISTOR0805")
      (footprint "eagle-import:TESTPKG-R0805")
      (libsource (lib "eagle-import") (part "TESTPKG-RESISTOR0805"))
    )
    (comp (ref "R651")
      (value "TESTPKG-RESISTOR0805")
      (footprint "eagle-import:TESTPKG-R0805")
      (libsource (lib "eagle-import") (part "TESTPKG-RESISTOR0805"))
    )
    (comp (ref "R652")
      (value "TESTPKG-RESISTOR0805")
      (footprint "eagle-import:TESTPKG-R0805")
      (libsource (lib "eagle-import") (part "TESTPKG-RESISTOR0805"))
    )
    (comp (ref "R653")
      (value "TESTPKG-RESISTOR0805")
      (footprint "eagle-import:TESTPKG-R0805")
      (libsource (lib "eagle-import") (part "TESTPKG-RESISTOR0805"))
    )
    (comp (ref "R654")
      (value "TESTPKG-RESISTOR0805")
      (footprint "eagle-import:TESTPKG-R0805")
      (libsource (lib "eagle-import") (part "TESTPKG-RESISTOR0805"))
    )
    (comp (ref "R655")
      (value "TESTPKG-RESISTOR0805")
      (footprint "eagle-import:TESTPKG-R0805")
      (libsource (lib "eagle-import") (part "TESTPKG-RESISTOR0805"))
    )
    (comp (ref "R656")
      (value "TESTPKG-RESISTOR0805")
      (footprint "eagle-import:TESTPKG-R0805")
      (libsource (lib "eagle-import") (part "TESTPKG-RESISTOR0805"))
    )
    (comp (ref "R657")
      (value "TESTPKG-RESISTOR0805")
      (footprint "eagle-import:TESTPKG-R0805")
      (libsource (lib "eagle-import") (part "TESTPKG-RESISTOR0805"))
    )
    (comp (ref "R658")
      (value "TESTPKG-RESISTOR0805")
      (footprint "eagle-import:TESTPKG-R0805")
      (libsource (lib "eagle-import") (part "TESTPKG-RESISTOR0805"))
    )
    (comp (ref "R659")
      (value "TESTPKG-RESISTOR0805")
      (footprint "eagle-import:TESTPKG-R0805")
      (libsource (lib "eagle-import") (part "TESTPKG-RESISTOR0805"))
    )
    (comp (ref "R660")
      (value "TESTPKG-RESISTOR0805")
      (footprint "eagle-import:TESTPKG-R0805")
      (libsource (lib "eagle-import") (part "TESTPKG-RESISTOR0805"))
    )
    (comp (ref "R661")
      (value "TESTPKG-RESISTOR0805")
      (footprint "eagle-import:TESTPKG-R0805")
      (libsource (lib "eagle-import") (part "TESTPKG-RESISTOR0805"))
    )
    (comp (ref "R662")
      (value "TESTPKG-RESISTOR0805")
      (footprint "eagle-import:TESTPKG-R0805")
      (libsource (lib "eagle-import") (part "TESTPKG-RESISTOR0805"))
    )
    (comp (ref "R663")
      (value "TESTPKG-RESISTOR0805")
      (footprint "eagle-import:TESTPKG-R0805")
      (libsource (lib "eagle-import") (part "TESTPKG-RESISTOR0805"))
    )
    (comp (ref "R664")
      (value "TESTPKG-RESISTOR0805")
      (footprint "eagle-import:TESTPKG-R0805")
      (libsource (lib "eagle-import") (part "TESTPKG-RESISTOR0805"))
    )
    (comp (ref "R665")
      (value "TESTPKG-RESISTOR0805")
      (footprint "eagle-import:TESTPKG-R0805")
      (libsource (lib "eagle-import") (part "TESTPKG-RESISTOR0805"))
    )
    (comp (ref "R666")
      (value "TESTPKG-RESISTOR0805")
      (footprint "eagle-import:TESTPKG-R0805")
      (libsource (lib "eagle-import") (part "TESTPKG-RESISTOR0805"))
    )
    (comp (ref "R667")
      (value "TESTPKG-RESISTOR0805")
      (footprint "eagle-import:TESTPKG-R0805")
      (libsource (lib "eagle-import") (part "TESTPKG-RESISTOR0805"))
    )
    (comp (ref "R668")
      (value "TESTPKG-RESISTOR0805")
      (footprint "eagle-import:TESTPKG-R0805")
      (libsource (lib "eagle-import") (part "TESTPKG-RESISTOR0805"))
    )
    (comp (ref "R669")
      (value "TESTPKG-RESISTOR0805")
      (footprint "eagle-import:TESTPKG-R0805")
      (libsource (lib "eagle-import") (part "TESTPKG-RESISTOR0805"))
    )
    (comp (ref "R670")
      (value "TESTPKG-RESISTOR0805")
      (footprint "eagle-import:TESTPKG-R0805")
      (libsource (lib "eagle-import") (part "TESTPKG-RESISTOR0805"))
    )
    (comp (ref "R671")
      (value "TESTPKG-RESISTOR0805")
      (footprint "eagle-import:TESTPKG-R0805")
      (libsource (lib "eagle-import") (part "TESTPKG-RESISTOR0805"))
    )
    (comp (ref "R672")
      (value "TESTPKG-RESISTOR0805")
      (footprint "eagle-import:TESTPKG-R0805")
      (libsource (lib "eagle-import") (part "TESTPKG-RESISTOR0805"))
    )
    (comp (ref "R673")
      (value "TESTPKG-RESISTOR0805")
      (footprint "eagle-import:TESTPKG-R0805")
      (libsource (lib "eagle-import") (part "TESTPKG-RESISTOR0805"))
    )
    (comp (ref "R674")
      (value "TESTPKG-RESISTOR0805")
      (footprint "eagle-import:TESTPKG-R0805")
      (libsource (lib "eagle-import") (part "TESTPKG-RESISTOR0805"))
    )
    (comp (ref "R675")
      (value "TESTPKG-RESISTOR0805")
      (footprint "eagle-import:TESTPKG-R0805")
      (libsource (lib "eagle-import") (part "TESTPKG-RESISTOR0805"))
    )
    (comp (ref "R676")
      (value "TESTPKG-RESISTOR0805")
      (footprint "eagle-import:TESTPKG-R0805")
      (libsource (lib "eagle-import") (part "TESTPKG-RESISTOR0805"))
    )
    (comp (ref "R677")
      (value "TESTPKG-RESISTOR0805")
      (footprint "eagle-import:TESTPKG-R0805")
      (libsource (lib "eagle-import") (part "TESTPKG-RESISTOR0805"))
    )
    (comp (ref "R678")
      (value "TESTPKG-RESISTOR0805")
      (footprint "eagle-import:TESTPKG-R0805")
      (libsource (lib "eagle-import") (part "TESTPKG-RESISTOR0805"))
    )
    (comp (ref "R679")
      (value "TESTPKG-RESISTOR0805")
      (footprint "eagle-import:TESTPKG-R0805")
      (libsource (lib "eagle-import") (part "TESTPKG-RESISTOR0805"))
    )
    (comp (ref "R680")
      (value "TESTPKG-RESISTOR0805")
      (footprint "eagle-import:TESTPKG-R0805")
      (libsource (lib "eagle-import") (part "TESTPKG-RESISTOR0805"))
    )
    (comp (ref "R681")
      (value "TESTPKG-RESISTOR0805")
      (footprint "eagle-import:TESTPKG-R0805")
      (libsource (lib "eagle-import") (part "TESTPKG-RESISTOR0805"))
    )
    (comp (ref "R682")
      (value "TESTPKG-RESISTOR0805")
      (footprint "eagle-import:TESTPKG-R0805")
      (libsource (lib "eagle-import") (part "TESTPKG-RESISTOR0805"))
    )
    (comp (ref "R683")
      (value "TESTPKG-RESISTOR0805")
      (footprint "eagle-import:TESTPKG-R0805")
      (libsource (lib "eagle-import") (part "TESTPKG-RESISTOR0805"))
    )
    (comp (ref "R684")
      (value "TESTPKG-RESISTOR0805")
      (footprint "eagle-import:TESTPKG-R0805")
      (libsource (lib "eagle-import") (part "TESTPKG-RESISTOR0805"))
    )
    (comp (ref "R685")
      (value "TESTPKG-RESISTOR0805")
      (footprint "eagle-import:TESTPKG-R0805")
      (libsource (lib "eagle-import") (part "TESTPKG-RESISTOR0805"))
    )
    (comp (ref "R686")
      (value "TESTPKG-RESISTOR0805")
      (footprint "eagle-import:TESTPKG-R0805")
      (libsource (lib "eagle-import") (part "TESTPKG-RESISTOR0805"))
    )
    (comp (ref "R687")
      (value "TESTPKG-RESISTOR0805")
      (footprint "eagle-import:TESTPKG-R0805")
      (libsource (lib "eagle-import") (part "TESTPKG-RESISTOR0805"))
    )
    (comp (ref "R688")
      (value "TESTPKG-RESISTOR0805")
      (footprint "eagle-import:TESTPKG-R0805")
      (libsource (lib "eagle-import") (part "TESTPKG-RESISTOR0805"))
    )
    (comp (ref "R689")
      (value "TESTPKG-RESISTOR0805")
      (footprint "eagle-import:TESTPKG-R0805")
      (libsource (lib "eagle-import") (part "TESTPKG-RESISTOR0805"))
    )
    (comp (ref "R690")
      (value "TESTPKG-RESISTOR0805")
      (footprint "eagle-import:TESTPKG-R0805")
      (libsource (lib "eagle-import") (part "TESTPKG-RESISTOR0805"))
    )
    (comp (ref "R691")
      (value "TESTPKG-RESISTOR0805")
      (footprint "eagle-import:TESTPKG-R0805")
      (libsource (lib "eagle-import") (part "TESTPKG-RESISTOR0805"))
    )
    (comp (ref "R692")
      (value "TESTPKG-RESISTOR0805")
      (footprint "eagle-import:TESTPKG-R0805")
      (libsource (lib "eagle-import") (part "TESTPKG-RESISTOR0805"))
    )
    (comp (ref "R693")
      (value "TESTPKG-RESISTOR0805")
      (footprint "eagle-import:TESTPKG-R0805")
      (libsource (lib "eagle-import") (part "TESTPKG-RESISTOR0805"))
    )
    (comp (ref "R694")
      (value "TESTPKG-RESISTOR0805")
      (footprint "eagle-import:TESTPKG-R0805")
      (libsource (lib "eagle-import") (part "TESTPKG-RESISTOR0805"))
    )
    (comp (ref "R695")
      (value "TESTPKG-RESISTOR0805")
      (footprint "eagle-import:TESTPKG-R0805")
      (libsource (lib "eagle-import") (part "TESTPKG-RESISTOR0805"))
    )
    (comp (ref "R696")
      (value "TESTPKG-RESISTOR0805")
      (footprint "eagle-import:TESTPKG-R0805")
      (libsource (lib "eagle-import") (part "TESTPKG-RESISTOR0805"))
    )
    (comp (ref "R697")
      (value "TESTPKG-RESISTOR0805")
      (footprint "eagle-import:TESTPKG-R0805")
      (libsource (lib "eagle-import") (part "TESTPKG-RESISTOR0805"))
    )
    (comp (ref "R698")
      (value "TESTPKG-RESISTOR0805")
      (footprint "eagle-import:TESTPKG-R0805")
      (libsource (lib "eagle-import") (part "TESTPKG-RESISTOR0805"))
    )
    (comp (ref "R699")
      (value "TESTPKG-RESISTOR0805")
      (footprint "eagle-import:TESTPKG-R0805")
      (libsource (lib "eagle-import") (part "TESTPKG-RESISTOR0805"))
    )
    (comp (ref "R700")
      (value "TESTPKG-RESISTOR0805")
      (footprint "eagle-import:TESTPKG-R0805")
      (libsource (lib "eagle-import") (part "TESTPKG-RESISTOR0805"))
    )
    (comp (ref "R701")
      (value "TESTPKG-RESISTOR0805")
      (footprint "eagle-import:TESTPKG-R0805")
      (libsource (lib "eagle-import") (part "TESTPKG-RESISTOR0805"))
    )
    (comp (ref "R702")
      (value "TESTPKG-RESISTOR0805")
      (footprint "eagle-import:TESTPKG-R0805")
      (libsource (lib "eagle-import") (part "TESTPKG-RESISTOR0805"))
    )
    (comp (ref "R703")
      (value "TESTPKG-RESISTOR0805")
      (footprint "eagle-import:TESTPKG-R0805")
      (libsource (lib "eagle-import") (part "TESTPKG-RESISTOR0805"))
    )
    (comp (ref "R704")
      (value "TESTPKG-RESISTOR0805")
      (footprint "eagle-import:TESTPKG-R0805")
      (libsource (lib "eagle-import") (part "TESTPKG-RESISTOR0805"))
    )
    (comp (ref "R705")
      (value "TESTPKG-RESISTOR0805")
      (footprint "eagle-import:TESTPKG-R0805")
      (libsource (lib "eagle-import") (part "TESTPKG-RESISTOR0805"))
    )
    (comp (ref "R706")
      (value "TESTPKG-RESISTOR0805")
      (footprint "eagle-import:TESTPKG-R0805")
      (libsource (lib "eagle-import") (part "TESTPKG-RESISTOR0805"))
    )
    (comp (ref "R707")
      (value "TESTPKG-RESISTOR0805")
      (footprint "eagle-import:TESTPKG-R0805")
      (libsource (lib "eagle-import") (part "TESTPKG-RESISTOR0805"))
    )
    (comp (ref "R708")
      (value "TESTPKG-RESISTOR0805")
      (footprint "eagle-import:TESTPKG-R0805")
      (libsource (lib "eagle-import") (part "TESTPKG-RESISTOR0805"))
    )
    (comp (ref "R709")
      (value "TESTPKG-RESISTOR0805")
      (footprint "eagle-import:TESTPKG-R0805")
      (libsource (lib "eagle-import") (part "TESTPKG-RESISTOR0805"))
    )
    (comp (ref "R710")
      (value "TESTPKG-RESISTOR0805")
      (footprint "eagle-import:TESTPKG-R0805")
      (libsource (lib "eagle-import") (part "TESTPKG-RESISTOR0805"))
    )
    (comp (ref "R711")
      (value "TESTPKG-RESISTOR0805")
      (footprint "eagle-import:TESTPKG-R0805")
      (libsource (lib "eagle-import") (part "TESTPKG-RESISTOR0805"))
    )
    (comp (ref "R712")
      (value "TESTPKG-RESISTOR0805")
      (footprint "eagle-import:TESTPKG-R0805")
      (libsource (lib "eagle-import") (part "TESTPKG-RESISTOR0805"))
    )
    (comp (ref "TP21")
      (value "CONN-TESTPOINT")
      (footprint "eagle-import:CON-TESTPOINT")
      (libsource (lib "eagle-import") (part "CONN-TESTPOINT"))
    )
    (comp (ref "TP22")
      (value "CONN-TESTPOINT")
      (footprint "eagle-import:CON-TESTPOINT")
      (libsource (lib "eagle-import") (part "CONN-TESTPOINT"))
    )
    (comp (ref "TP23")
      (value "CONN-TESTPOINT")
      (footprint "eagle-import:CON-TESTPOINT")
      (libsource (lib "eagle-import") (part "CONN-TESTPOINT"))
    )
    (comp (ref "TP24")
      (value "CONN-TESTPOINT")
      (footprint "eagle-import:CON-TESTPOINT")
      (libsource (lib "eagle-import") (part "CONN-TESTPOINT"))
    )
    (comp (ref "TP25")
      (value "CONN-TESTPOINT")
      (footprint "eagle-import:CON-TESTPOINT")
      (libsource (lib "eagle-import") (part "CONN-TESTPOINT"))
    )
    (comp (ref "TP26")
      (value "CONN-TESTPOINT")
      (footprint "eagle-import:CON-TESTPOINT")
      (libsource (lib "eagle-import") (part "CONN-TESTPOINT"))
    )
    (comp (ref "TP27")
      (value "CONN-TESTPOINT")
      (footprint "eagle-import:CON-TESTPOINT")
      (libsource (lib "eagle-import") (part "CONN-TESTPOINT"))
    )
    (comp (ref "TP28")
      (value "CONN-TESTPOINT")
      (footprint "eagle-import:CON-TESTPOINT")
      (libsource (lib "eagle-import") (part "CONN-TESTPOINT"))
    )
    (comp (ref "TP29")
      (value "CONN-TESTPOINT")
      (footprint "eagle-import:CON-TESTPOINT")
      (libsource (lib "eagle-import") (part "CONN-TESTPOINT"))
    )
    (comp (ref "TP30")
      (value "CONN-TESTPOINT")
      (footprint "eagle-import:CON-TESTPOINT")
      (libsource (lib "eagle-import") (part "CONN-TESTPOINT"))
    )
    (comp (ref "TP31")
      (value "CONN-TESTPOINT")
      (footprint "eagle-import:CON-TESTPOINT")
      (libsource (lib "eagle-import") (part "CONN-TESTPOINT"))
    )
    (comp (ref "TP32")
      (value "CONN-TESTPOINT")
      (footprint "eagle-import:CON-TESTPOINT")
      (libsource (lib "eagle-import") (part "CONN-TESTPOINT"))
    )
    (comp (ref "TP33")
      (value "CONN-TESTPOINT")
      (footprint "eagle-import:CON-TESTPOINT")
      (libsource (lib "eagle-import") (part "CONN-TESTPOINT"))
    )
    (comp (ref "TP34")
      (value "CONN-TESTPOINT")
      (footprint "eagle-import:CON-TESTPOINT")
      (libsource (lib "eagle-import") (part "CONN-TESTPOINT"))
    )
    (comp (ref "TP35")
      (value "CONN-TESTPOINT")
      (footprint "eagle-import:CON-TESTPOINT")
      (libsource (lib "eagle-import") (part "CONN-TESTPOINT"))
    )
    (comp (ref "TP36")
      (value "CONN-TESTPOINT")
      (footprint "eagle-import:CON-TESTPOINT")
      (libsource (lib "eagle-import") (part "CONN-TESTPOINT"))
    )
    (comp (ref "TP37")
      (value "CONN-TESTPOINT")
      (footprint "eagle-import:CON-TESTPOINT")
      (libsource (lib "eagle-import") (part "CONN-TESTPOINT"))
    )
    (comp (ref "TP38")
      (value "CONN-TESTPOINT")
      (footprint "eagle-import:CON-TESTPOINT")
      (libsource (lib "eagle-import") (part "CONN-TESTPOINT"))
    )
    (comp (ref "TP39")
      (value "CONN-TESTPOINT")
      (footprint "eagle-import:CON-TESTPOINT")
      (libsource (lib "eagle-import") (part "CONN-TESTPOINT"))
    )
    (comp (ref "TP40")
      (value "CONN-TESTPOINT")
      (footprint "eagle-import:CON-TESTPOINT")
      (libsource (lib "eagle-import") (part "CONN-TESTPOINT"))
    )
  )
  (nets
    (net (code "1") (name "Net-(R1-Pad2)") (class "Default")
      (node (ref "R1") (pin "2") (pinfunction "2_2") (pintype "passive"))
      (node (ref "R2") (pin "1") (pinfunction "1_1") (pintype "passive"))
    )
    (net (code "2") (name "Net-(R2-Pad2)") (class "Default")
      (node (ref "R2") (pin "2") (pinfunction "2_2") (pintype "passive"))
      (node (ref "R3") (pin "1") (pinfunction "1_1") (pintype "passive"))
    )
    (net (code "3") (name "Net-(R3-Pad2)") (class "Default")
      (node (ref "R3") (pin "2") (pinfunction "2_2") (pintype "passive"))
      (node (ref "R4") (pin "1") (pinfunction "1_1") (pintype "passive"))
    )
    (net (code "4") (name "Net-(R4-Pad2)") (class "Default")
      (node (ref "R4") (pin "2") (pinfunction "2_2") (pintype "passive"))
      (node (ref "R5") (pin "1") (pinfunction "1_1") (pintype "passive"))
    )
    (net (code "5") (name "Net-(R5-Pad2)") (class "Default")
      (node (ref "R5") (pin "2") (pinfunction "2_2") (pintype "passive"))
      (node (ref "R6") (pin "1") (pinfunction "1_1") (pintype "passive"))
    )
    (net (code "6") (name "Net-(R6-Pad2)") (class "Default")
      (node (ref "R6") (pin "2") (pinfunction "2_2") (pintype "passive"))
      (node (ref "R7") (pin "1") (pinfunction "1_1") (pintype "passive"))
    )
    (net (code "7") (name "Net-(R7-Pad2)") (class "Default")
      (node (ref "R7") (pin "2") (pinfunction "2_2") (pintype "passive"))
      (node (ref "R8") (pin "1") (pinfunction "1_1") (pintype "passive"))
    )
    (net (code "8") (name "Net-(R8-Pad2)") (class "Default")
      (node (ref "R8") (pin "2") (pinfunction "2_2") (pintype "passive"))
      (node (ref "R9") (pin "1") (pinfunction "1_1") (pintype "passive"))
    )
    (net (code "9") (name "Net-(R10-Pad1)") (class "Default")
      (node (ref "R10") (pin "1") (pinfunction "1_1") (pintype "passive"))
      (node (ref "R9") (pin "2") (pinfunction "2_2") (pintype "passive"))
    )
    (net (code "10") (name "Net-(R10-Pad2)") (class "Default")
      (node (ref "R10") (pin "2") (pinfunction "2_2") (pintype "passive"))
      (node (ref "R11") (pin "1") (pinfunction "1_1") (pintype "passive"))
    )
    (net (code "11") (name "Net-(R11-Pad2)") (class "Default")
      (node (ref "R11") (pin "2") (pinfunction "2_2") (pintype "passive"))
      (node (ref "R12") (pin "1") (pinfunction "1_1") (pintype "passive"))
    )
    (net (code "12") (name "Net-(R12-Pad2)") (class "Default")
      (node (ref "R12") (pin "2") (pinfunction "2_2") (pintype "passive"))
      (node (ref "R13") (pin "1") (pinfunction "1_1") (pintype "passive"))
    )
    (net (code "13") (name "Net-(R13-Pad2)") (class "Default")
      (node (ref "R13") (pin "2") (pinfunction "2_2") (pintype "passive"))
      (node (ref "R14") (pin "1") (pinfunction "1_1") (pintype "passive"))
    )
    (net (code "14") (name "Net-(R14-Pad2)") (class "Default")
      (node (ref "R14") (pin "2") (pinfunction "2_2") (pintype "passive"))
      (node (ref "R15") (pin "1") (pinfunction "1_1") (pintype "passive"))
    )
    (net (code "15") (name "Net-(R15-Pad2)") (class "Default")
      (node (ref "R15") (pin "2") (pinfunction "2_2") (pintype "passive"))
      (node (ref "R16") (pin "1") (pinfunction "1_1") (pintype "passive"))
    )
    (net (code "16") (name "Net-(R16-Pad2)") (class "Default")
      (node (ref "R16") (pin "2") (pinfunction "2_2") (pintype "passive"))
      (node (ref "R17") (pin "1") (pinfunction "1_1") (pintype "passive"))
    )
    (net (code "17") (name "Net-(R18-Pad2)") (class "Default")
      (node (ref "R18") (pin "2") (pinfunction "2_2") (pintype "passive"))
      (node (ref "R19") (pin "1") (pinfunction "1_1") (pintype "passive"))
    )
    (net (code "18") (name "Net-(R19-Pad2)") (class "Default")
      (node (ref "R19") (pin "2") (pinfunction "2_2") (pintype "passive"))
      (node (ref "R20") (pin "1") (pinfunction "1_1") (pintype "passive"))
    )
    (net (code "19") (name "Net-(R20-Pad2)") (class "Default")
      (node (ref "R20") (pin "2") (pinfunction "2_2") (pintype "passive"))
      (node (ref "R21") (pin "1") (pinfunction "1_1") (pintype "passive"))
    )
    (net (code "20") (name "Net-(R21-Pad2)") (class "Default")
      (node (ref "R21") (pin "2") (pinfunction "2_2") (pintype "passive"))
      (node (ref "R22") (pin "1") (pinfunction "1_1") (pintype "passive"))
    )
    (net (code "21") (name "Net-(R22-Pad2)") (class "Default")
      (node (ref "R22") (pin "2") (pinfunction "2_2") (pintype "passive"))
      (node (ref "R23") (pin "1") (pinfunction "1_1") (pintype "passive"))
    )
    (net (code "22") (name "Net-(R23-Pad2)") (class "Default")
      (node (ref "R23") (pin "2") (pinfunction "2_2") (pintype "passive"))
      (node (ref "R24") (pin "1") (pinfunction "1_1") (pintype "passive"))
    )
    (net (code "23") (name "Net-(R24-Pad2)") (class "Default")
      (node (ref "R24") (pin "2") (pinfunction "2_2") (pintype "passive"))
      (node (ref "R25") (pin "1") (pinfunction "1_1") (pintype "passive"))
    )
    (net (code "24") (name "Net-(R25-Pad2)") (class "Default")
      (node (ref "R25") (pin "2") (pinfunction "2_2") (pintype "passive"))
      (node (ref "R26") (pin "1") (pinfunction "1_1") (pintype "passive"))
    )
    (net (code "25") (name "Net-(R26-Pad2)") (class "Default")
      (node (ref "R26") (pin "2") (pinfunction "2_2") (pintype "passive"))
      (node (ref "R27") (pin "1") (pinfunction "1_1") (pintype "passive"))
    )
    (net (code "26") (name "Net-(R27-Pad2)") (class "Default")
      (node (ref "R27") (pin "2") (pinfunction "2_2") (pintype "passive"))
      (node (ref "R28") (pin "1") (pinfunction "1_1") (pintype "passive"))
    )
    (net (code "27") (name "Net-(R28-Pad2)") (class "Default")
      (node (ref "R28") (pin "2") (pinfunction "2_2") (pintype "passive"))
      (node (ref "R29") (pin "1") (pinfunction "1_1") (pintype "passive"))
    )
    (net (code "28") (name "Net-(R29-Pad2)") (class "Default")
      (node (ref "R29") (pin "2") (pinfunction "2_2") (pintype "passive"))
      (node (ref "R30") (pin "1") (pinfunction "1_1") (pintype "passive"))
    )
    (net (code "29") (name "Net-(R30-Pad2)") (class "Default")
      (node (ref "R30") (pin "2") (pinfunction "2_2") (pintype "passive"))
      (node (ref "R31") (pin "1") (pinfunction "1_1") (pintype "passive"))
    )
    (net (code "30") (name "Net-(R31-Pad2)") (class "Default")
      (node (ref "R31") (pin "2") (pinfunction "2_2") (pintype "passive"))
      (node (ref "R32") (pin "1") (pinfunction "1_1") (pintype "passive"))
    )
    (net (code "31") (name "Net-(R32-Pad2)") (class "Default")
      (node (ref "R32") (pin "2") (pinfunction "2_2") (pintype "passive"))
      (node (ref "R33") (pin "1") (pinfunction "1_1") (pintype "passive"))
    )
    (net (code "32") (name "Net-(R33-Pad2)") (class "Default")
      (node (ref "R33") (pin "2") (pinfunction "2_2") (pintype "passive"))
      (node (ref "R34") (pin "1") (pinfunction "1_1") (pintype "passive"))
    )
    (net (code "33") (name "Net-(R34-Pad2)") (class "Default")
      (node (ref "R34") (pin "2") (pinfunction "2_2") (pintype "passive"))
      (node (ref "R35") (pin "1") (pinfunction "1_1") (pintype "passive"))
    )
    (net (code "34") (name "Net-(R35-Pad2)") (class "Default")
      (node (ref "R35") (pin "2") (pinfunction "2_2") (pintype "passive"))
      (node (ref "R36") (pin "1") (pinfunction "1_1") (pintype "passive"))
    )
    (net (code "35") (name "Net-(R37-Pad2)") (class "Default")
      (node (ref "R37") (pin "2") (pinfunction "2_2") (pintype "passive"))
      (node (ref "R38") (pin "1") (pinfunction "1_1") (pintype "passive"))
    )
    (net (code "36") (name "Net-(R38-Pad2)") (class "Default")
      (node (ref "R38") (pin "2") (pinfunction "2_2") (pintype "passive"))
      (node (ref "R39") (pin "1") (pinfunction "1_1") (pintype "passive"))
    )
    (net (code "37") (name "Net-(R39-Pad2)") (class "Default")
      (node (ref "R39") (pin "2") (pinfunction "2_2") (pintype "passive"))
      (node (ref "R40") (pin "1") (pinfunction "1_1") (pintype "passive"))
    )
    (net (code "38") (name "Net-(R40-Pad2)") (class "Default")
      (node (ref "R40") (pin "2") (pinfunction "2_2") (pintype "passive"))
      (node (ref "R41") (pin "1") (pinfunction "1_1") (pintype "passive"))
    )
    (net (code "39") (name "Net-(R41-Pad2)") (class "Default")
      (node (ref "R41") (pin "2") (pinfunction "2_2") (pintype "passive"))
      (node (ref "R42") (pin "1") (pinfunction "1_1") (pintype "passive"))
    )
    (net (code "40") (name "Net-(R42-Pad2)") (class "Default")
      (node (ref "R42") (pin "2") (pinfunction "2_2") (pintype "passive"))
      (node (ref "R43") (pin "1") (pinfunction "1_1") (pintype "passive"))
    )
    (net (code "41") (name "Net-(R43-Pad2)") (class "Default")
      (node (ref "R43") (pin "2") (pinfunction "2_2") (pintype "passive"))
      (node (ref "R44") (pin "1") (pinfunction "1_1") (pintype "passive"))
    )
    (net (code "42") (name "Net-(R44-Pad2)") (class "Default")
      (node (ref "R44") (pin "2") (pinfunction "2_2") (pintype "passive"))
      (node (ref "R45") (pin "1") (pinfunction "1_1") (pintype "passive"))
    )
    (net (code "43") (name "Net-(R45-Pad2)") (class "Default")
      (node (ref "R45") (pin "2") (pinfunction "2_2") (pintype "passive"))
      (node (ref "R46") (pin "1") (pinfunction "1_1") (pintype "passive"))
    )
    (net (code "44") (name "Net-(R46-Pad2)") (class "Default")
      (node (ref "R46") (pin "2") (pinfunction "2_2") (pintype "passive"))
      (node (ref "R47") (pin "1") (pinfunction "1_1") (pintype "passive"))
    )
    (net (code "45") (name "Net-(R47-Pad2)") (class "Default")
      (node (ref "R47") (pin "2") (pinfunction "2_2") (pintype "passive"))
      (node (ref "R48") (pin "1") (pinfunction "1_1") (pintype "passive"))
    )
    (net (code "46") (name "Net-(R48-Pad2)") (class "Default")
      (node (ref "R48") (pin "2") (pinfunction "2_2") (pintype "passive"))
      (node (ref "R49") (pin "1") (pinfunction "1_1") (pintype "passive"))
    )
    (net (code "47") (name "Net-(R49-Pad2)") (class "Default")
      (node (ref "R49") (pin "2") (pinfunction "2_2") (pintype "passive"))
      (node (ref "R50") (pin "1") (pinfunction "1_1") (pintype "passive"))
    )
    (net (code "48") (name "Net-(R50-Pad2)") (class "Default")
      (node (ref "R50") (pin "2") (pinfunction "2_2") (pintype "passive"))
      (node (ref "R51") (pin "1") (pinfunction "1_1") (pintype "passive"))
    )
    (net (code "49") (name "Net-(R51-Pad2)") (class "Default")
      (node (ref "R51") (pin "2") (pinfunction "2_2") (pintype "passive"))
      (node (ref "R52") (pin "1") (pinfunction "1_1") (pintype "passive"))
    )
    (net (code "50") (name "Net-(R52-Pad2)") (class "Default")
      (node (ref "R52") (pin "2") (pinfunction "2_2") (pintype "passive"))
      (node (ref "R53") (pin "1") (pinfunction "1_1") (pintype "passive"))
    )
    (net (code "51") (name "Net-(R53-Pad2)") (class "Default")
      (node (ref "R53") (pin "2") (pinfunction "2_2") (pintype "passive"))
      (node (ref "R54") (pin "1") (pinfunction "1_1") (pintype "passive"))
    )
    (net (code "52") (name "Net-(R54-Pad2)") (class "Default")
      (node (ref "R54") (pin "2") (pinfunction "2_2") (pintype "passive"))
      (node (ref "R55") (pin "1") (pinfunction "1_1") (pintype "passive"))
    )
    (net (code "53") (name "Net-(R56-Pad2)") (class "Default")
      (node (ref "R56") (pin "2") (pinfunction "2_2") (pintype "passive"))
      (node (ref "R57") (pin "1") (pinfunction "1_1") (pintype "passive"))
    )
    (net (code "54") (name "Net-(R57-Pad2)") (class "Default")
      (node (ref "R57") (pin "2") (pinfunction "2_2") (pintype "passive"))
      (node (ref "R58") (pin "1") (pinfunction "1_1") (pintype "passive"))
    )
    (net (code "55") (name "Net-(R58-Pad2)") (class "Default")
      (node (ref "R58") (pin "2") (pinfunction "2_2") (pintype "passive"))
      (node (ref "R59") (pin "1") (pinfunction "1_1") (pintype "passive"))
    )
    (net (code "56") (name "Net-(R59-Pad2)") (class "Default")
      (node (ref "R59") (pin "2") (pinfunction "2_2") (pintype "passive"))
      (node (ref "R60") (pin "1") (pinfunction "1_1") (pintype "passive"))
    )
    (net (code "57") (name "Net-(R60-Pad2)") (class "Default")
      (node (ref "R60") (pin "2") (pinfunction "2_2") (pintype "passive"))
      (node (ref "R61") (pin "1") (pinfunction "1_1") (pintype "passive"))
    )
    (net (code "58") (name "Net-(R61-Pad2)") (class "Default")
      (node (ref "R61") (pin "2") (pinfunction "2_2") (pintype "passive"))
      (node (ref "R62") (pin "1") (pinfunction "1_1") (pintype "passive"))
    )
    (net (code "59") (name "Net-(R62-Pad2)") (class "Default")
      (node (ref "R62") (pin "2") (pinfunction "2_2") (pintype "passive"))
      (node (ref "R63") (pin "1") (pinfunction "1_1") (pintype "passive"))
    )
    (net (code "60") (name "Net-(R63-Pad2)") (class "Default")
      (node (ref "R63") (pin "2") (pinfunction "2_2") (pintype "passive"))
      (node (ref "R64") (pin "1") (pinfunction "1_1") (pintype "passive"))
    )
    (net (code "61") (name "Net-(R64-Pad2)") (class "Default")
      (node (ref "R64") (pin "2") (pinfunction "2_2") (pintype "passive"))
      (node (ref "R65") (pin "1") (pinfunction "1_1") (pintype "passive"))
    )
    (net (code "62") (name "Net-(R65-Pad2)") (class "Default")
      (node (ref "R65") (pin "2") (pinfunction "2_2") (pintype "passive"))
      (node (ref "R66") (pin "1") (pinfunction "1_1") (pintype "passive"))
    )
    (net (code "63") (name "Net-(R66-Pad2)") (class "Default")
      (node (ref "R66") (pin "2") (pinfunction "2_2") (pintype "passive"))
      (node (ref "R67") (pin "1") (pinfunction "1_1") (pintype "passive"))
    )
    (net (code "64") (name "Net-(R67-Pad2)") (class "Default")
      (node (ref "R67") (pin "2") (pinfunction "2_2") (pintype "passive"))
      (node (ref "R68") (pin "1") (pinfunction "1_1") (pintype "passive"))
    )
    (net (code "65") (name "Net-(R68-Pad2)") (class "Default")
      (node (ref "R68") (pin "2") (pinfunction "2_2") (pintype "passive"))
      (node (ref "R69") (pin "1") (pinfunction "1_1") (pintype "passive"))
    )
    (net (code "66") (name "Net-(R69-Pad2)") (class "Default")
      (node (ref "R69") (pin "2") (pinfunction "2_2") (pintype "passive"))
      (node (ref "R70") (pin "1") (pinfunction "1_1") (pintype "passive"))
    )
    (net (code "67") (name "Net-(R70-Pad2)") (class "Default")
      (node (ref "R70") (pin "2") (pinfunction "2_2") (pintype "passive"))
      (node (ref "R71") (pin "1") (pinfunction "1_1") (pintype "passive"))
    )
    (net (code "68") (name "Net-(R71-Pad2)") (class "Default")
      (node (ref "R71") (pin "2") (pinfunction "2_2") (pintype "passive"))
      (node (ref "R72") (pin "1") (pinfunction "1_1") (pintype "passive"))
    )
    (net (code "69") (name "Net-(R72-Pad2)") (class "Default")
      (node (ref "R72") (pin "2") (pinfunction "2_2") (pintype "passive"))
      (node (ref "R73") (pin "1") (pinfunction "1_1") (pintype "passive"))
    )
    (net (code "70") (name "Net-(R73-Pad2)") (class "Default")
      (node (ref "R73") (pin "2") (pinfunction "2_2") (pintype "passive"))
      (node (ref "R74") (pin "1") (pinfunction "1_1") (pintype "passive"))
    )
    (net (code "71") (name "Net-(R75-Pad2)") (class "Default")
      (node (ref "R75") (pin "2") (pinfunction "2_2") (pintype "passive"))
      (node (ref "R76") (pin "1") (pinfunction "1_1") (pintype "passive"))
    )
    (net (code "72") (name "Net-(R76-Pad2)") (class "Default")
      (node (ref "R76") (pin "2") (pinfunction "2_2") (pintype "passive"))
      (node (ref "R77") (pin "1") (pinfunction "1_1") (pintype "passive"))
    )
    (net (code "73") (name "Net-(R77-Pad2)") (class "Default")
      (node (ref "R77") (pin "2") (pinfunction "2_2") (pintype "passive"))
      (node (ref "R78") (pin "1") (pinfunction "1_1") (pintype "passive"))
    )
    (net (code "74") (name "Net-(R78-Pad2)") (class "Default")
      (node (ref "R78") (pin "2") (pinfunction "2_2") (pintype "passive"))
      (node (ref "R79") (pin "1") (pinfunction "1_1") (pintype "passive"))
    )
    (net (code "75") (name "Net-(R79-Pad2)") (class "Default")
      (node (ref "R79") (pin "2") (pinfunction "2_2") (pintype "passive"))
      (node (ref "R80") (pin "1") (pinfunction "1_1") (pintype "passive"))
    )
    (net (code "76") (name "Net-(R80-Pad2)") (class "Default")
      (node (ref "R80") (pin "2") (pinfunction "2_2") (pintype "passive"))
      (node (ref "R81") (pin "1") (pinfunction "1_1") (pintype "passive"))
    )
    (net (code "77") (name "Net-(R81-Pad2)") (class "Default")
      (node (ref "R81") (pin "2") (pinfunction "2_2") (pintype "passive"))
      (node (ref "R82") (pin "1") (pinfunction "1_1") (pintype "passive"))
    )
    (net (code "78") (name "Net-(R82-Pad2)") (class "Default")
      (node (ref "R82") (pin "2") (pinfunction "2_2") (pintype "passive"))
      (node (ref "R83") (pin "1") (pinfunction "1_1") (pintype "passive"))
    )
    (net (code "79") (name "Net-(R83-Pad2)") (class "Default")
      (node (ref "R83") (pin "2") (pinfunction "2_2") (pintype "passive"))
      (node (ref "R84") (pin "1") (pinfunction "1_1") (pintype "passive"))
    )
    (net (code "80") (name "Net-(R84-Pad2)") (class "Default")
      (node (ref "R84") (pin "2") (pinfunction "2_2") (pintype "passive"))
      (node (ref "R85") (pin "1") (pinfunction "1_1") (pintype "passive"))
    )
    (net (code "81") (name "Net-(R85-Pad2)") (class "Default")
      (node (ref "R85") (pin "2") (pinfunction "2_2") (pintype "passive"))
      (node (ref "R86") (pin "1") (pinfunction "1_1") (pintype "passive"))
    )
    (net (code "82") (name "Net-(R86-Pad2)") (class "Default")
      (node (ref "R86") (pin "2") (pinfunction "2_2") (pintype "passive"))
      (node (ref "R87") (pin "1") (pinfunction "1_1") (pintype "passive"))
    )
    (net (code "83") (name "Net-(R87-Pad2)") (class "Default")
      (node (ref "R87") (pin "2") (pinfunction "2_2") (pintype "passive"))
      (node (ref "R88") (pin "1") (pinfunction "1_1") (pintype "passive"))
    )
    (net (code "84") (name "Net-(R88-Pad2)") (class "Default")
      (node (ref "R88") (pin "2") (pinfunction "2_2") (pintype "passive"))
      (node (ref "R89") (pin "1") (pinfunction "1_1") (pintype "passive"))
    )
    (net (code "85") (name "Net-(R89-Pad2)") (class "Default")
      (node (ref "R89") (pin "2") (pinfunction "2_2") (pintype "passive"))
      (node (ref "R90") (pin "1") (pinfunction "1_1") (pintype "passive"))
    )
    (net (code "86") (name "Net-(R90-Pad2)") (class "Default")
      (node (ref "R90") (pin "2") (pinfunction "2_2") (pintype "passive"))
      (node (ref "R91") (pin "1") (pinfunction "1_1") (pintype "passive"))
    )
    (net (code "87") (name "Net-(R91-Pad2)") (class "Default")
      (node (ref "R91") (pin "2") (pinfunction "2_2") (pintype "passive"))
      (node (ref "R92") (pin "1") (pinfunction "1_1") (pintype "passive"))
    )
    (net (code "88") (name "Net-(R92-Pad2)") (class "Default")
      (node (ref "R92") (pin "2") (pinfunction "2_2") (pintype "passive"))
      (node (ref "R93") (pin "1") (pinfunction "1_1") (pintype "passive"))
    )
    (net (code "89") (name "Net-(R94-Pad2)") (class "Default")
      (node (ref "R94") (pin "2") (pinfunction "2_2") (pintype "passive"))
      (node (ref "R95") (pin "1") (pinfunction "1_1") (pintype "passive"))
    )
    (net (code "90") (name "Net-(R95-Pad2)") (class "Default")
      (node (ref "R95") (pin "2") (pinfunction "2_2") (pintype "passive"))
      (node (ref "R96") (pin "1") (pinfunction "1_1") (pintype "passive"))
    )
    (net (code "91") (name "Net-(R96-Pad2)") (class "Default")
      (node (ref "R96") (pin "2") (pinfunction "2_2") (pintype "passive"))
      (node (ref "R97") (pin "1") (pinfunction "1_1") (pintype "passive"))
    )
    (net (code "92") (name "Net-(R97-Pad2)") (class "Default")
      (node (ref "R97") (pin "2") (pinfunction "2_2") (pintype "passive"))
      (node (ref "R98") (pin "1") (pinfunction "1_1") (pintype "passive"))
    )
    (net (code "93") (name "Net-(R98-Pad2)") (class "Default")
      (node (ref "R98") (pin "2") (pinfunction "2_2") (pintype "passive"))
      (node (ref "R99") (pin "1") (pinfunction "1_1") (pintype "passive"))
    )
    (net (code "94") (name "Net-(R100-Pad1)") (class "Default")
      (node (ref "R100") (pin "1") (pinfunction "1_1") (pintype "passive"))
      (node (ref "R99") (pin "2") (pinfunction "2_2") (pintype "passive"))
    )
    (net (code "95") (name "Net-(R100-Pad2)") (class "Default")
      (node (ref "R100") (pin "2") (pinfunction "2_2") (pintype "passive"))
      (node (ref "R101") (pin "1") (pinfunction "1_1") (pintype "passive"))
    )
    (net (code "96") (name "Net-(R101-Pad2)") (class "Default")
      (node (ref "R101") (pin "2") (pinfunction "2_2") (pintype "passive"))
      (node (ref "R102") (pin "1") (pinfunction "1_1") (pintype "passive"))
    )
    (net (code "97") (name "Net-(R102-Pad2)") (class "Default")
      (node (ref "R102") (pin "2") (pinfunction "2_2") (pintype "passive"))
      (node (ref "R103") (pin "1") (pinfunction "1_1") (pintype "passive"))
    )
    (net (code "98") (name "Net-(R103-Pad2)") (class "Default")
      (node (ref "R103") (pin "2") (pinfunction "2_2") (pintype "passive"))
      (node (ref "R104") (pin "1") (pinfunction "1_1") (pintype "passive"))
    )
    (net (code "99") (name "Net-(R104-Pad2)") (class "Default")
      (node (ref "R104") (pin "2") (pinfunction "2_2") (pintype "passive"))
      (node (ref "R105") (pin "1") (pinfunction "1_1") (pintype "passive"))
    )
    (net (code "100") (name "Net-(R105-Pad2)") (class "Default")
      (node (ref "R105") (pin "2") (pinfunction "2_2") (pintype "passive"))
      (node (ref "R106") (pin "1") (pinfunction "1_1") (pintype "passive"))
    )
    (net (code "101") (name "Net-(R106-Pad2)") (class "Default")
      (node (ref "R106") (pin "2") (pinfunction "2_2") (pintype "passive"))
      (node (ref "R107") (pin "1") (pinfunction "1_1") (pintype "passive"))
    )
    (net (code "102") (name "Net-(R107-Pad2)") (class "Default")
      (node (ref "R107") (pin "2") (pinfunction "2_2") (pintype "passive"))
      (node (ref "R108") (pin "1") (pinfunction "1_1") (pintype "passive"))
    )
    (net (code "103") (name "Net-(R108-Pad2)") (class "Default")
      (node (ref "R108") (pin "2") (pinfunction "2_2") (pintype "passive"))
      (node (ref "R109") (pin "1") (pinfunction "1_1") (pintype "passive"))
    )
    (net (code "104") (name "Net-(R109-Pad2)") (class "Default")
      (node (ref "R109") (pin "2") (pinfunction "2_2") (pintype "passive"))
      (node (ref "R110") (pin "1") (pinfunction "1_1") (pintype "passive"))
    )
    (net (code "105") (name "Net-(R110-Pad2)") (class "Default")
      (node (ref "R110") (pin "2") (pinfunction "2_2") (pintype "passive"))
      (node (ref "R111") (pin "1") (pinfunction "1_1") (pintype "passive"))
    )
    (net (code "106") (name "Net-(R111-Pad2)") (class "Default")
      (node (ref "R111") (pin "2") (pinfunction "2_2") (pintype "passive"))
      (node (ref "R112") (pin "1") (pinfunction "1_1") (pintype "passive"))
    )
    (net (code "107") (name "Net-(R113-Pad2)") (class "Default")
      (node (ref "R113") (pin "2") (pinfunction "2_2") (pintype "passive"))
      (node (ref "R114") (pin "1") (pinfunction "1_1") (pintype "passive"))
    )
    (net (code "108") (name "Net-(R114-Pad2)") (class "Default")
      (node (ref "R114") (pin "2") (pinfunction "2_2") (pintype "passive"))
      (node (ref "R115") (pin "1") (pinfunction "1_1") (pintype "passive"))
    )
    (net (code "109") (name "Net-(R115-Pad2)") (class "Default")
      (node (ref "R115") (pin "2") (pinfunction "2_2") (pintype "passive"))
      (node (ref "R116") (pin "1") (pinfunction "1_1") (pintype "passive"))
    )
    (net (code "110") (name "Net-(R116-Pad2)") (class "Default")
      (node (ref "R116") (pin "2") (pinfunction "2_2") (pintype "passive"))
      (node (ref "R117") (pin "1") (pinfunction "1_1") (pintype "passive"))
    )
    (net (code "111") (name "Net-(R117-Pad2)") (class "Default")
      (node (ref "R117") (pin "2") (pinfunction "2_2") (pintype "passive"))
      (node (ref "R118") (pin "1") (pinfunction "1_1") (pintype "passive"))
    )
    (net (code "112") (name "Net-(R118-Pad2)") (class "Default")
      (node (ref "R118") (pin "2") (pinfunction "2_2") (pintype "passive"))
      (node (ref "R119") (pin "1") (pinfunction "1_1") (pintype "passive"))
    )
    (net (code "113") (name "Net-(R119-Pad2)") (class "Default")
      (node (ref "R119") (pin "2") (pinfunction "2_2") (pintype "passive"))
      (node (ref "R120") (pin "1") (pinfunction "1_1") (pintype "passive"))
    )
    (net (code "114") (name "Net-(R120-Pad2)") (class "Default")
      (node (ref "R120") (pin "2") (pinfunction "2_2") (pintype "passive"))
      (node (ref "R121") (pin "1") (pinfunction "1_1") (pintype "passive"))
    )
    (net (code "115") (name "Net-(R121-Pad2)") (class "Default")
      (node (ref "R121") (pin "2") (pinfunction "2_2") (pintype "passive"))
      (node (ref "R122") (pin "1") (pinfunction "1_1") (pintype "passive"))
    )
    (net (code "116") (name "Net-(R122-Pad2)") (class "Default")
      (node (ref "R122") (pin "2") (pinfunction "2_2") (pintype "passive"))
      (node (ref "R123") (pin "1") (pinfunction "1_1") (pintype "passive"))
    )
    (net (code "117") (name "Net-(R123-Pad2)") (class "Default")
      (node (ref "R123") (pin "2") (pinfunction "2_2") (pintype "passive"))
      (node (ref "R124") (pin "1") (pinfunction "1_1") (pintype "passive"))
    )
    (net (code "118") (name "Net-(R124-Pad2)") (class "Default")
      (node (ref "R124") (pin "2") (pinfunction "2_2") (pintype "passive"))
      (node (ref "R125") (pin "1") (pinfunction "1_1") (pintype "passive"))
    )
    (net (code "119") (name "Net-(R125-Pad2)") (class "Default")
      (node (ref "R125") (pin "2") (pinfunction "2_2") (pintype "passive"))
      (node (ref "R126") (pin "1") (pinfunction "1_1") (pintype "passive"))
    )
    (net (code "120") (name "Net-(R126-Pad2)") (class "Default")
      (node (ref "R126") (pin "2") (pinfunction "2_2") (pintype "passive"))
      (node (ref "R127") (pin "1") (pinfunction "1_1") (pintype "passive"))
    )
    (net (code "121") (name "Net-(R127-Pad2)") (class "Default")
      (node (ref "R127") (pin "2") (pinfunction "2_2") (pintype "passive"))
      (node (ref "R128") (pin "1") (pinfunction "1_1") (pintype "passive"))
    )
    (net (code "122") (name "Net-(R128-Pad2)") (class "Default")
      (node (ref "R128") (pin "2") (pinfunction "2_2") (pintype "passive"))
      (node (ref "R129") (pin "1") (pinfunction "1_1") (pintype "passive"))
    )
    (net (code "123") (name "Net-(R129-Pad2)") (class "Default")
      (node (ref "R129") (pin "2") (pinfunction "2_2") (pintype "passive"))
      (node (ref "R130") (pin "1") (pinfunction "1_1") (pintype "passive"))
    )
    (net (code "124") (name "Net-(R130-Pad2)") (class "Default")
      (node (ref "R130") (pin "2") (pinfunction "2_2") (pintype "passive"))
      (node (ref "R131") (pin "1") (pinfunction "1_1") (pintype "passive"))
    )
    (net (code "125") (name "Net-(R132-Pad2)") (class "Default")
      (node (ref "R132") (pin "2") (pinfunction "2_2") (pintype "passive"))
      (node (ref "R133") (pin "1") (pinfunction "1_1") (pintype "passive"))
    )
    (net (code "126") (name "Net-(R133-Pad2)") (class "Default")
      (node (ref "R133") (pin "2") (pinfunction "2_2") (pintype "passive"))
      (node (ref "R134") (pin "1") (pinfunction "1_1") (pintype "passive"))
    )
    (net (code "127") (name "Net-(R134-Pad2)") (class "Default")
      (node (ref "R134") (pin "2") (pinfunction "2_2") (pintype "passive"))
      (node (ref "R135") (pin "1") (pinfunction "1_1") (pintype "passive"))
    )
    (net (code "128") (name "Net-(R135-Pad2)") (class "Default")
      (node (ref "R135") (pin "2") (pinfunction "2_2") (pintype "passive"))
      (node (ref "R136") (pin "1") (pinfunction "1_1") (pintype "passive"))
    )
    (net (code "129") (name "Net-(R136-Pad2)") (class "Default")
      (node (ref "R136") (pin "2") (pinfunction "2_2") (pintype "passive"))
      (node (ref "R137") (pin "1") (pinfunction "1_1") (pintype "passive"))
    )
    (net (code "130") (name "Net-(R137-Pad2)") (class "Default")
      (node (ref "R137") (pin "2") (pinfunction "2_2") (pintype "passive"))
      (node (ref "R138") (pin "1") (pinfunction "1_1") (pintype "passive"))
    )
    (net (code "131") (name "Net-(R138-Pad2)") (class "Default")
      (node (ref "R138") (pin "2") (pinfunction "2_2") (pintype "passive"))
      (node (ref "R139") (pin "1") (pinfunction "1_1") (pintype "passive"))
    )
    (net (code "132") (name "Net-(R139-Pad2)") (class "Default")
      (node (ref "R139") (pin "2") (pinfunction "2_2") (pintype "passive"))
      (node (ref "R140") (pin "1") (pinfunction "1_1") (pintype "passive"))
    )
    (net (code "133") (name "Net-(R140-Pad2)") (class "Default")
      (node (ref "R140") (pin "2") (pinfunction "2_2") (pintype "passive"))
      (node (ref "R141") (pin "1") (pinfunction "1_1") (pintype "passive"))
    )
    (net (code "134") (name "Net-(R141-Pad2)") (class "Default")
      (node (ref "R141") (pin "2") (pinfunction "2_2") (pintype "passive"))
      (node (ref "R142") (pin "1") (pinfunction "1_1") (pintype "passive"))
    )
    (net (code "135") (name "Net-(R142-Pad2)") (class "Default")
      (node (ref "R142") (pin "2") (pinfunction "2_2") (pintype "passive"))
      (node (ref "R143") (pin "1") (pinfunction "1_1") (pintype "passive"))
    )
    (net (code "136") (name "Net-(R143-Pad2)") (class "Default")
      (node (ref "R143") (pin "2") (pinfunction "2_2") (pintype "passive"))
      (node (ref "R144") (pin "1") (pinfunction "1_1") (pintype "passive"))
    )
    (net (code "137") (name "Net-(R144-Pad2)") (class "Default")
      (node (ref "R144") (pin "2") (pinfunction "2_2") (pintype "passive"))
      (node (ref "R145") (pin "1") (pinfunction "1_1") (pintype "passive"))
    )
    (net (code "138") (name "Net-(R145-Pad2)") (class "Default")
      (node (ref "R145") (pin "2") (pinfunction "2_2") (pintype "passive"))
      (node (ref "R146") (pin "1") (pinfunction "1_1") (pintype "passive"))
    )
    (net (code "139") (name "Net-(R146-Pad2)") (class "Default")
      (node (ref "R146") (pin "2") (pinfunction "2_2") (pintype "passive"))
      (node (ref "R147") (pin "1") (pinfunction "1_1") (pintype "passive"))
    )
    (net (code "140") (name "Net-(R147-Pad2)") (class "Default")
      (node (ref "R147") (pin "2") (pinfunction "2_2") (pintype "passive"))
      (node (ref "R148") (pin "1") (pinfunction "1_1") (pintype "passive"))
    )
    (net (code "141") (name "Net-(R148-Pad2)") (class "Default")
      (node (ref "R148") (pin "2") (pinfunction "2_2") (pintype "passive"))
      (node (ref "R149") (pin "1") (pinfunction "1_1") (pintype "passive"))
    )
    (net (code "142") (name "Net-(R149-Pad2)") (class "Default")
      (node (ref "R149") (pin "2") (pinfunction "2_2") (pintype "passive"))
      (node (ref "R150") (pin "1") (pinfunction "1_1") (pintype "passive"))
    )
    (net (code "143") (name "Net-(R151-Pad2)") (class "Default")
      (node (ref "R151") (pin "2") (pinfunction "2_2") (pintype "passive"))
      (node (ref "R152") (pin "1") (pinfunction "1_1") (pintype "passive"))
    )
    (net (code "144") (name "Net-(R152-Pad2)") (class "Default")
      (node (ref "R152") (pin "2") (pinfunction "2_2") (pintype "passive"))
      (node (ref "R153") (pin "1") (pinfunction "1_1") (pintype "passive"))
    )
    (net (code "145") (name "Net-(R153-Pad2)") (class "Default")
      (node (ref "R153") (pin "2") (pinfunction "2_2") (pintype "passive"))
      (node (ref "R154") (pin "1") (pinfunction "1_1") (pintype "passive"))
    )
    (net (code "146") (name "Net-(R154-Pad2)") (class "Default")
      (node (ref "R154") (pin "2") (pinfunction "2_2") (pintype "passive"))
      (node (ref "R155") (pin "1") (pinfunction "1_1") (pintype "passive"))
    )
    (net (code "147") (name "Net-(R155-Pad2)") (class "Default")
      (node (ref "R155") (pin "2") (pinfunction "2_2") (pintype "passive"))
      (node (ref "R156") (pin "1") (pinfunction "1_1") (pintype "passive"))
    )
    (net (code "148") (name "Net-(R156-Pad2)") (class "Default")
      (node (ref "R156") (pin "2") (pinfunction "2_2") (pintype "passive"))
      (node (ref "R157") (pin "1") (pinfunction "1_1") (pintype "passive"))
    )
    (net (code "149") (name "Net-(R157-Pad2)") (class "Default")
      (node (ref "R157") (pin "2") (pinfunction "2_2") (pintype "passive"))
      (node (ref "R158") (pin "1") (pinfunction "1_1") (pintype "passive"))
    )
    (net (code "150") (name "Net-(R158-Pad2)") (class "Default")
      (node (ref "R158") (pin "2") (pinfunction "2_2") (pintype "passive"))
      (node (ref "R159") (pin "1") (pinfunction "1_1") (pintype "passive"))
    )
    (net (code "151") (name "Net-(R159-Pad2)") (class "Default")
      (node (ref "R159") (pin "2") (pinfunction "2_2") (pintype "passive"))
      (node (ref "R160") (pin "1") (pinfunction "1_1") (pintype "passive"))
    )
    (net (code "152") (name "Net-(R160-Pad2)") (class "Default")
      (node (ref "R160") (pin "2") (pinfunction "2_2") (pintype "passive"))
      (node (ref "R161") (pin "1") (pinfunction "1_1") (pintype "passive"))
    )
    (net (code "153") (name "Net-(R161-Pad2)") (class "Default")
      (node (ref "R161") (pin "2") (pinfunction "2_2") (pintype "passive"))
      (node (ref "R162") (pin "1") (pinfunction "1_1") (pintype "passive"))
    )
    (net (code "154") (name "Net-(R162-Pad2)") (class "Default")
      (node (ref "R162") (pin "2") (pinfunction "2_2") (pintype "passive"))
      (node (ref "R163") (pin "1") (pinfunction "1_1") (pintype "passive"))
    )
    (net (code "155") (name "Net-(R163-Pad2)") (class "Default")
      (node (ref "R163") (pin "2") (pinfunction "2_2") (pintype "passive"))
      (node (ref "R164") (pin "1") (pinfunction "1_1") (pintype "passive"))
    )
    (net (code "156") (name "Net-(R164-Pad2)") (class "Default")
      (node (ref "R164") (pin "2") (pinfunction "2_2") (pintype "passive"))
      (node (ref "R165") (pin "1") (pinfunction "1_1") (pintype "passive"))
    )
    (net (code "157") (name "Net-(R165-Pad2)") (class "Default")
      (node (ref "R165") (pin "2") (pinfunction "2_2") (pintype "passive"))
      (node (ref "R166") (pin "1") (pinfunction "1_1") (pintype "passive"))
    )
    (net (code "158") (name "Net-(R166-Pad2)") (class "Default")
      (node (ref "R166") (pin "2") (pinfunction "2_2") (pintype "passive"))
      (node (ref "R167") (pin "1") (pinfunction "1_1") (pintype "passive"))
    )
    (net (code "159") (name "Net-(R167-Pad2)") (class "Default")
      (node (ref "R167") (pin "2") (pinfunction "2_2") (pintype "passive"))
      (node (ref "R168") (pin "1") (pinfunction "1_1") (pintype "passive"))
    )
    (net (code "160") (name "Net-(R168-Pad2)") (class "Default")
      (node (ref "R168") (pin "2") (pinfunction "2_2") (pintype "passive"))
      (node (ref "R169") (pin "1") (pinfunction "1_1") (pintype "passive"))
    )
    (net (code "161") (name "Net-(R170-Pad2)") (class "Default")
      (node (ref "R170") (pin "2") (pinfunction "2_2") (pintype "passive"))
      (node (ref "R171") (pin "1") (pinfunction "1_1") (pintype "passive"))
    )
    (net (code "162") (name "Net-(R171-Pad2)") (class "Default")
      (node (ref "R171") (pin "2") (pinfunction "2_2") (pintype "passive"))
      (node (ref "R172") (pin "1") (pinfunction "1_1") (pintype "passive"))
    )
    (net (code "163") (name "Net-(R172-Pad2)") (class "Default")
      (node (ref "R172") (pin "2") (pinfunction "2_2") (pintype "passive"))
      (node (ref "R173") (pin "1") (pinfunction "1_1") (pintype "passive"))
    )
    (net (code "164") (name "Net-(R173-Pad2)") (class "Default")
      (node (ref "R173") (pin "2") (pinfunction "2_2") (pintype "passive"))
      (node (ref "R174") (pin "1") (pinfunction "1_1") (pintype "passive"))
    )
    (net (code "165") (name "Net-(R174-Pad2)") (class "Default")
      (node (ref "R174") (pin "2") (pinfunction "2_2") (pintype "passive"))
      (node (ref "R175") (pin "1") (pinfunction "1_1") (pintype "passive"))
    )
    (net (code "166") (name "Net-(R175-Pad2)") (class "Default")
      (node (ref "R175") (pin "2") (pinfunction "2_2") (pintype "passive"))
      (node (ref "R176") (pin "1") (pinfunction "1_1") (pintype "passive"))
    )
    (net (code "167") (name "Net-(R176-Pad2)") (class "Default")
      (node (ref "R176") (pin "2") (pinfunction "2_2") (pintype "passive"))
      (node (ref "R177") (pin "1") (pinfunction "1_1") (pintype "passive"))
    )
    (net (code "168") (name "Net-(R177-Pad2)") (class "Default")
      (node (ref "R177") (pin "2") (pinfunction "2_2") (pintype "passive"))
      (node (ref "R178") (pin "1") (pinfunction "1_1") (pintype "passive"))
    )
    (net (code "169") (name "Net-(R178-Pad2)") (class "Default")
      (node (ref "R178") (pin "2") (pinfunction "2_2") (pintype "passive"))
      (node (ref "R180") (pin "1") (pinfunction "1_1") (pintype "passive"))
    )
    (net (code "170") (name "Net-(R179-Pad2)") (class "Default")
      (node (ref "R179") (pin "2") (pinfunction "2_2") (pintype "passive"))
      (node (ref "R358") (pin "1") (pinfunction "1_1") (pintype "passive"))
    )
    (net (code "171") (name "Net-(R180-Pad2)") (class "Default")
      (node (ref "R180") (pin "2") (pinfunction "2_2") (pintype "passive"))
      (node (ref "R181") (pin "1") (pinfunction "1_1") (pintype "passive"))
    )
    (net (code "172") (name "Net-(R181-Pad2)") (class "Default")
      (node (ref "R181") (pin "2") (pinfunction "2_2") (pintype "passive"))
      (node (ref "R182") (pin "1") (pinfunction "1_1") (pintype "passive"))
    )
    (net (code "173") (name "Net-(R182-Pad2)") (class "Default")
      (node (ref "R182") (pin "2") (pinfunction "2_2") (pintype "passive"))
      (node (ref "R183") (pin "1") (pinfunction "1_1") (pintype "passive"))
    )
    (net (code "174") (name "Net-(R183-Pad2)") (class "Default")
      (node (ref "R183") (pin "2") (pinfunction "2_2") (pintype "passive"))
      (node (ref "R184") (pin "1") (pinfunction "1_1") (pintype "passive"))
    )
    (net (code "175") (name "Net-(R184-Pad2)") (class "Default")
      (node (ref "R184") (pin "2") (pinfunction "2_2") (pintype "passive"))
      (node (ref "R185") (pin "1") (pinfunction "1_1") (pintype "passive"))
    )
    (net (code "176") (name "Net-(R185-Pad2)") (class "Default")
      (node (ref "R185") (pin "2") (pinfunction "2_2") (pintype "passive"))
      (node (ref "R186") (pin "1") (pinfunction "1_1") (pintype "passive"))
    )
    (net (code "177") (name "Net-(R186-Pad2)") (class "Default")
      (node (ref "R186") (pin "2") (pinfunction "2_2") (pintype "passive"))
      (node (ref "R187") (pin "1") (pinfunction "1_1") (pintype "passive"))
    )
    (net (code "178") (name "Net-(R187-Pad2)") (class "Default")
      (node (ref "R187") (pin "2") (pinfunction "2_2") (pintype "passive"))
      (node (ref "R188") (pin "1") (pinfunction "1_1") (pintype "passive"))
    )
    (net (code "179") (name "Net-(R189-Pad2)") (class "Default")
      (node (ref "R189") (pin "2") (pinfunction "2_2") (pintype "passive"))
      (node (ref "R190") (pin "1") (pinfunction "1_1") (pintype "passive"))
    )
    (net (code "180") (name "Net-(R190-Pad2)") (class "Default")
      (node (ref "R190") (pin "2") (pinfunction "2_2") (pintype "passive"))
      (node (ref "R191") (pin "1") (pinfunction "1_1") (pintype "passive"))
    )
    (net (code "181") (name "Net-(R191-Pad2)") (class "Default")
      (node (ref "R191") (pin "2") (pinfunction "2_2") (pintype "passive"))
      (node (ref "R192") (pin "1") (pinfunction "1_1") (pintype "passive"))
    )
    (net (code "182") (name "Net-(R192-Pad2)") (class "Default")
      (node (ref "R192") (pin "2") (pinfunction "2_2") (pintype "passive"))
      (node (ref "R193") (pin "1") (pinfunction "1_1") (pintype "passive"))
    )
    (net (code "183") (name "Net-(R193-Pad2)") (class "Default")
      (node (ref "R193") (pin "2") (pinfunction "2_2") (pintype "passive"))
      (node (ref "R194") (pin "1") (pinfunction "1_1") (pintype "passive"))
    )
    (net (code "184") (name "Net-(R194-Pad2)") (class "Default")
      (node (ref "R194") (pin "2") (pinfunction "2_2") (pintype "passive"))
      (node (ref "R195") (pin "1") (pinfunction "1_1") (pintype "passive"))
    )
    (net (code "185") (name "Net-(R195-Pad2)") (class "Default")
      (node (ref "R195") (pin "2") (pinfunction "2_2") (pintype "passive"))
      (node (ref "R196") (pin "1") (pinfunction "1_1") (pintype "passive"))
    )
    (net (code "186") (name "Net-(R196-Pad2)") (class "Default")
      (node (ref "R196") (pin "2") (pinfunction "2_2") (pintype "passive"))
      (node (ref "R197") (pin "1") (pinfunction "1_1") (pintype "passive"))
    )
    (net (code "187") (name "Net-(R197-Pad2)") (class "Default")
      (node (ref "R197") (pin "2") (pinfunction "2_2") (pintype "passive"))
      (node (ref "R198") (pin "1") (pinfunction "1_1") (pintype "passive"))
    )
    (net (code "188") (name "Net-(R198-Pad2)") (class "Default")
      (node (ref "R198") (pin "2") (pinfunction "2_2") (pintype "passive"))
      (node (ref "R199") (pin "1") (pinfunction "1_1") (pintype "passive"))
    )
    (net (code "189") (name "Net-(R199-Pad2)") (class "Default")
      (node (ref "R199") (pin "2") (pinfunction "2_2") (pintype "passive"))
      (node (ref "R200") (pin "1") (pinfunction "1_1") (pintype "passive"))
    )
    (net (code "190") (name "Net-(R200-Pad2)") (class "Default")
      (node (ref "R200") (pin "2") (pinfunction "2_2") (pintype "passive"))
      (node (ref "R201") (pin "1") (pinfunction "1_1") (pintype "passive"))
    )
    (net (code "191") (name "Net-(R201-Pad2)") (class "Default")
      (node (ref "R201") (pin "2") (pinfunction "2_2") (pintype "passive"))
      (node (ref "R202") (pin "1") (pinfunction "1_1") (pintype "passive"))
    )
    (net (code "192") (name "Net-(R202-Pad2)") (class "Default")
      (node (ref "R202") (pin "2") (pinfunction "2_2") (pintype "passive"))
      (node (ref "R203") (pin "1") (pinfunction "1_1") (pintype "passive"))
    )
    (net (code "193") (name "Net-(R203-Pad2)") (class "Default")
      (node (ref "R203") (pin "2") (pinfunction "2_2") (pintype "passive"))
      (node (ref "R204") (pin "1") (pinfunction "1_1") (pintype "passive"))
    )
    (net (code "194") (name "Net-(R204-Pad2)") (class "Default")
      (node (ref "R204") (pin "2") (pinfunction "2_2") (pintype "passive"))
      (node (ref "R205") (pin "1") (pinfunction "1_1") (pintype "passive"))
    )
    (net (code "195") (name "Net-(R205-Pad2)") (class "Default")
      (node (ref "R205") (pin "2") (pinfunction "2_2") (pintype "passive"))
      (node (ref "R206") (pin "1") (pinfunction "1_1") (pintype "passive"))
    )
    (net (code "196") (name "Net-(R206-Pad2)") (class "Default")
      (node (ref "R206") (pin "2") (pinfunction "2_2") (pintype "passive"))
      (node (ref "R207") (pin "1") (pinfunction "1_1") (pintype "passive"))
    )
    (net (code "197") (name "Net-(R208-Pad2)") (class "Default")
      (node (ref "R208") (pin "2") (pinfunction "2_2") (pintype "passive"))
      (node (ref "R209") (pin "1") (pinfunction "1_1") (pintype "passive"))
    )
    (net (code "198") (name "Net-(R209-Pad2)") (class "Default")
      (node (ref "R209") (pin "2") (pinfunction "2_2") (pintype "passive"))
      (node (ref "R210") (pin "1") (pinfunction "1_1") (pintype "passive"))
    )
    (net (code "199") (name "Net-(R210-Pad2)") (class "Default")
      (node (ref "R210") (pin "2") (pinfunction "2_2") (pintype "passive"))
      (node (ref "R211") (pin "1") (pinfunction "1_1") (pintype "passive"))
    )
    (net (code "200") (name "Net-(R211-Pad2)") (class "Default")
      (node (ref "R211") (pin "2") (pinfunction "2_2") (pintype "passive"))
      (node (ref "R212") (pin "1") (pinfunction "1_1") (pintype "passive"))
    )
    (net (code "201") (name "Net-(R212-Pad2)") (class "Default")
      (node (ref "R212") (pin "2") (pinfunction "2_2") (pintype "passive"))
      (node (ref "R213") (pin "1") (pinfunction "1_1") (pintype "passive"))
    )
    (net (code "202") (name "Net-(R213-Pad2)") (class "Default")
      (node (ref "R213") (pin "2") (pinfunction "2_2") (pintype "passive"))
      (node (ref "R214") (pin "1") (pinfunction "1_1") (pintype "passive"))
    )
    (net (code "203") (name "Net-(R214-Pad2)") (class "Default")
      (node (ref "R214") (pin "2") (pinfunction "2_2") (pintype "passive"))
      (node (ref "R215") (pin "1") (pinfunction "1_1") (pintype "passive"))
    )
    (net (code "204") (name "Net-(R215-Pad2)") (class "Default")
      (node (ref "R215") (pin "2") (pinfunction "2_2") (pintype "passive"))
      (node (ref "R216") (pin "1") (pinfunction "1_1") (pintype "passive"))
    )
    (net (code "205") (name "Net-(R216-Pad2)") (class "Default")
      (node (ref "R216") (pin "2") (pinfunction "2_2") (pintype "passive"))
      (node (ref "R217") (pin "1") (pinfunction "1_1") (pintype "passive"))
    )
    (net (code "206") (name "Net-(R217-Pad2)") (class "Default")
      (node (ref "R217") (pin "2") (pinfunction "2_2") (pintype "passive"))
      (node (ref "R218") (pin "1") (pinfunction "1_1") (pintype "passive"))
    )
    (net (code "207") (name "Net-(R218-Pad2)") (class "Default")
      (node (ref "R218") (pin "2") (pinfunction "2_2") (pintype "passive"))
      (node (ref "R219") (pin "1") (pinfunction "1_1") (pintype "passive"))
    )
    (net (code "208") (name "Net-(R219-Pad2)") (class "Default")
      (node (ref "R219") (pin "2") (pinfunction "2_2") (pintype "passive"))
      (node (ref "R220") (pin "1") (pinfunction "1_1") (pintype "passive"))
    )
    (net (code "209") (name "Net-(R220-Pad2)") (class "Default")
      (node (ref "R220") (pin "2") (pinfunction "2_2") (pintype "passive"))
      (node (ref "R221") (pin "1") (pinfunction "1_1") (pintype "passive"))
    )
    (net (code "210") (name "Net-(R221-Pad2)") (class "Default")
      (node (ref "R221") (pin "2") (pinfunction "2_2") (pintype "passive"))
      (node (ref "R222") (pin "1") (pinfunction "1_1") (pintype "passive"))
    )
    (net (code "211") (name "Net-(R222-Pad2)") (class "Default")
      (node (ref "R222") (pin "2") (pinfunction "2_2") (pintype "passive"))
      (node (ref "R223") (pin "1") (pinfunction "1_1") (pintype "passive"))
    )
    (net (code "212") (name "Net-(R223-Pad2)") (class "Default")
      (node (ref "R223") (pin "2") (pinfunction "2_2") (pintype "passive"))
      (node (ref "R224") (pin "1") (pinfunction "1_1") (pintype "passive"))
    )
    (net (code "213") (name "Net-(R224-Pad2)") (class "Default")
      (node (ref "R224") (pin "2") (pinfunction "2_2") (pintype "passive"))
      (node (ref "R225") (pin "1") (pinfunction "1_1") (pintype "passive"))
    )
    (net (code "214") (name "Net-(R225-Pad2)") (class "Default")
      (node (ref "R225") (pin "2") (pinfunction "2_2") (pintype "passive"))
      (node (ref "R226") (pin "1") (pinfunction "1_1") (pintype "passive"))
    )
    (net (code "215") (name "Net-(R227-Pad2)") (class "Default")
      (node (ref "R227") (pin "2") (pinfunction "2_2") (pintype "passive"))
      (node (ref "R228") (pin "1") (pinfunction "1_1") (pintype "passive"))
    )
    (net (code "216") (name "Net-(R228-Pad2)") (class "Default")
      (node (ref "R228") (pin "2") (pinfunction "2_2") (pintype "passive"))
      (node (ref "R229") (pin "1") (pinfunction "1_1") (pintype "passive"))
    )
    (net (code "217") (name "Net-(R229-Pad2)") (class "Default")
      (node (ref "R229") (pin "2") (pinfunction "2_2") (pintype "passive"))
      (node (ref "R230") (pin "1") (pinfunction "1_1") (pintype "passive"))
    )
    (net (code "218") (name "Net-(R230-Pad2)") (class "Default")
      (node (ref "R230") (pin "2") (pinfunction "2_2") (pintype "passive"))
      (node (ref "R231") (pin "1") (pinfunction "1_1") (pintype "passive"))
    )
    (net (code "219") (name "Net-(R231-Pad2)") (class "Default")
      (node (ref "R231") (pin "2") (pinfunction "2_2") (pintype "passive"))
      (node (ref "R232") (pin "1") (pinfunction "1_1") (pintype "passive"))
    )
    (net (code "220") (name "Net-(R232-Pad2)") (class "Default")
      (node (ref "R232") (pin "2") (pinfunction "2_2") (pintype "passive"))
      (node (ref "R233") (pin "1") (pinfunction "1_1") (pintype "passive"))
    )
    (net (code "221") (name "Net-(R233-Pad2)") (class "Default")
      (node (ref "R233") (pin "2") (pinfunction "2_2") (pintype "passive"))
      (node (ref "R234") (pin "1") (pinfunction "1_1") (pintype "passive"))
    )
    (net (code "222") (name "Net-(R234-Pad2)") (class "Default")
      (node (ref "R234") (pin "2") (pinfunction "2_2") (pintype "passive"))
      (node (ref "R235") (pin "1") (pinfunction "1_1") (pintype "passive"))
    )
    (net (code "223") (name "Net-(R235-Pad2)") (class "Default")
      (node (ref "R235") (pin "2") (pinfunction "2_2") (pintype "passive"))
      (node (ref "R236") (pin "1") (pinfunction "1_1") (pintype "passive"))
    )
    (net (code "224") (name "Net-(R236-Pad2)") (class "Default")
      (node (ref "R236") (pin "2") (pinfunction "2_2") (pintype "passive"))
      (node (ref "R237") (pin "1") (pinfunction "1_1") (pintype "passive"))
    )
    (net (code "225") (name "Net-(R237-Pad2)") (class "Default")
      (node (ref "R237") (pin "2") (pinfunction "2_2") (pintype "passive"))
      (node (ref "R238") (pin "1") (pinfunction "1_1") (pintype "passive"))
    )
    (net (code "226") (name "Net-(R238-Pad2)") (class "Default")
      (node (ref "R238") (pin "2") (pinfunction "2_2") (pintype "passive"))
      (node (ref "R239") (pin "1") (pinfunction "1_1") (pintype "passive"))
    )
    (net (code "227") (name "Net-(R239-Pad2)") (class "Default")
      (node (ref "R239") (pin "2") (pinfunction "2_2") (pintype "passive"))
      (node (ref "R240") (pin "1") (pinfunction "1_1") (pintype "passive"))
    )
    (net (code "228") (name "Net-(R240-Pad2)") (class "Default")
      (node (ref "R240") (pin "2") (pinfunction "2_2") (pintype "passive"))
      (node (ref "R241") (pin "1") (pinfunction "1_1") (pintype "passive"))
    )
    (net (code "229") (name "Net-(R241-Pad2)") (class "Default")
      (node (ref "R241") (pin "2") (pinfunction "2_2") (pintype "passive"))
      (node (ref "R242") (pin "1") (pinfunction "1_1") (pintype "passive"))
    )
    (net (code "230") (name "Net-(R242-Pad2)") (class "Default")
      (node (ref "R242") (pin "2") (pinfunction "2_2") (pintype "passive"))
      (node (ref "R243") (pin "1") (pinfunction "1_1") (pintype "passive"))
    )
    (net (code "231") (name "Net-(R243-Pad2)") (class "Default")
      (node (ref "R243") (pin "2") (pinfunction "2_2") (pintype "passive"))
      (node (ref "R244") (pin "1") (pinfunction "1_1") (pintype "passive"))
    )
    (net (code "232") (name "Net-(R244-Pad2)") (class "Default")
      (node (ref "R244") (pin "2") (pinfunction "2_2") (pintype "passive"))
      (node (ref "R245") (pin "1") (pinfunction "1_1") (pintype "passive"))
    )
    (net (code "233") (name "Net-(R246-Pad2)") (class "Default")
      (node (ref "R246") (pin "2") (pinfunction "2_2") (pintype "passive"))
      (node (ref "R247") (pin "1") (pinfunction "1_1") (pintype "passive"))
    )
    (net (code "234") (name "Net-(R247-Pad2)") (class "Default")
      (node (ref "R247") (pin "2") (pinfunction "2_2") (pintype "passive"))
      (node (ref "R248") (pin "1") (pinfunction "1_1") (pintype "passive"))
    )
    (net (code "235") (name "Net-(R248-Pad2)") (class "Default")
      (node (ref "R248") (pin "2") (pinfunction "2_2") (pintype "passive"))
      (node (ref "R249") (pin "1") (pinfunction "1_1") (pintype "passive"))
    )
    (net (code "236") (name "Net-(R249-Pad2)") (class "Default")
      (node (ref "R249") (pin "2") (pinfunction "2_2") (pintype "passive"))
      (node (ref "R250") (pin "1") (pinfunction "1_1") (pintype "passive"))
    )
    (net (code "237") (name "Net-(R250-Pad2)") (class "Default")
      (node (ref "R250") (pin "2") (pinfunction "2_2") (pintype "passive"))
      (node (ref "R251") (pin "1") (pinfunction "1_1") (pintype "passive"))
    )
    (net (code "238") (name "Net-(R251-Pad2)") (class "Default")
      (node (ref "R251") (pin "2") (pinfunction "2_2") (pintype "passive"))
      (node (ref "R252") (pin "1") (pinfunction "1_1") (pintype "passive"))
    )
    (net (code "239") (name "Net-(R252-Pad2)") (class "Default")
      (node (ref "R252") (pin "2") (pinfunction "2_2") (pintype "passive"))
      (node (ref "R253") (pin "1") (pinfunction "1_1") (pintype "passive"))
    )
    (net (code "240") (name "Net-(R253-Pad2)") (class "Default")
      (node (ref "R253") (pin "2") (pinfunction "2_2") (pintype "passive"))
      (node (ref "R254") (pin "1") (pinfunction "1_1") (pintype "passive"))
    )
    (net (code "241") (name "Net-(R254-Pad2)") (class "Default")
      (node (ref "R254") (pin "2") (pinfunction "2_2") (pintype "passive"))
      (node (ref "R255") (pin "1") (pinfunction "1_1") (pintype "passive"))
    )
    (net (code "242") (name "Net-(R255-Pad2)") (class "Default")
      (node (ref "R255") (pin "2") (pinfunction "2_2") (pintype "passive"))
      (node (ref "R256") (pin "1") (pinfunction "1_1") (pintype "passive"))
    )
    (net (code "243") (name "Net-(R256-Pad2)") (class "Default")
      (node (ref "R256") (pin "2") (pinfunction "2_2") (pintype "passive"))
      (node (ref "R257") (pin "1") (pinfunction "1_1") (pintype "passive"))
    )
    (net (code "244") (name "Net-(R257-Pad2)") (class "Default")
      (node (ref "R257") (pin "2") (pinfunction "2_2") (pintype "passive"))
      (node (ref "R258") (pin "1") (pinfunction "1_1") (pintype "passive"))
    )
    (net (code "245") (name "Net-(R258-Pad2)") (class "Default")
      (node (ref "R258") (pin "2") (pinfunction "2_2") (pintype "passive"))
      (node (ref "R259") (pin "1") (pinfunction "1_1") (pintype "passive"))
    )
    (net (code "246") (name "Net-(R259-Pad2)") (class "Default")
      (node (ref "R259") (pin "2") (pinfunction "2_2") (pintype "passive"))
      (node (ref "R260") (pin "1") (pinfunction "1_1") (pintype "passive"))
    )
    (net (code "247") (name "Net-(R260-Pad2)") (class "Default")
      (node (ref "R260") (pin "2") (pinfunction "2_2") (pintype "passive"))
      (node (ref "R261") (pin "1") (pinfunction "1_1") (pintype "passive"))
    )
    (net (code "248") (name "Net-(R261-Pad2)") (class "Default")
      (node (ref "R261") (pin "2") (pinfunction "2_2") (pintype "passive"))
      (node (ref "R262") (pin "1") (pinfunction "1_1") (pintype "passive"))
    )
    (net (code "249") (name "Net-(R262-Pad2)") (class "Default")
      (node (ref "R262") (pin "2") (pinfunction "2_2") (pintype "passive"))
      (node (ref "R263") (pin "1") (pinfunction "1_1") (pintype "passive"))
    )
    (net (code "250") (name "Net-(R263-Pad2)") (class "Default")
      (node (ref "R263") (pin "2") (pinfunction "2_2") (pintype "passive"))
      (node (ref "R264") (pin "1") (pinfunction "1_1") (pintype "passive"))
    )
    (net (code "251") (name "Net-(R265-Pad2)") (class "Default")
      (node (ref "R265") (pin "2") (pinfunction "2_2") (pintype "passive"))
      (node (ref "R266") (pin "1") (pinfunction "1_1") (pintype "passive"))
    )
    (net (code "252") (name "Net-(R266-Pad2)") (class "Default")
      (node (ref "R266") (pin "2") (pinfunction "2_2") (pintype "passive"))
      (node (ref "R267") (pin "1") (pinfunction "1_1") (pintype "passive"))
    )
    (net (code "253") (name "Net-(R267-Pad2)") (class "Default")
      (node (ref "R267") (pin "2") (pinfunction "2_2") (pintype "passive"))
      (node (ref "R268") (pin "1") (pinfunction "1_1") (pintype "passive"))
    )
    (net (code "254") (name "Net-(R268-Pad2)") (class "Default")
      (node (ref "R268") (pin "2") (pinfunction "2_2") (pintype "passive"))
      (node (ref "R269") (pin "1") (pinfunction "1_1") (pintype "passive"))
    )
    (net (code "255") (name "Net-(R269-Pad2)") (class "Default")
      (node (ref "R269") (pin "2") (pinfunction "2_2") (pintype "passive"))
      (node (ref "R270") (pin "1") (pinfunction "1_1") (pintype "passive"))
    )
    (net (code "256") (name "Net-(R270-Pad2)") (class "Default")
      (node (ref "R270") (pin "2") (pinfunction "2_2") (pintype "passive"))
      (node (ref "R271") (pin "1") (pinfunction "1_1") (pintype "passive"))
    )
    (net (code "257") (name "Net-(R271-Pad2)") (class "Default")
      (node (ref "R271") (pin "2") (pinfunction "2_2") (pintype "passive"))
      (node (ref "R272") (pin "1") (pinfunction "1_1") (pintype "passive"))
    )
    (net (code "258") (name "Net-(R272-Pad2)") (class "Default")
      (node (ref "R272") (pin "2") (pinfunction "2_2") (pintype "passive"))
      (node (ref "R273") (pin "1") (pinfunction "1_1") (pintype "passive"))
    )
    (net (code "259") (name "Net-(R273-Pad2)") (class "Default")
      (node (ref "R273") (pin "2") (pinfunction "2_2") (pintype "passive"))
      (node (ref "R274") (pin "1") (pinfunction "1_1") (pintype "passive"))
    )
    (net (code "260") (name "Net-(R274-Pad2)") (class "Default")
      (node (ref "R274") (pin "2") (pinfunction "2_2") (pintype "passive"))
      (node (ref "R275") (pin "1") (pinfunction "1_1") (pintype "passive"))
    )
    (net (code "261") (name "Net-(R275-Pad2)") (class "Default")
      (node (ref "R275") (pin "2") (pinfunction "2_2") (pintype "passive"))
      (node (ref "R276") (pin "1") (pinfunction "1_1") (pintype "passive"))
    )
    (net (code "262") (name "Net-(R276-Pad2)") (class "Default")
      (node (ref "R276") (pin "2") (pinfunction "2_2") (pintype "passive"))
      (node (ref "R277") (pin "1") (pinfunction "1_1") (pintype "passive"))
    )
    (net (code "263") (name "Net-(R277-Pad2)") (class "Default")
      (node (ref "R277") (pin "2") (pinfunction "2_2") (pintype "passive"))
      (node (ref "R278") (pin "1") (pinfunction "1_1") (pintype "passive"))
    )
    (net (code "264") (name "Net-(R278-Pad2)") (class "Default")
      (node (ref "R278") (pin "2") (pinfunction "2_2") (pintype "passive"))
      (node (ref "R279") (pin "1") (pinfunction "1_1") (pintype "passive"))
    )
    (net (code "265") (name "Net-(R279-Pad2)") (class "Default")
      (node (ref "R279") (pin "2") (pinfunction "2_2") (pintype "passive"))
      (node (ref "R280") (pin "1") (pinfunction "1_1") (pintype "passive"))
    )
    (net (code "266") (name "Net-(R280-Pad2)") (class "Default")
      (node (ref "R280") (pin "2") (pinfunction "2_2") (pintype "passive"))
      (node (ref "R281") (pin "1") (pinfunction "1_1") (pintype "passive"))
    )
    (net (code "267") (name "Net-(R281-Pad2)") (class "Default")
      (node (ref "R281") (pin "2") (pinfunction "2_2") (pintype "passive"))
      (node (ref "R282") (pin "1") (pinfunction "1_1") (pintype "passive"))
    )
    (net (code "268") (name "Net-(R282-Pad2)") (class "Default")
      (node (ref "R282") (pin "2") (pinfunction "2_2") (pintype "passive"))
      (node (ref "R283") (pin "1") (pinfunction "1_1") (pintype "passive"))
    )
    (net (code "269") (name "Net-(R284-Pad2)") (class "Default")
      (node (ref "R284") (pin "2") (pinfunction "2_2") (pintype "passive"))
      (node (ref "R285") (pin "1") (pinfunction "1_1") (pintype "passive"))
    )
    (net (code "270") (name "Net-(R285-Pad2)") (class "Default")
      (node (ref "R285") (pin "2") (pinfunction "2_2") (pintype "passive"))
      (node (ref "R286") (pin "1") (pinfunction "1_1") (pintype "passive"))
    )
    (net (code "271") (name "Net-(R286-Pad2)") (class "Default")
      (node (ref "R286") (pin "2") (pinfunction "2_2") (pintype "passive"))
      (node (ref "R287") (pin "1") (pinfunction "1_1") (pintype "passive"))
    )
    (net (code "272") (name "Net-(R287-Pad2)") (class "Default")
      (node (ref "R287") (pin "2") (pinfunction "2_2") (pintype "passive"))
      (node (ref "R288") (pin "1") (pinfunction "1_1") (pintype "passive"))
    )
    (net (code "273") (name "Net-(R288-Pad2)") (class "Default")
      (node (ref "R288") (pin "2") (pinfunction "2_2") (pintype "passive"))
      (node (ref "R289") (pin "1") (pinfunction "1_1") (pintype "passive"))
    )
    (net (code "274") (name "Net-(R289-Pad2)") (class "Default")
      (node (ref "R289") (pin "2") (pinfunction "2_2") (pintype "passive"))
      (node (ref "R290") (pin "1") (pinfunction "1_1") (pintype "passive"))
    )
    (net (code "275") (name "Net-(R290-Pad2)") (class "Default")
      (node (ref "R290") (pin "2") (pinfunction "2_2") (pintype "passive"))
      (node (ref "R291") (pin "1") (pinfunction "1_1") (pintype "passive"))
    )
    (net (code "276") (name "Net-(R291-Pad2)") (class "Default")
      (node (ref "R291") (pin "2") (pinfunction "2_2") (pintype "passive"))
      (node (ref "R292") (pin "1") (pinfunction "1_1") (pintype "passive"))
    )
    (net (code "277") (name "Net-(R292-Pad2)") (class "Default")
      (node (ref "R292") (pin "2") (pinfunction "2_2") (pintype "passive"))
      (node (ref "R293") (pin "1") (pinfunction "1_1") (pintype "passive"))
    )
    (net (code "278") (name "Net-(R293-Pad2)") (class "Default")
      (node (ref "R293") (pin "2") (pinfunction "2_2") (pintype "passive"))
      (node (ref "R294") (pin "1") (pinfunction "1_1") (pintype "passive"))
    )
    (net (code "279") (name "Net-(R294-Pad2)") (class "Default")
      (node (ref "R294") (pin "2") (pinfunction "2_2") (pintype "passive"))
      (node (ref "R295") (pin "1") (pinfunction "1_1") (pintype "passive"))
    )
    (net (code "280") (name "Net-(R295-Pad2)") (class "Default")
      (node (ref "R295") (pin "2") (pinfunction "2_2") (pintype "passive"))
      (node (ref "R296") (pin "1") (pinfunction "1_1") (pintype "passive"))
    )
    (net (code "281") (name "Net-(R296-Pad2)") (class "Default")
      (node (ref "R296") (pin "2") (pinfunction "2_2") (pintype "passive"))
      (node (ref "R297") (pin "1") (pinfunction "1_1") (pintype "passive"))
    )
    (net (code "282") (name "Net-(R297-Pad2)") (class "Default")
      (node (ref "R297") (pin "2") (pinfunction "2_2") (pintype "passive"))
      (node (ref "R298") (pin "1") (pinfunction "1_1") (pintype "passive"))
    )
    (net (code "283") (name "Net-(R298-Pad2)") (class "Default")
      (node (ref "R298") (pin "2") (pinfunction "2_2") (pintype "passive"))
      (node (ref "R299") (pin "1") (pinfunction "1_1") (pintype "passive"))
    )
    (net (code "284") (name "Net-(R299-Pad2)") (class "Default")
      (node (ref "R299") (pin "2") (pinfunction "2_2") (pintype "passive"))
      (node (ref "R300") (pin "1") (pinfunction "1_1") (pintype "passive"))
    )
    (net (code "285") (name "Net-(R300-Pad2)") (class "Default")
      (node (ref "R300") (pin "2") (pinfunction "2_2") (pintype "passive"))
      (node (ref "R301") (pin "1") (pinfunction "1_1") (pintype "passive"))
    )
    (net (code "286") (name "Net-(R301-Pad2)") (class "Default")
      (node (ref "R301") (pin "2") (pinfunction "2_2") (pintype "passive"))
      (node (ref "R302") (pin "1") (pinfunction "1_1") (pintype "passive"))
    )
    (net (code "287") (name "Net-(R303-Pad2)") (class "Default")
      (node (ref "R303") (pin "2") (pinfunction "2_2") (pintype "passive"))
      (node (ref "R304") (pin "1") (pinfunction "1_1") (pintype "passive"))
    )
    (net (code "288") (name "Net-(R304-Pad2)") (class "Default")
      (node (ref "R304") (pin "2") (pinfunction "2_2") (pintype "passive"))
      (node (ref "R305") (pin "1") (pinfunction "1_1") (pintype "passive"))
    )
    (net (code "289") (name "Net-(R305-Pad2)") (class "Default")
      (node (ref "R305") (pin "2") (pinfunction "2_2") (pintype "passive"))
      (node (ref "R306") (pin "1") (pinfunction "1_1") (pintype "passive"))
    )
    (net (code "290") (name "Net-(R306-Pad2)") (class "Default")
      (node (ref "R306") (pin "2") (pinfunction "2_2") (pintype "passive"))
      (node (ref "R307") (pin "1") (pinfunction "1_1") (pintype "passive"))
    )
    (net (code "291") (name "Net-(R307-Pad2)") (class "Default")
      (node (ref "R307") (pin "2") (pinfunction "2_2") (pintype "passive"))
      (node (ref "R308") (pin "1") (pinfunction "1_1") (pintype "passive"))
    )
    (net (code "292") (name "Net-(R308-Pad2)") (class "Default")
      (node (ref "R308") (pin "2") (pinfunction "2_2") (pintype "passive"))
      (node (ref "R309") (pin "1") (pinfunction "1_1") (pintype "passive"))
    )
    (net (code "293") (name "Net-(R309-Pad2)") (class "Default")
      (node (ref "R309") (pin "2") (pinfunction "2_2") (pintype "passive"))
      (node (ref "R310") (pin "1") (pinfunction "1_1") (pintype "passive"))
    )
    (net (code "294") (name "Net-(R310-Pad2)") (class "Default")
      (node (ref "R310") (pin "2") (pinfunction "2_2") (pintype "passive"))
      (node (ref "R311") (pin "1") (pinfunction "1_1") (pintype "passive"))
    )
    (net (code "295") (name "Net-(R311-Pad2)") (class "Default")
      (node (ref "R311") (pin "2") (pinfunction "2_2") (pintype "passive"))
      (node (ref "R312") (pin "1") (pinfunction "1_1") (pintype "passive"))
    )
    (net (code "296") (name "Net-(R312-Pad2)") (class "Default")
      (node (ref "R312") (pin "2") (pinfunction "2_2") (pintype "passive"))
      (node (ref "R313") (pin "1") (pinfunction "1_1") (pintype "passive"))
    )
    (net (code "297") (name "Net-(R313-Pad2)") (class "Default")
      (node (ref "R313") (pin "2") (pinfunction "2_2") (pintype "passive"))
      (node (ref "R314") (pin "1") (pinfunction "1_1") (pintype "passive"))
    )
    (net (code "298") (name "Net-(R314-Pad2)") (class "Default")
      (node (ref "R314") (pin "2") (pinfunction "2_2") (pintype "passive"))
      (node (ref "R315") (pin "1") (pinfunction "1_1") (pintype "passive"))
    )
    (net (code "299") (name "Net-(R315-Pad2)") (class "Default")
      (node (ref "R315") (pin "2") (pinfunction "2_2") (pintype "passive"))
      (node (ref "R316") (pin "1") (pinfunction "1_1") (pintype "passive"))
    )
    (net (code "300") (name "Net-(R316-Pad2)") (class "Default")
      (node (ref "R316") (pin "2") (pinfunction "2_2") (pintype "passive"))
      (node (ref "R317") (pin "1") (pinfunction "1_1") (pintype "passive"))
    )
    (net (code "301") (name "Net-(R317-Pad2)") (class "Default")
      (node (ref "R317") (pin "2") (pinfunction "2_2") (pintype "passive"))
      (node (ref "R318") (pin "1") (pinfunction "1_1") (pintype "passive"))
    )
    (net (code "302") (name "Net-(R318-Pad2)") (class "Default")
      (node (ref "R318") (pin "2") (pinfunction "2_2") (pintype "passive"))
      (node (ref "R319") (pin "1") (pinfunction "1_1") (pintype "passive"))
    )
    (net (code "303") (name "Net-(R319-Pad2)") (class "Default")
      (node (ref "R319") (pin "2") (pinfunction "2_2") (pintype "passive"))
      (node (ref "R320") (pin "1") (pinfunction "1_1") (pintype "passive"))
    )
    (net (code "304") (name "Net-(R320-Pad2)") (class "Default")
      (node (ref "R320") (pin "2") (pinfunction "2_2") (pintype "passive"))
      (node (ref "R321") (pin "1") (pinfunction "1_1") (pintype "passive"))
    )
    (net (code "305") (name "Net-(R322-Pad2)") (class "Default")
      (node (ref "R322") (pin "2") (pinfunction "2_2") (pintype "passive"))
      (node (ref "R323") (pin "1") (pinfunction "1_1") (pintype "passive"))
    )
    (net (code "306") (name "Net-(R323-Pad2)") (class "Default")
      (node (ref "R323") (pin "2") (pinfunction "2_2") (pintype "passive"))
      (node (ref "R324") (pin "1") (pinfunction "1_1") (pintype "passive"))
    )
    (net (code "307") (name "Net-(R324-Pad2)") (class "Default")
      (node (ref "R324") (pin "2") (pinfunction "2_2") (pintype "passive"))
      (node (ref "R325") (pin "1") (pinfunction "1_1") (pintype "passive"))
    )
    (net (code "308") (name "Net-(R325-Pad2)") (class "Default")
      (node (ref "R325") (pin "2") (pinfunction "2_2") (pintype "passive"))
      (node (ref "R326") (pin "1") (pinfunction "1_1") (pintype "passive"))
    )
    (net (code "309") (name "Net-(R326-Pad2)") (class "Default")
      (node (ref "R326") (pin "2") (pinfunction "2_2") (pintype "passive"))
      (node (ref "R327") (pin "1") (pinfunction "1_1") (pintype "passive"))
    )
    (net (code "310") (name "Net-(R327-Pad2)") (class "Default")
      (node (ref "R327") (pin "2") (pinfunction "2_2") (pintype "passive"))
      (node (ref "R328") (pin "1") (pinfunction "1_1") (pintype "passive"))
    )
    (net (code "311") (name "Net-(R328-Pad2)") (class "Default")
      (node (ref "R328") (pin "2") (pinfunction "2_2") (pintype "passive"))
      (node (ref "R329") (pin "1") (pinfunction "1_1") (pintype "passive"))
    )
    (net (code "312") (name "Net-(R329-Pad2)") (class "Default")
      (node (ref "R329") (pin "2") (pinfunction "2_2") (pintype "passive"))
      (node (ref "R330") (pin "1") (pinfunction "1_1") (pintype "passive"))
    )
    (net (code "313") (name "Net-(R330-Pad2)") (class "Default")
      (node (ref "R330") (pin "2") (pinfunction "2_2") (pintype "passive"))
      (node (ref "R331") (pin "1") (pinfunction "1_1") (pintype "passive"))
    )
    (net (code "314") (name "Net-(R331-Pad2)") (class "Default")
      (node (ref "R331") (pin "2") (pinfunction "2_2") (pintype "passive"))
      (node (ref "R332") (pin "1") (pinfunction "1_1") (pintype "passive"))
    )
    (net (code "315") (name "Net-(R332-Pad2)") (class "Default")
      (node (ref "R332") (pin "2") (pinfunction "2_2") (pintype "passive"))
      (node (ref "R333") (pin "1") (pinfunction "1_1") (pintype "passive"))
    )
    (net (code "316") (name "Net-(R333-Pad2)") (class "Default")
      (node (ref "R333") (pin "2") (pinfunction "2_2") (pintype "passive"))
      (node (ref "R334") (pin "1") (pinfunction "1_1") (pintype "passive"))
    )
    (net (code "317") (name "Net-(R334-Pad2)") (class "Default")
      (node (ref "R334") (pin "2") (pinfunction "2_2") (pintype "passive"))
      (node (ref "R335") (pin "1") (pinfunction "1_1") (pintype "passive"))
    )
    (net (code "318") (name "Net-(R335-Pad2)") (class "Default")
      (node (ref "R335") (pin "2") (pinfunction "2_2") (pintype "passive"))
      (node (ref "R336") (pin "1") (pinfunction "1_1") (pintype "passive"))
    )
    (net (code "319") (name "Net-(R336-Pad2)") (class "Default")
      (node (ref "R336") (pin "2") (pinfunction "2_2") (pintype "passive"))
      (node (ref "R337") (pin "1") (pinfunction "1_1") (pintype "passive"))
    )
    (net (code "320") (name "Net-(R337-Pad2)") (class "Default")
      (node (ref "R337") (pin "2") (pinfunction "2_2") (pintype "passive"))
      (node (ref "R338") (pin "1") (pinfunction "1_1") (pintype "passive"))
    )
    (net (code "321") (name "Net-(R338-Pad2)") (class "Default")
      (node (ref "R338") (pin "2") (pinfunction "2_2") (pintype "passive"))
      (node (ref "R339") (pin "1") (pinfunction "1_1") (pintype "passive"))
    )
    (net (code "322") (name "Net-(R339-Pad2)") (class "Default")
      (node (ref "R339") (pin "2") (pinfunction "2_2") (pintype "passive"))
      (node (ref "R340") (pin "1") (pinfunction "1_1") (pintype "passive"))
    )
    (net (code "323") (name "Net-(R341-Pad2)") (class "Default")
      (node (ref "R341") (pin "2") (pinfunction "2_2") (pintype "passive"))
      (node (ref "R342") (pin "1") (pinfunction "1_1") (pintype "passive"))
    )
    (net (code "324") (name "Net-(R342-Pad2)") (class "Default")
      (node (ref "R342") (pin "2") (pinfunction "2_2") (pintype "passive"))
      (node (ref "R343") (pin "1") (pinfunction "1_1") (pintype "passive"))
    )
    (net (code "325") (name "Net-(R343-Pad2)") (class "Default")
      (node (ref "R343") (pin "2") (pinfunction "2_2") (pintype "passive"))
      (node (ref "R344") (pin "1") (pinfunction "1_1") (pintype "passive"))
    )
    (net (code "326") (name "Net-(R344-Pad2)") (class "Default")
      (node (ref "R344") (pin "2") (pinfunction "2_2") (pintype "passive"))
      (node (ref "R345") (pin "1") (pinfunction "1_1") (pintype "passive"))
    )
    (net (code "327") (name "Net-(R345-Pad2)") (class "Default")
      (node (ref "R345") (pin "2") (pinfunction "2_2") (pintype "passive"))
      (node (ref "R346") (pin "1") (pinfunction "1_1") (pintype "passive"))
    )
    (net (code "328") (name "Net-(R346-Pad2)") (class "Default")
      (node (ref "R346") (pin "2") (pinfunction "2_2") (pintype "passive"))
      (node (ref "R347") (pin "1") (pinfunction "1_1") (pintype "passive"))
    )
    (net (code "329") (name "Net-(R347-Pad2)") (class "Default")
      (node (ref "R347") (pin "2") (pinfunction "2_2") (pintype "passive"))
      (node (ref "R348") (pin "1") (pinfunction "1_1") (pintype "passive"))
    )
    (net (code "330") (name "Net-(R348-Pad2)") (class "Default")
      (node (ref "R348") (pin "2") (pinfunction "2_2") (pintype "passive"))
      (node (ref "R349") (pin "1") (pinfunction "1_1") (pintype "passive"))
    )
    (net (code "331") (name "Net-(R349-Pad2)") (class "Default")
      (node (ref "R349") (pin "2") (pinfunction "2_2") (pintype "passive"))
      (node (ref "R350") (pin "1") (pinfunction "1_1") (pintype "passive"))
    )
    (net (code "332") (name "Net-(R350-Pad2)") (class "Default")
      (node (ref "R350") (pin "2") (pinfunction "2_2") (pintype "passive"))
      (node (ref "R351") (pin "1") (pinfunction "1_1") (pintype "passive"))
    )
    (net (code "333") (name "Net-(R351-Pad2)") (class "Default")
      (node (ref "R351") (pin "2") (pinfunction "2_2") (pintype "passive"))
      (node (ref "R352") (pin "1") (pinfunction "1_1") (pintype "passive"))
    )
    (net (code "334") (name "Net-(R352-Pad2)") (class "Default")
      (node (ref "R352") (pin "2") (pinfunction "2_2") (pintype "passive"))
      (node (ref "R353") (pin "1") (pinfunction "1_1") (pintype "passive"))
    )
    (net (code "335") (name "Net-(R353-Pad2)") (class "Default")
      (node (ref "R353") (pin "2") (pinfunction "2_2") (pintype "passive"))
      (node (ref "R354") (pin "1") (pinfunction "1_1") (pintype "passive"))
    )
    (net (code "336") (name "Net-(R354-Pad2)") (class "Default")
      (node (ref "R354") (pin "2") (pinfunction "2_2") (pintype "passive"))
      (node (ref "R355") (pin "1") (pinfunction "1_1") (pintype "passive"))
    )
    (net (code "337") (name "Net-(R355-Pad2)") (class "Default")
      (node (ref "R355") (pin "2") (pinfunction "2_2") (pintype "passive"))
      (node (ref "R356") (pin "1") (pinfunction "1_1") (pintype "passive"))
    )
    (net (code "338") (name "Net-(R356-Pad2)") (class "Default")
      (node (ref "R356") (pin "2") (pinfunction "2_2") (pintype "passive"))
      (node (ref "R357") (pin "1") (pinfunction "1_1") (pintype "passive"))
    )
    (net (code "339") (name "Net-(R358-Pad2)") (class "Default")
      (node (ref "R358") (pin "2") (pinfunction "2_2") (pintype "passive"))
      (node (ref "R359") (pin "1") (pinfunction "1_1") (pintype "passive"))
    )
    (net (code "340") (name "Net-(R359-Pad2)") (class "Default")
      (node (ref "R359") (pin "2") (pinfunction "2_2") (pintype "passive"))
      (node (ref "R360") (pin "1") (pinfunction "1_1") (pintype "passive"))
    )
    (net (code "341") (name "Net-(R360-Pad2)") (class "Default")
      (node (ref "R360") (pin "2") (pinfunction "2_2") (pintype "passive"))
      (node (ref "R361") (pin "1") (pinfunction "1_1") (pintype "passive"))
    )
    (net (code "342") (name "Net-(R361-Pad2)") (class "Default")
      (node (ref "R361") (pin "2") (pinfunction "2_2") (pintype "passive"))
      (node (ref "R362") (pin "1") (pinfunction "1_1") (pintype "passive"))
    )
    (net (code "343") (name "Net-(R362-Pad2)") (class "Default")
      (node (ref "R362") (pin "2") (pinfunction "2_2") (pintype "passive"))
      (node (ref "R363") (pin "1") (pinfunction "1_1") (pintype "passive"))
    )
    (net (code "344") (name "Net-(R363-Pad2)") (class "Default")
      (node (ref "R363") (pin "2") (pinfunction "2_2") (pintype "passive"))
      (node (ref "R364") (pin "1") (pinfunction "1_1") (pintype "passive"))
    )
    (net (code "345") (name "Net-(R364-Pad2)") (class "Default")
      (node (ref "R364") (pin "2") (pinfunction "2_2") (pintype "passive"))
      (node (ref "R365") (pin "1") (pinfunction "1_1") (pintype "passive"))
    )
    (net (code "346") (name "Net-(R365-Pad2)") (class "Default")
      (node (ref "R365") (pin "2") (pinfunction "2_2") (pintype "passive"))
      (node (ref "R366") (pin "1") (pinfunction "1_1") (pintype "passive"))
    )
    (net (code "347") (name "Net-(R366-Pad2)") (class "Default")
      (node (ref "R366") (pin "2") (pinfunction "2_2") (pintype "passive"))
      (node (ref "R367") (pin "1") (pinfunction "1_1") (pintype "passive"))
    )
    (net (code "348") (name "Net-(R367-Pad2)") (class "Default")
      (node (ref "R367") (pin "2") (pinfunction "2_2") (pintype "passive"))
      (node (ref "R368") (pin "1") (pinfunction "1_1") (pintype "passive"))
    )
    (net (code "349") (name "Net-(R368-Pad2)") (class "Default")
      (node (ref "R368") (pin "2") (pinfunction "2_2") (pintype "passive"))
      (node (ref "R369") (pin "1") (pinfunction "1_1") (pintype "passive"))
    )
    (net (code "350") (name "Net-(R369-Pad2)") (class "Default")
      (node (ref "R369") (pin "2") (pinfunction "2_2") (pintype "passive"))
      (node (ref "R370") (pin "1") (pinfunction "1_1") (pintype "passive"))
    )
    (net (code "351") (name "Net-(R370-Pad2)") (class "Default")
      (node (ref "R370") (pin "2") (pinfunction "2_2") (pintype "passive"))
      (node (ref "R371") (pin "1") (pinfunction "1_1") (pintype "passive"))
    )
    (net (code "352") (name "Net-(R371-Pad2)") (class "Default")
      (node (ref "R371") (pin "2") (pinfunction "2_2") (pintype "passive"))
      (node (ref "R372") (pin "1") (pinfunction "1_1") (pintype "passive"))
    )
    (net (code "353") (name "Net-(R372-Pad2)") (class "Default")
      (node (ref "R372") (pin "2") (pinfunction "2_2") (pintype "passive"))
      (node (ref "R373") (pin "1") (pinfunction "1_1") (pintype "passive"))
    )
    (net (code "354") (name "Net-(R374-Pad2)") (class "Default")
      (node (ref "R374") (pin "2") (pinfunction "2_2") (pintype "passive"))
      (node (ref "R375") (pin "1") (pinfunction "1_1") (pintype "passive"))
    )
    (net (code "355") (name "Net-(R375-Pad2)") (class "Default")
      (node (ref "R375") (pin "2") (pinfunction "2_2") (pintype "passive"))
      (node (ref "R376") (pin "1") (pinfunction "1_1") (pintype "passive"))
    )
    (net (code "356") (name "Net-(R376-Pad2)") (class "Default")
      (node (ref "R376") (pin "2") (pinfunction "2_2") (pintype "passive"))
      (node (ref "R377") (pin "1") (pinfunction "1_1") (pintype "passive"))
    )
    (net (code "357") (name "Net-(R377-Pad2)") (class "Default")
      (node (ref "R377") (pin "2") (pinfunction "2_2") (pintype "passive"))
      (node (ref "R378") (pin "1") (pinfunction "1_1") (pintype "passive"))
    )
    (net (code "358") (name "Net-(R378-Pad2)") (class "Default")
      (node (ref "R378") (pin "2") (pinfunction "2_2") (pintype "passive"))
      (node (ref "R379") (pin "1") (pinfunction "1_1") (pintype "passive"))
    )
    (net (code "359") (name "Net-(R379-Pad2)") (class "Default")
      (node (ref "R379") (pin "2") (pinfunction "2_2") (pintype "passive"))
      (node (ref "R380") (pin "1") (pinfunction "1_1") (pintype "passive"))
    )
    (net (code "360") (name "Net-(R380-Pad2)") (class "Default")
      (node (ref "R380") (pin "2") (pinfunction "2_2") (pintype "passive"))
      (node (ref "R381") (pin "1") (pinfunction "1_1") (pintype "passive"))
    )
    (net (code "361") (name "Net-(R381-Pad2)") (class "Default")
      (node (ref "R381") (pin "2") (pinfunction "2_2") (pintype "passive"))
      (node (ref "R382") (pin "1") (pinfunction "1_1") (pintype "passive"))
    )
    (net (code "362") (name "Net-(R382-Pad2)") (class "Default")
      (node (ref "R382") (pin "2") (pinfunction "2_2") (pintype "passive"))
      (node (ref "R383") (pin "1") (pinfunction "1_1") (pintype "passive"))
    )
    (net (code "363") (name "Net-(R383-Pad2)") (class "Default")
      (node (ref "R383") (pin "2") (pinfunction "2_2") (pintype "passive"))
      (node (ref "R384") (pin "1") (pinfunction "1_1") (pintype "passive"))
    )
    (net (code "364") (name "Net-(R384-Pad2)") (class "Default")
      (node (ref "R384") (pin "2") (pinfunction "2_2") (pintype "passive"))
      (node (ref "R385") (pin "1") (pinfunction "1_1") (pintype "passive"))
    )
    (net (code "365") (name "Net-(R385-Pad2)") (class "Default")
      (node (ref "R385") (pin "2") (pinfunction "2_2") (pintype "passive"))
      (node (ref "R386") (pin "1") (pinfunction "1_1") (pintype "passive"))
    )
    (net (code "366") (name "Net-(R386-Pad2)") (class "Default")
      (node (ref "R386") (pin "2") (pinfunction "2_2") (pintype "passive"))
      (node (ref "R387") (pin "1") (pinfunction "1_1") (pintype "passive"))
    )
    (net (code "367") (name "Net-(R387-Pad2)") (class "Default")
      (node (ref "R387") (pin "2") (pinfunction "2_2") (pintype "passive"))
      (node (ref "R388") (pin "1") (pinfunction "1_1") (pintype "passive"))
    )
    (net (code "368") (name "Net-(R388-Pad2)") (class "Default")
      (node (ref "R388") (pin "2") (pinfunction "2_2") (pintype "passive"))
      (node (ref "R389") (pin "1") (pinfunction "1_1") (pintype "passive"))
    )
    (net (code "369") (name "Net-(R389-Pad2)") (class "Default")
      (node (ref "R389") (pin "2") (pinfunction "2_2") (pintype "passive"))
      (node (ref "R390") (pin "1") (pinfunction "1_1") (pintype "passive"))
    )
    (net (code "370") (name "Net-(R390-Pad2)") (class "Default")
      (node (ref "R390") (pin "2") (pinfunction "2_2") (pintype "passive"))
      (node (ref "R391") (pin "1") (pinfunction "1_1") (pintype "passive"))
    )
    (net (code "371") (name "Net-(R391-Pad2)") (class "Default")
      (node (ref "R391") (pin "2") (pinfunction "2_2") (pintype "passive"))
      (node (ref "R392") (pin "1") (pinfunction "1_1") (pintype "passive"))
    )
    (net (code "372") (name "Net-(R393-Pad2)") (class "Default")
      (node (ref "R393") (pin "2") (pinfunction "2_2") (pintype "passive"))
      (node (ref "R394") (pin "1") (pinfunction "1_1") (pintype "passive"))
    )
    (net (code "373") (name "Net-(R394-Pad2)") (class "Default")
      (node (ref "R394") (pin "2") (pinfunction "2_2") (pintype "passive"))
      (node (ref "R395") (pin "1") (pinfunction "1_1") (pintype "passive"))
    )
    (net (code "374") (name "Net-(R395-Pad2)") (class "Default")
      (node (ref "R395") (pin "2") (pinfunction "2_2") (pintype "passive"))
      (node (ref "R396") (pin "1") (pinfunction "1_1") (pintype "passive"))
    )
    (net (code "375") (name "Net-(R396-Pad2)") (class "Default")
      (node (ref "R396") (pin "2") (pinfunction "2_2") (pintype "passive"))
      (node (ref "R397") (pin "1") (pinfunction "1_1") (pintype "passive"))
    )
    (net (code "376") (name "Net-(R397-Pad2)") (class "Default")
      (node (ref "R397") (pin "2") (pinfunction "2_2") (pintype "passive"))
      (node (ref "R398") (pin "1") (pinfunction "1_1") (pintype "passive"))
    )
    (net (code "377") (name "Net-(R398-Pad2)") (class "Default")
      (node (ref "R398") (pin "2") (pinfunction "2_2") (pintype "passive"))
      (node (ref "R399") (pin "1") (pinfunction "1_1") (pintype "passive"))
    )
    (net (code "378") (name "Net-(R399-Pad2)") (class "Default")
      (node (ref "R399") (pin "2") (pinfunction "2_2") (pintype "passive"))
      (node (ref "R400") (pin "1") (pinfunction "1_1") (pintype "passive"))
    )
    (net (code "379") (name "Net-(R400-Pad2)") (class "Default")
      (node (ref "R400") (pin "2") (pinfunction "2_2") (pintype "passive"))
      (node (ref "R401") (pin "1") (pinfunction "1_1") (pintype "passive"))
    )
    (net (code "380") (name "Net-(R401-Pad2)") (class "Default")
      (node (ref "R401") (pin "2") (pinfunction "2_2") (pintype "passive"))
      (node (ref "R402") (pin "1") (pinfunction "1_1") (pintype "passive"))
    )
    (net (code "381") (name "Net-(R402-Pad2)") (class "Default")
      (node (ref "R402") (pin "2") (pinfunction "2_2") (pintype "passive"))
      (node (ref "R403") (pin "1") (pinfunction "1_1") (pintype "passive"))
    )
    (net (code "382") (name "Net-(R403-Pad2)") (class "Default")
      (node (ref "R403") (pin "2") (pinfunction "2_2") (pintype "passive"))
      (node (ref "R404") (pin "1") (pinfunction "1_1") (pintype "passive"))
    )
    (net (code "383") (name "Net-(R404-Pad2)") (class "Default")
      (node (ref "R404") (pin "2") (pinfunction "2_2") (pintype "passive"))
      (node (ref "R405") (pin "1") (pinfunction "1_1") (pintype "passive"))
    )
    (net (code "384") (name "Net-(R405-Pad2)") (class "Default")
      (node (ref "R405") (pin "2") (pinfunction "2_2") (pintype "passive"))
      (node (ref "R406") (pin "1") (pinfunction "1_1") (pintype "passive"))
    )
    (net (code "385") (name "Net-(R406-Pad2)") (class "Default")
      (node (ref "R406") (pin "2") (pinfunction "2_2") (pintype "passive"))
      (node (ref "R407") (pin "1") (pinfunction "1_1") (pintype "passive"))
    )
    (net (code "386") (name "Net-(R407-Pad2)") (class "Default")
      (node (ref "R407") (pin "2") (pinfunction "2_2") (pintype "passive"))
      (node (ref "R408") (pin "1") (pinfunction "1_1") (pintype "passive"))
    )
    (net (code "387") (name "Net-(R408-Pad2)") (class "Default")
      (node (ref "R408") (pin "2") (pinfunction "2_2") (pintype "passive"))
      (node (ref "R409") (pin "1") (pinfunction "1_1") (pintype "passive"))
    )
    (net (code "388") (name "Net-(R409-Pad2)") (class "Default")
      (node (ref "R409") (pin "2") (pinfunction "2_2") (pintype "passive"))
      (node (ref "R410") (pin "1") (pinfunction "1_1") (pintype "passive"))
    )
    (net (code "389") (name "Net-(R410-Pad2)") (class "Default")
      (node (ref "R410") (pin "2") (pinfunction "2_2") (pintype "passive"))
      (node (ref "R411") (pin "1") (pinfunction "1_1") (pintype "passive"))
    )
    (net (code "390") (name "Net-(R412-Pad2)") (class "Default")
      (node (ref "R412") (pin "2") (pinfunction "2_2") (pintype "passive"))
      (node (ref "R413") (pin "1") (pinfunction "1_1") (pintype "passive"))
    )
    (net (code "391") (name "Net-(R413-Pad2)") (class "Default")
      (node (ref "R413") (pin "2") (pinfunction "2_2") (pintype "passive"))
      (node (ref "R414") (pin "1") (pinfunction "1_1") (pintype "passive"))
    )
    (net (code "392") (name "Net-(R414-Pad2)") (class "Default")
      (node (ref "R414") (pin "2") (pinfunction "2_2") (pintype "passive"))
      (node (ref "R415") (pin "1") (pinfunction "1_1") (pintype "passive"))
    )
    (net (code "393") (name "Net-(R415-Pad2)") (class "Default")
      (node (ref "R415") (pin "2") (pinfunction "2_2") (pintype "passive"))
      (node (ref "R416") (pin "1") (pinfunction "1_1") (pintype "passive"))
    )
    (net (code "394") (name "Net-(R416-Pad2)") (class "Default")
      (node (ref "R416") (pin "2") (pinfunction "2_2") (pintype "passive"))
      (node (ref "R417") (pin "1") (pinfunction "1_1") (pintype "passive"))
    )
    (net (code "395") (name "Net-(R417-Pad2)") (class "Default")
      (node (ref "R417") (pin "2") (pinfunction "2_2") (pintype "passive"))
      (node (ref "R418") (pin "1") (pinfunction "1_1") (pintype "passive"))
    )
    (net (code "396") (name "Net-(R418-Pad2)") (class "Default")
      (node (ref "R418") (pin "2") (pinfunction "2_2") (pintype "passive"))
      (node (ref "R419") (pin "1") (pinfunction "1_1") (pintype "passive"))
    )
    (net (code "397") (name "Net-(R419-Pad2)") (class "Default")
      (node (ref "R419") (pin "2") (pinfunction "2_2") (pintype "passive"))
      (node (ref "R420") (pin "1") (pinfunction "1_1") (pintype "passive"))
    )
    (net (code "398") (name "Net-(R420-Pad2)") (class "Default")
      (node (ref "R420") (pin "2") (pinfunction "2_2") (pintype "passive"))
      (node (ref "R421") (pin "1") (pinfunction "1_1") (pintype "passive"))
    )
    (net (code "399") (name "Net-(R421-Pad2)") (class "Default")
      (node (ref "R421") (pin "2") (pinfunction "2_2") (pintype "passive"))
      (node (ref "R422") (pin "1") (pinfunction "1_1") (pintype "passive"))
    )
    (net (code "400") (name "Net-(R422-Pad2)") (class "Default")
      (node (ref "R422") (pin "2") (pinfunction "2_2") (pintype "passive"))
      (node (ref "R423") (pin "1") (pinfunction "1_1") (pintype "passive"))
    )
    (net (code "401") (name "Net-(R423-Pad2)") (class "Default")
      (node (ref "R423") (pin "2") (pinfunction "2_2") (pintype "passive"))
      (node (ref "R424") (pin "1") (pinfunction "1_1") (pintype "passive"))
    )
    (net (code "402") (name "Net-(R424-Pad2)") (class "Default")
      (node (ref "R424") (pin "2") (pinfunction "2_2") (pintype "passive"))
      (node (ref "R425") (pin "1") (pinfunction "1_1") (pintype "passive"))
    )
    (net (code "403") (name "Net-(R425-Pad2)") (class "Default")
      (node (ref "R425") (pin "2") (pinfunction "2_2") (pintype "passive"))
      (node (ref "R426") (pin "1") (pinfunction "1_1") (pintype "passive"))
    )
    (net (code "404") (name "Net-(R426-Pad2)") (class "Default")
      (node (ref "R426") (pin "2") (pinfunction "2_2") (pintype "passive"))
      (node (ref "R427") (pin "1") (pinfunction "1_1") (pintype "passive"))
    )
    (net (code "405") (name "Net-(R427-Pad2)") (class "Default")
      (node (ref "R427") (pin "2") (pinfunction "2_2") (pintype "passive"))
      (node (ref "R428") (pin "1") (pinfunction "1_1") (pintype "passive"))
    )
    (net (code "406") (name "Net-(R428-Pad2)") (class "Default")
      (node (ref "R428") (pin "2") (pinfunction "2_2") (pintype "passive"))
      (node (ref "R429") (pin "1") (pinfunction "1_1") (pintype "passive"))
    )
    (net (code "407") (name "Net-(R429-Pad2)") (class "Default")
      (node (ref "R429") (pin "2") (pinfunction "2_2") (pintype "passive"))
      (node (ref "R430") (pin "1") (pinfunction "1_1") (pintype "passive"))
    )
    (net (code "408") (name "Net-(R431-Pad2)") (class "Default")
      (node (ref "R431") (pin "2") (pinfunction "2_2") (pintype "passive"))
      (node (ref "R432") (pin "1") (pinfunction "1_1") (pintype "passive"))
    )
    (net (code "409") (name "Net-(R432-Pad2)") (class "Default")
      (node (ref "R432") (pin "2") (pinfunction "2_2") (pintype "passive"))
      (node (ref "R433") (pin "1") (pinfunction "1_1") (pintype "passive"))
    )
    (net (code "410") (name "Net-(R433-Pad2)") (class "Default")
      (node (ref "R433") (pin "2") (pinfunction "2_2") (pintype "passive"))
      (node (ref "R434") (pin "1") (pinfunction "1_1") (pintype "passive"))
    )
    (net (code "411") (name "Net-(R434-Pad2)") (class "Default")
      (node (ref "R434") (pin "2") (pinfunction "2_2") (pintype "passive"))
      (node (ref "R435") (pin "1") (pinfunction "1_1") (pintype "passive"))
    )
    (net (code "412") (name "Net-(R435-Pad2)") (class "Default")
      (node (ref "R435") (pin "2") (pinfunction "2_2") (pintype "passive"))
      (node (ref "R436") (pin "1") (pinfunction "1_1") (pintype "passive"))
    )
    (net (code "413") (name "Net-(R436-Pad2)") (class "Default")
      (node (ref "R436") (pin "2") (pinfunction "2_2") (pintype "passive"))
      (node (ref "R437") (pin "1") (pinfunction "1_1") (pintype "passive"))
    )
    (net (code "414") (name "Net-(R437-Pad2)") (class "Default")
      (node (ref "R437") (pin "2") (pinfunction "2_2") (pintype "passive"))
      (node (ref "R438") (pin "1") (pinfunction "1_1") (pintype "passive"))
    )
    (net (code "415") (name "Net-(R438-Pad2)") (class "Default")
      (node (ref "R438") (pin "2") (pinfunction "2_2") (pintype "passive"))
      (node (ref "R439") (pin "1") (pinfunction "1_1") (pintype "passive"))
    )
    (net (code "416") (name "Net-(R439-Pad2)") (class "Default")
      (node (ref "R439") (pin "2") (pinfunction "2_2") (pintype "passive"))
      (node (ref "R440") (pin "1") (pinfunction "1_1") (pintype "passive"))
    )
    (net (code "417") (name "Net-(R440-Pad2)") (class "Default")
      (node (ref "R440") (pin "2") (pinfunction "2_2") (pintype "passive"))
      (node (ref "R441") (pin "1") (pinfunction "1_1") (pintype "passive"))
    )
    (net (code "418") (name "Net-(R441-Pad2)") (class "Default")
      (node (ref "R441") (pin "2") (pinfunction "2_2") (pintype "passive"))
      (node (ref "R442") (pin "1") (pinfunction "1_1") (pintype "passive"))
    )
    (net (code "419") (name "Net-(R442-Pad2)") (class "Default")
      (node (ref "R442") (pin "2") (pinfunction "2_2") (pintype "passive"))
      (node (ref "R443") (pin "1") (pinfunction "1_1") (pintype "passive"))
    )
    (net (code "420") (name "Net-(R443-Pad2)") (class "Default")
      (node (ref "R443") (pin "2") (pinfunction "2_2") (pintype "passive"))
      (node (ref "R444") (pin "1") (pinfunction "1_1") (pintype "passive"))
    )
    (net (code "421") (name "Net-(R444-Pad2)") (class "Default")
      (node (ref "R444") (pin "2") (pinfunction "2_2") (pintype "passive"))
      (node (ref "R445") (pin "1") (pinfunction "1_1") (pintype "passive"))
    )
    (net (code "422") (name "Net-(R445-Pad2)") (class "Default")
      (node (ref "R445") (pin "2") (pinfunction "2_2") (pintype "passive"))
      (node (ref "R446") (pin "1") (pinfunction "1_1") (pintype "passive"))
    )
    (net (code "423") (name "Net-(R446-Pad2)") (class "Default")
      (node (ref "R446") (pin "2") (pinfunction "2_2") (pintype "passive"))
      (node (ref "R447") (pin "1") (pinfunction "1_1") (pintype "passive"))
    )
    (net (code "424") (name "Net-(R447-Pad2)") (class "Default")
      (node (ref "R447") (pin "2") (pinfunction "2_2") (pintype "passive"))
      (node (ref "R448") (pin "1") (pinfunction "1_1") (pintype "passive"))
    )
    (net (code "425") (name "Net-(R448-Pad2)") (class "Default")
      (node (ref "R448") (pin "2") (pinfunction "2_2") (pintype "passive"))
      (node (ref "R449") (pin "1") (pinfunction "1_1") (pintype "passive"))
    )
    (net (code "426") (name "Net-(R450-Pad2)") (class "Default")
      (node (ref "R450") (pin "2") (pinfunction "2_2") (pintype "passive"))
      (node (ref "R451") (pin "1") (pinfunction "1_1") (pintype "passive"))
    )
    (net (code "427") (name "Net-(R451-Pad2)") (class "Default")
      (node (ref "R451") (pin "2") (pinfunction "2_2") (pintype "passive"))
      (node (ref "R452") (pin "1") (pinfunction "1_1") (pintype "passive"))
    )
    (net (code "428") (name "Net-(R452-Pad2)") (class "Default")
      (node (ref "R452") (pin "2") (pinfunction "2_2") (pintype "passive"))
      (node (ref "R453") (pin "1") (pinfunction "1_1") (pintype "passive"))
    )
    (net (code "429") (name "Net-(R453-Pad2)") (class "Default")
      (node (ref "R453") (pin "2") (pinfunction "2_2") (pintype "passive"))
      (node (ref "R454") (pin "1") (pinfunction "1_1") (pintype "passive"))
    )
    (net (code "430") (name "Net-(R454-Pad2)") (class "Default")
      (node (ref "R454") (pin "2") (pinfunction "2_2") (pintype "passive"))
      (node (ref "R455") (pin "1") (pinfunction "1_1") (pintype "passive"))
    )
    (net (code "431") (name "Net-(R455-Pad2)") (class "Default")
      (node (ref "R455") (pin "2") (pinfunction "2_2") (pintype "passive"))
      (node (ref "R456") (pin "1") (pinfunction "1_1") (pintype "passive"))
    )
    (net (code "432") (name "Net-(R456-Pad2)") (class "Default")
      (node (ref "R456") (pin "2") (pinfunction "2_2") (pintype "passive"))
      (node (ref "R457") (pin "1") (pinfunction "1_1") (pintype "passive"))
    )
    (net (code "433") (name "Net-(R457-Pad2)") (class "Default")
      (node (ref "R457") (pin "2") (pinfunction "2_2") (pintype "passive"))
      (node (ref "R458") (pin "1") (pinfunction "1_1") (pintype "passive"))
    )
    (net (code "434") (name "Net-(R458-Pad2)") (class "Default")
      (node (ref "R458") (pin "2") (pinfunction "2_2") (pintype "passive"))
      (node (ref "R459") (pin "1") (pinfunction "1_1") (pintype "passive"))
    )
    (net (code "435") (name "Net-(R459-Pad2)") (class "Default")
      (node (ref "R459") (pin "2") (pinfunction "2_2") (pintype "passive"))
      (node (ref "R460") (pin "1") (pinfunction "1_1") (pintype "passive"))
    )
    (net (code "436") (name "Net-(R460-Pad2)") (class "Default")
      (node (ref "R460") (pin "2") (pinfunction "2_2") (pintype "passive"))
      (node (ref "R461") (pin "1") (pinfunction "1_1") (pintype "passive"))
    )
    (net (code "437") (name "Net-(R461-Pad2)") (class "Default")
      (node (ref "R461") (pin "2") (pinfunction "2_2") (pintype "passive"))
      (node (ref "R462") (pin "1") (pinfunction "1_1") (pintype "passive"))
    )
    (net (code "438") (name "Net-(R462-Pad2)") (class "Default")
      (node (ref "R462") (pin "2") (pinfunction "2_2") (pintype "passive"))
      (node (ref "R463") (pin "1") (pinfunction "1_1") (pintype "passive"))
    )
    (net (code "439") (name "Net-(R463-Pad2)") (class "Default")
      (node (ref "R463") (pin "2") (pinfunction "2_2") (pintype "passive"))
      (node (ref "R464") (pin "1") (pinfunction "1_1") (pintype "passive"))
    )
    (net (code "440") (name "Net-(R464-Pad2)") (class "Default")
      (node (ref "R464") (pin "2") (pinfunction "2_2") (pintype "passive"))
      (node (ref "R465") (pin "1") (pinfunction "1_1") (pintype "passive"))
    )
    (net (code "441") (name "Net-(R465-Pad2)") (class "Default")
      (node (ref "R465") (pin "2") (pinfunction "2_2") (pintype "passive"))
      (node (ref "R466") (pin "1") (pinfunction "1_1") (pintype "passive"))
    )
    (net (code "442") (name "Net-(R466-Pad2)") (class "Default")
      (node (ref "R466") (pin "2") (pinfunction "2_2") (pintype "passive"))
      (node (ref "R467") (pin "1") (pinfunction "1_1") (pintype "passive"))
    )
    (net (code "443") (name "Net-(R467-Pad2)") (class "Default")
      (node (ref "R467") (pin "2") (pinfunction "2_2") (pintype "passive"))
      (node (ref "R468") (pin "1") (pinfunction "1_1") (pintype "passive"))
    )
    (net (code "444") (name "Net-(R469-Pad2)") (class "Default")
      (node (ref "R469") (pin "2") (pinfunction "2_2") (pintype "passive"))
      (node (ref "R470") (pin "1") (pinfunction "1_1") (pintype "passive"))
    )
    (net (code "445") (name "Net-(R470-Pad2)") (class "Default")
      (node (ref "R470") (pin "2") (pinfunction "2_2") (pintype "passive"))
      (node (ref "R471") (pin "1") (pinfunction "1_1") (pintype "passive"))
    )
    (net (code "446") (name "Net-(R471-Pad2)") (class "Default")
      (node (ref "R471") (pin "2") (pinfunction "2_2") (pintype "passive"))
      (node (ref "R472") (pin "1") (pinfunction "1_1") (pintype "passive"))
    )
    (net (code "447") (name "Net-(R472-Pad2)") (class "Default")
      (node (ref "R472") (pin "2") (pinfunction "2_2") (pintype "passive"))
      (node (ref "R473") (pin "1") (pinfunction "1_1") (pintype "passive"))
    )
    (net (code "448") (name "Net-(R473-Pad2)") (class "Default")
      (node (ref "R473") (pin "2") (pinfunction "2_2") (pintype "passive"))
      (node (ref "R474") (pin "1") (pinfunction "1_1") (pintype "passive"))
    )
    (net (code "449") (name "Net-(R474-Pad2)") (class "Default")
      (node (ref "R474") (pin "2") (pinfunction "2_2") (pintype "passive"))
      (node (ref "R475") (pin "1") (pinfunction "1_1") (pintype "passive"))
    )
    (net (code "450") (name "Net-(R475-Pad2)") (class "Default")
      (node (ref "R475") (pin "2") (pinfunction "2_2") (pintype "passive"))
      (node (ref "R476") (pin "1") (pinfunction "1_1") (pintype "passive"))
    )
    (net (code "451") (name "Net-(R476-Pad2)") (class "Default")
      (node (ref "R476") (pin "2") (pinfunction "2_2") (pintype "passive"))
      (node (ref "R477") (pin "1") (pinfunction "1_1") (pintype "passive"))
    )
    (net (code "452") (name "Net-(R477-Pad2)") (class "Default")
      (node (ref "R477") (pin "2") (pinfunction "2_2") (pintype "passive"))
      (node (ref "R478") (pin "1") (pinfunction "1_1") (pintype "passive"))
    )
    (net (code "453") (name "Net-(R478-Pad2)") (class "Default")
      (node (ref "R478") (pin "2") (pinfunction "2_2") (pintype "passive"))
      (node (ref "R479") (pin "1") (pinfunction "1_1") (pintype "passive"))
    )
    (net (code "454") (name "Net-(R479-Pad2)") (class "Default")
      (node (ref "R479") (pin "2") (pinfunction "2_2") (pintype "passive"))
      (node (ref "R480") (pin "1") (pinfunction "1_1") (pintype "passive"))
    )
    (net (code "455") (name "Net-(R480-Pad2)") (class "Default")
      (node (ref "R480") (pin "2") (pinfunction "2_2") (pintype "passive"))
      (node (ref "R481") (pin "1") (pinfunction "1_1") (pintype "passive"))
    )
    (net (code "456") (name "Net-(R481-Pad2)") (class "Default")
      (node (ref "R481") (pin "2") (pinfunction "2_2") (pintype "passive"))
      (node (ref "R482") (pin "1") (pinfunction "1_1") (pintype "passive"))
    )
    (net (code "457") (name "Net-(R482-Pad2)") (class "Default")
      (node (ref "R482") (pin "2") (pinfunction "2_2") (pintype "passive"))
      (node (ref "R483") (pin "1") (pinfunction "1_1") (pintype "passive"))
    )
    (net (code "458") (name "Net-(R483-Pad2)") (class "Default")
      (node (ref "R483") (pin "2") (pinfunction "2_2") (pintype "passive"))
      (node (ref "R484") (pin "1") (pinfunction "1_1") (pintype "passive"))
    )
    (net (code "459") (name "Net-(R484-Pad2)") (class "Default")
      (node (ref "R484") (pin "2") (pinfunction "2_2") (pintype "passive"))
      (node (ref "R485") (pin "1") (pinfunction "1_1") (pintype "passive"))
    )
    (net (code "460") (name "Net-(R485-Pad2)") (class "Default")
      (node (ref "R485") (pin "2") (pinfunction "2_2") (pintype "passive"))
      (node (ref "R486") (pin "1") (pinfunction "1_1") (pintype "passive"))
    )
    (net (code "461") (name "Net-(R486-Pad2)") (class "Default")
      (node (ref "R486") (pin "2") (pinfunction "2_2") (pintype "passive"))
      (node (ref "R487") (pin "1") (pinfunction "1_1") (pintype "passive"))
    )
    (net (code "462") (name "Net-(R488-Pad2)") (class "Default")
      (node (ref "R488") (pin "2") (pinfunction "2_2") (pintype "passive"))
      (node (ref "R489") (pin "1") (pinfunction "1_1") (pintype "passive"))
    )
    (net (code "463") (name "Net-(R489-Pad2)") (class "Default")
      (node (ref "R489") (pin "2") (pinfunction "2_2") (pintype "passive"))
      (node (ref "R490") (pin "1") (pinfunction "1_1") (pintype "passive"))
    )
    (net (code "464") (name "Net-(R490-Pad2)") (class "Default")
      (node (ref "R490") (pin "2") (pinfunction "2_2") (pintype "passive"))
      (node (ref "R491") (pin "1") (pinfunction "1_1") (pintype "passive"))
    )
    (net (code "465") (name "Net-(R491-Pad2)") (class "Default")
      (node (ref "R491") (pin "2") (pinfunction "2_2") (pintype "passive"))
      (node (ref "R492") (pin "1") (pinfunction "1_1") (pintype "passive"))
    )
    (net (code "466") (name "Net-(R492-Pad2)") (class "Default")
      (node (ref "R492") (pin "2") (pinfunction "2_2") (pintype "passive"))
      (node (ref "R493") (pin "1") (pinfunction "1_1") (pintype "passive"))
    )
    (net (code "467") (name "Net-(R493-Pad2)") (class "Default")
      (node (ref "R493") (pin "2") (pinfunction "2_2") (pintype "passive"))
      (node (ref "R494") (pin "1") (pinfunction "1_1") (pintype "passive"))
    )
    (net (code "468") (name "Net-(R494-Pad2)") (class "Default")
      (node (ref "R494") (pin "2") (pinfunction "2_2") (pintype "passive"))
      (node (ref "R495") (pin "1") (pinfunction "1_1") (pintype "passive"))
    )
    (net (code "469") (name "Net-(R495-Pad2)") (class "Default")
      (node (ref "R495") (pin "2") (pinfunction "2_2") (pintype "passive"))
      (node (ref "R496") (pin "1") (pinfunction "1_1") (pintype "passive"))
    )
    (net (code "470") (name "Net-(R496-Pad2)") (class "Default")
      (node (ref "R496") (pin "2") (pinfunction "2_2") (pintype "passive"))
      (node (ref "R497") (pin "1") (pinfunction "1_1") (pintype "passive"))
    )
    (net (code "471") (name "Net-(R497-Pad2)") (class "Default")
      (node (ref "R497") (pin "2") (pinfunction "2_2") (pintype "passive"))
      (node (ref "R498") (pin "1") (pinfunction "1_1") (pintype "passive"))
    )
    (net (code "472") (name "Net-(R498-Pad2)") (class "Default")
      (node (ref "R498") (pin "2") (pinfunction "2_2") (pintype "passive"))
      (node (ref "R499") (pin "1") (pinfunction "1_1") (pintype "passive"))
    )
    (net (code "473") (name "Net-(R499-Pad2)") (class "Default")
      (node (ref "R499") (pin "2") (pinfunction "2_2") (pintype "passive"))
      (node (ref "R500") (pin "1") (pinfunction "1_1") (pintype "passive"))
    )
    (net (code "474") (name "Net-(R500-Pad2)") (class "Default")
      (node (ref "R500") (pin "2") (pinfunction "2_2") (pintype "passive"))
      (node (ref "R501") (pin "1") (pinfunction "1_1") (pintype "passive"))
    )
    (net (code "475") (name "Net-(R501-Pad2)") (class "Default")
      (node (ref "R501") (pin "2") (pinfunction "2_2") (pintype "passive"))
      (node (ref "R502") (pin "1") (pinfunction "1_1") (pintype "passive"))
    )
    (net (code "476") (name "Net-(R502-Pad2)") (class "Default")
      (node (ref "R502") (pin "2") (pinfunction "2_2") (pintype "passive"))
      (node (ref "R503") (pin "1") (pinfunction "1_1") (pintype "passive"))
    )
    (net (code "477") (name "Net-(R503-Pad2)") (class "Default")
      (node (ref "R503") (pin "2") (pinfunction "2_2") (pintype "passive"))
      (node (ref "R504") (pin "1") (pinfunction "1_1") (pintype "passive"))
    )
    (net (code "478") (name "Net-(R504-Pad2)") (class "Default")
      (node (ref "R504") (pin "2") (pinfunction "2_2") (pintype "passive"))
      (node (ref "R505") (pin "1") (pinfunction "1_1") (pintype "passive"))
    )
    (net (code "479") (name "Net-(R505-Pad2)") (class "Default")
      (node (ref "R505") (pin "2") (pinfunction "2_2") (pintype "passive"))
      (node (ref "R506") (pin "1") (pinfunction "1_1") (pintype "passive"))
    )
    (net (code "480") (name "Net-(R507-Pad2)") (class "Default")
      (node (ref "R507") (pin "2") (pinfunction "2_2") (pintype "passive"))
      (node (ref "R508") (pin "1") (pinfunction "1_1") (pintype "passive"))
    )
    (net (code "481") (name "Net-(R508-Pad2)") (class "Default")
      (node (ref "R508") (pin "2") (pinfunction "2_2") (pintype "passive"))
      (node (ref "R509") (pin "1") (pinfunction "1_1") (pintype "passive"))
    )
    (net (code "482") (name "Net-(R509-Pad2)") (class "Default")
      (node (ref "R509") (pin "2") (pinfunction "2_2") (pintype "passive"))
      (node (ref "R510") (pin "1") (pinfunction "1_1") (pintype "passive"))
    )
    (net (code "483") (name "Net-(R510-Pad2)") (class "Default")
      (node (ref "R510") (pin "2") (pinfunction "2_2") (pintype "passive"))
      (node (ref "R511") (pin "1") (pinfunction "1_1") (pintype "passive"))
    )
    (net (code "484") (name "Net-(R511-Pad2)") (class "Default")
      (node (ref "R511") (pin "2") (pinfunction "2_2") (pintype "passive"))
      (node (ref "R512") (pin "1") (pinfunction "1_1") (pintype "passive"))
    )
    (net (code "485") (name "Net-(R512-Pad2)") (class "Default")
      (node (ref "R512") (pin "2") (pinfunction "2_2") (pintype "passive"))
      (node (ref "R513") (pin "1") (pinfunction "1_1") (pintype "passive"))
    )
    (net (code "486") (name "Net-(R513-Pad2)") (class "Default")
      (node (ref "R513") (pin "2") (pinfunction "2_2") (pintype "passive"))
      (node (ref "R514") (pin "1") (pinfunction "1_1") (pintype "passive"))
    )
    (net (code "487") (name "Net-(R514-Pad2)") (class "Default")
      (node (ref "R514") (pin "2") (pinfunction "2_2") (pintype "passive"))
      (node (ref "R515") (pin "1") (pinfunction "1_1") (pintype "passive"))
    )
    (net (code "488") (name "Net-(R515-Pad2)") (class "Default")
      (node (ref "R515") (pin "2") (pinfunction "2_2") (pintype "passive"))
      (node (ref "R516") (pin "1") (pinfunction "1_1") (pintype "passive"))
    )
    (net (code "489") (name "Net-(R516-Pad2)") (class "Default")
      (node (ref "R516") (pin "2") (pinfunction "2_2") (pintype "passive"))
      (node (ref "R517") (pin "1") (pinfunction "1_1") (pintype "passive"))
    )
    (net (code "490") (name "Net-(R517-Pad2)") (class "Default")
      (node (ref "R517") (pin "2") (pinfunction "2_2") (pintype "passive"))
      (node (ref "R518") (pin "1") (pinfunction "1_1") (pintype "passive"))
    )
    (net (code "491") (name "Net-(R518-Pad2)") (class "Default")
      (node (ref "R518") (pin "2") (pinfunction "2_2") (pintype "passive"))
      (node (ref "R519") (pin "1") (pinfunction "1_1") (pintype "passive"))
    )
    (net (code "492") (name "Net-(R519-Pad2)") (class "Default")
      (node (ref "R519") (pin "2") (pinfunction "2_2") (pintype "passive"))
      (node (ref "R520") (pin "1") (pinfunction "1_1") (pintype "passive"))
    )
    (net (code "493") (name "Net-(R520-Pad2)") (class "Default")
      (node (ref "R520") (pin "2") (pinfunction "2_2") (pintype "passive"))
      (node (ref "R521") (pin "1") (pinfunction "1_1") (pintype "passive"))
    )
    (net (code "494") (name "Net-(R521-Pad2)") (class "Default")
      (node (ref "R521") (pin "2") (pinfunction "2_2") (pintype "passive"))
      (node (ref "R522") (pin "1") (pinfunction "1_1") (pintype "passive"))
    )
    (net (code "495") (name "Net-(R522-Pad2)") (class "Default")
      (node (ref "R522") (pin "2") (pinfunction "2_2") (pintype "passive"))
      (node (ref "R523") (pin "1") (pinfunction "1_1") (pintype "passive"))
    )
    (net (code "496") (name "Net-(R523-Pad2)") (class "Default")
      (node (ref "R523") (pin "2") (pinfunction "2_2") (pintype "passive"))
      (node (ref "R524") (pin "1") (pinfunction "1_1") (pintype "passive"))
    )
    (net (code "497") (name "Net-(R524-Pad2)") (class "Default")
      (node (ref "R524") (pin "2") (pinfunction "2_2") (pintype "passive"))
      (node (ref "R525") (pin "1") (pinfunction "1_1") (pintype "passive"))
    )
    (net (code "498") (name "Net-(R526-Pad2)") (class "Default")
      (node (ref "R526") (pin "2") (pinfunction "2_2") (pintype "passive"))
      (node (ref "R527") (pin "1") (pinfunction "1_1") (pintype "passive"))
    )
    (net (code "499") (name "Net-(R527-Pad2)") (class "Default")
      (node (ref "R527") (pin "2") (pinfunction "2_2") (pintype "passive"))
      (node (ref "R528") (pin "1") (pinfunction "1_1") (pintype "passive"))
    )
    (net (code "500") (name "Net-(R528-Pad2)") (class "Default")
      (node (ref "R528") (pin "2") (pinfunction "2_2") (pintype "passive"))
      (node (ref "R529") (pin "1") (pinfunction "1_1") (pintype "passive"))
    )
    (net (code "501") (name "Net-(R529-Pad2)") (class "Default")
      (node (ref "R529") (pin "2") (pinfunction "2_2") (pintype "passive"))
      (node (ref "R530") (pin "1") (pinfunction "1_1") (pintype "passive"))
    )
    (net (code "502") (name "Net-(R530-Pad2)") (class "Default")
      (node (ref "R530") (pin "2") (pinfunction "2_2") (pintype "passive"))
      (node (ref "R531") (pin "1") (pinfunction "1_1") (pintype "passive"))
    )
    (net (code "503") (name "Net-(R531-Pad2)") (class "Default")
      (node (ref "R531") (pin "2") (pinfunction "2_2") (pintype "passive"))
      (node (ref "R532") (pin "1") (pinfunction "1_1") (pintype "passive"))
    )
    (net (code "504") (name "Net-(R532-Pad2)") (class "Default")
      (node (ref "R532") (pin "2") (pinfunction "2_2") (pintype "passive"))
      (node (ref "R533") (pin "1") (pinfunction "1_1") (pintype "passive"))
    )
    (net (code "505") (name "Net-(R533-Pad2)") (class "Default")
      (node (ref "R533") (pin "2") (pinfunction "2_2") (pintype "passive"))
      (node (ref "R534") (pin "1") (pinfunction "1_1") (pintype "passive"))
    )
    (net (code "506") (name "Net-(R534-Pad2)") (class "Default")
      (node (ref "R534") (pin "2") (pinfunction "2_2") (pintype "passive"))
      (node (ref "R535") (pin "1") (pinfunction "1_1") (pintype "passive"))
    )
    (net (code "507") (name "Net-(R535-Pad2)") (class "Default")
      (node (ref "R535") (pin "2") (pinfunction "2_2") (pintype "passive"))
      (node (ref "R536") (pin "1") (pinfunction "1_1") (pintype "passive"))
    )
    (net (code "508") (name "Net-(R536-Pad2)") (class "Default")
      (node (ref "R536") (pin "2") (pinfunction "2_2") (pintype "passive"))
      (node (ref "R537") (pin "1") (pinfunction "1_1") (pintype "passive"))
    )
    (net (code "509") (name "Net-(R537-Pad2)") (class "Default")
      (node (ref "R537") (pin "2") (pinfunction "2_2") (pintype "passive"))
      (node (ref "R538") (pin "1") (pinfunction "1_1") (pintype "passive"))
    )
    (net (code "510") (name "Net-(R538-Pad2)") (class "Default")
      (node (ref "R538") (pin "2") (pinfunction "2_2") (pintype "passive"))
      (node (ref "R539") (pin "1") (pinfunction "1_1") (pintype "passive"))
    )
    (net (code "511") (name "Net-(R539-Pad2)") (class "Default")
      (node (ref "R539") (pin "2") (pinfunction "2_2") (pintype "passive"))
      (node (ref "R540") (pin "1") (pinfunction "1_1") (pintype "passive"))
    )
    (net (code "512") (name "Net-(R540-Pad2)") (class "Default")
      (node (ref "R540") (pin "2") (pinfunction "2_2") (pintype "passive"))
      (node (ref "R541") (pin "1") (pinfunction "1_1") (pintype "passive"))
    )
    (net (code "513") (name "Net-(R541-Pad2)") (class "Default")
      (node (ref "R541") (pin "2") (pinfunction "2_2") (pintype "passive"))
      (node (ref "R542") (pin "1") (pinfunction "1_1") (pintype "passive"))
    )
    (net (code "514") (name "Net-(R542-Pad2)") (class "Default")
      (node (ref "R542") (pin "2") (pinfunction "2_2") (pintype "passive"))
      (node (ref "R543") (pin "1") (pinfunction "1_1") (pintype "passive"))
    )
    (net (code "515") (name "Net-(R544-Pad2)") (class "Default")
      (node (ref "R544") (pin "2") (pinfunction "2_2") (pintype "passive"))
      (node (ref "R545") (pin "1") (pinfunction "1_1") (pintype "passive"))
    )
    (net (code "516") (name "Net-(R545-Pad2)") (class "Default")
      (node (ref "R545") (pin "2") (pinfunction "2_2") (pintype "passive"))
      (node (ref "R546") (pin "1") (pinfunction "1_1") (pintype "passive"))
    )
    (net (code "517") (name "Net-(R546-Pad2)") (class "Default")
      (node (ref "R546") (pin "2") (pinfunction "2_2") (pintype "passive"))
      (node (ref "R547") (pin "1") (pinfunction "1_1") (pintype "passive"))
    )
    (net (code "518") (name "Net-(R547-Pad2)") (class "Default")
      (node (ref "R547") (pin "2") (pinfunction "2_2") (pintype "passive"))
      (node (ref "R548") (pin "1") (pinfunction "1_1") (pintype "passive"))
    )
    (net (code "519") (name "Net-(R548-Pad2)") (class "Default")
      (node (ref "R548") (pin "2") (pinfunction "2_2") (pintype "passive"))
      (node (ref "R549") (pin "1") (pinfunction "1_1") (pintype "passive"))
    )
    (net (code "520") (name "Net-(R549-Pad2)") (class "Default")
      (node (ref "R549") (pin "2") (pinfunction "2_2") (pintype "passive"))
      (node (ref "R550") (pin "1") (pinfunction "1_1") (pintype "passive"))
    )
    (net (code "521") (name "Net-(R550-Pad2)") (class "Default")
      (node (ref "R550") (pin "2") (pinfunction "2_2") (pintype "passive"))
      (node (ref "R551") (pin "1") (pinfunction "1_1") (pintype "passive"))
    )
    (net (code "522") (name "Net-(R551-Pad2)") (class "Default")
      (node (ref "R551") (pin "2") (pinfunction "2_2") (pintype "passive"))
      (node (ref "R552") (pin "1") (pinfunction "1_1") (pintype "passive"))
    )
    (net (code "523") (name "Net-(R552-Pad2)") (class "Default")
      (node (ref "R552") (pin "2") (pinfunction "2_2") (pintype "passive"))
      (node (ref "R553") (pin "1") (pinfunction "1_1") (pintype "passive"))
    )
    (net (code "524") (name "Net-(R553-Pad2)") (class "Default")
      (node (ref "R553") (pin "2") (pinfunction "2_2") (pintype "passive"))
      (node (ref "R554") (pin "1") (pinfunction "1_1") (pintype "passive"))
    )
    (net (code "525") (name "Net-(R554-Pad2)") (class "Default")
      (node (ref "R554") (pin "2") (pinfunction "2_2") (pintype "passive"))
      (node (ref "R555") (pin "1") (pinfunction "1_1") (pintype "passive"))
    )
    (net (code "526") (name "Net-(R555-Pad2)") (class "Default")
      (node (ref "R555") (pin "2") (pinfunction "2_2") (pintype "passive"))
      (node (ref "R556") (pin "1") (pinfunction "1_1") (pintype "passive"))
    )
    (net (code "527") (name "Net-(R556-Pad2)") (class "Default")
      (node (ref "R556") (pin "2") (pinfunction "2_2") (pintype "passive"))
      (node (ref "R557") (pin "1") (pinfunction "1_1") (pintype "passive"))
    )
    (net (code "528") (name "Net-(R557-Pad2)") (class "Default")
      (node (ref "R557") (pin "2") (pinfunction "2_2") (pintype "passive"))
      (node (ref "R558") (pin "1") (pinfunction "1_1") (pintype "passive"))
    )
    (net (code "529") (name "Net-(R558-Pad2)") (class "Default")
      (node (ref "R558") (pin "2") (pinfunction "2_2") (pintype "passive"))
      (node (ref "R559") (pin "1") (pinfunction "1_1") (pintype "passive"))
    )
    (net (code "530") (name "Net-(R559-Pad2)") (class "Default")
      (node (ref "R559") (pin "2") (pinfunction "2_2") (pintype "passive"))
      (node (ref "R560") (pin "1") (pinfunction "1_1") (pintype "passive"))
    )
    (net (code "531") (name "Net-(R560-Pad2)") (class "Default")
      (node (ref "R560") (pin "2") (pinfunction "2_2") (pintype "passive"))
      (node (ref "R561") (pin "1") (pinfunction "1_1") (pintype "passive"))
    )
    (net (code "532") (name "Net-(R561-Pad2)") (class "Default")
      (node (ref "R561") (pin "2") (pinfunction "2_2") (pintype "passive"))
      (node (ref "R562") (pin "1") (pinfunction "1_1") (pintype "passive"))
    )
    (net (code "533") (name "Net-(R563-Pad2)") (class "Default")
      (node (ref "R563") (pin "2") (pinfunction "2_2") (pintype "passive"))
      (node (ref "R564") (pin "1") (pinfunction "1_1") (pintype "passive"))
    )
    (net (code "534") (name "Net-(R564-Pad2)") (class "Default")
      (node (ref "R564") (pin "2") (pinfunction "2_2") (pintype "passive"))
      (node (ref "R565") (pin "1") (pinfunction "1_1") (pintype "passive"))
    )
    (net (code "535") (name "Net-(R565-Pad2)") (class "Default")
      (node (ref "R565") (pin "2") (pinfunction "2_2") (pintype "passive"))
      (node (ref "R566") (pin "1") (pinfunction "1_1") (pintype "passive"))
    )
    (net (code "536") (name "Net-(R566-Pad2)") (class "Default")
      (node (ref "R566") (pin "2") (pinfunction "2_2") (pintype "passive"))
      (node (ref "R567") (pin "1") (pinfunction "1_1") (pintype "passive"))
    )
    (net (code "537") (name "Net-(R567-Pad2)") (class "Default")
      (node (ref "R567") (pin "2") (pinfunction "2_2") (pintype "passive"))
      (node (ref "R568") (pin "1") (pinfunction "1_1") (pintype "passive"))
    )
    (net (code "538") (name "Net-(R568-Pad2)") (class "Default")
      (node (ref "R568") (pin "2") (pinfunction "2_2") (pintype "passive"))
      (node (ref "R569") (pin "1") (pinfunction "1_1") (pintype "passive"))
    )
    (net (code "539") (name "Net-(R569-Pad2)") (class "Default")
      (node (ref "R569") (pin "2") (pinfunction "2_2") (pintype "passive"))
      (node (ref "R570") (pin "1") (pinfunction "1_1") (pintype "passive"))
    )
    (net (code "540") (name "Net-(R570-Pad2)") (class "Default")
      (node (ref "R570") (pin "2") (pinfunction "2_2") (pintype "passive"))
      (node (ref "R571") (pin "1") (pinfunction "1_1") (pintype "passive"))
    )
    (net (code "541") (name "Net-(R571-Pad2)") (class "Default")
      (node (ref "R571") (pin "2") (pinfunction "2_2") (pintype "passive"))
      (node (ref "R572") (pin "1") (pinfunction "1_1") (pintype "passive"))
    )
    (net (code "542") (name "Net-(R572-Pad2)") (class "Default")
      (node (ref "R572") (pin "2") (pinfunction "2_2") (pintype "passive"))
      (node (ref "R573") (pin "1") (pinfunction "1_1") (pintype "passive"))
    )
    (net (code "543") (name "Net-(R573-Pad2)") (class "Default")
      (node (ref "R573") (pin "2") (pinfunction "2_2") (pintype "passive"))
      (node (ref "R574") (pin "1") (pinfunction "1_1") (pintype "passive"))
    )
    (net (code "544") (name "Net-(R574-Pad2)") (class "Default")
      (node (ref "R574") (pin "2") (pinfunction "2_2") (pintype "passive"))
      (node (ref "R575") (pin "1") (pinfunction "1_1") (pintype "passive"))
    )
    (net (code "545") (name "Net-(R575-Pad2)") (class "Default")
      (node (ref "R575") (pin "2") (pinfunction "2_2") (pintype "passive"))
      (node (ref "R576") (pin "1") (pinfunction "1_1") (pintype "passive"))
    )
    (net (code "546") (name "Net-(R576-Pad2)") (class "Default")
      (node (ref "R576") (pin "2") (pinfunction "2_2") (pintype "passive"))
      (node (ref "R577") (pin "1") (pinfunction "1_1") (pintype "passive"))
    )
    (net (code "547") (name "Net-(R577-Pad2)") (class "Default")
      (node (ref "R577") (pin "2") (pinfunction "2_2") (pintype "passive"))
      (node (ref "R578") (pin "1") (pinfunction "1_1") (pintype "passive"))
    )
    (net (code "548") (name "Net-(R578-Pad2)") (class "Default")
      (node (ref "R578") (pin "2") (pinfunction "2_2") (pintype "passive"))
      (node (ref "R579") (pin "1") (pinfunction "1_1") (pintype "passive"))
    )
    (net (code "549") (name "Net-(R579-Pad2)") (class "Default")
      (node (ref "R579") (pin "2") (pinfunction "2_2") (pintype "passive"))
      (node (ref "R580") (pin "1") (pinfunction "1_1") (pintype "passive"))
    )
    (net (code "550") (name "Net-(R580-Pad2)") (class "Default")
      (node (ref "R580") (pin "2") (pinfunction "2_2") (pintype "passive"))
      (node (ref "R581") (pin "1") (pinfunction "1_1") (pintype "passive"))
    )
    (net (code "551") (name "Net-(R582-Pad2)") (class "Default")
      (node (ref "R582") (pin "2") (pinfunction "2_2") (pintype "passive"))
      (node (ref "R583") (pin "1") (pinfunction "1_1") (pintype "passive"))
    )
    (net (code "552") (name "Net-(R583-Pad2)") (class "Default")
      (node (ref "R583") (pin "2") (pinfunction "2_2") (pintype "passive"))
      (node (ref "R584") (pin "1") (pinfunction "1_1") (pintype "passive"))
    )
    (net (code "553") (name "Net-(R584-Pad2)") (class "Default")
      (node (ref "R584") (pin "2") (pinfunction "2_2") (pintype "passive"))
      (node (ref "R585") (pin "1") (pinfunction "1_1") (pintype "passive"))
    )
    (net (code "554") (name "Net-(R585-Pad2)") (class "Default")
      (node (ref "R585") (pin "2") (pinfunction "2_2") (pintype "passive"))
      (node (ref "R586") (pin "1") (pinfunction "1_1") (pintype "passive"))
    )
    (net (code "555") (name "Net-(R586-Pad2)") (class "Default")
      (node (ref "R586") (pin "2") (pinfunction "2_2") (pintype "passive"))
      (node (ref "R587") (pin "1") (pinfunction "1_1") (pintype "passive"))
    )
    (net (code "556") (name "Net-(R587-Pad2)") (class "Default")
      (node (ref "R587") (pin "2") (pinfunction "2_2") (pintype "passive"))
      (node (ref "R588") (pin "1") (pinfunction "1_1") (pintype "passive"))
    )
    (net (code "557") (name "Net-(R588-Pad2)") (class "Default")
      (node (ref "R588") (pin "2") (pinfunction "2_2") (pintype "passive"))
      (node (ref "R589") (pin "1") (pinfunction "1_1") (pintype "passive"))
    )
    (net (code "558") (name "Net-(R589-Pad2)") (class "Default")
      (node (ref "R589") (pin "2") (pinfunction "2_2") (pintype "passive"))
      (node (ref "R590") (pin "1") (pinfunction "1_1") (pintype "passive"))
    )
    (net (code "559") (name "Net-(R590-Pad2)") (class "Default")
      (node (ref "R590") (pin "2") (pinfunction "2_2") (pintype "passive"))
      (node (ref "R591") (pin "1") (pinfunction "1_1") (pintype "passive"))
    )
    (net (code "560") (name "Net-(R591-Pad2)") (class "Default")
      (node (ref "R591") (pin "2") (pinfunction "2_2") (pintype "passive"))
      (node (ref "R592") (pin "1") (pinfunction "1_1") (pintype "passive"))
    )
    (net (code "561") (name "Net-(R592-Pad2)") (class "Default")
      (node (ref "R592") (pin "2") (pinfunction "2_2") (pintype "passive"))
      (node (ref "R593") (pin "1") (pinfunction "1_1") (pintype "passive"))
    )
    (net (code "562") (name "Net-(R593-Pad2)") (class "Default")
      (node (ref "R593") (pin "2") (pinfunction "2_2") (pintype "passive"))
      (node (ref "R594") (pin "1") (pinfunction "1_1") (pintype "passive"))
    )
    (net (code "563") (name "Net-(R594-Pad2)") (class "Default")
      (node (ref "R594") (pin "2") (pinfunction "2_2") (pintype "passive"))
      (node (ref "R595") (pin "1") (pinfunction "1_1") (pintype "passive"))
    )
    (net (code "564") (name "Net-(R595-Pad2)") (class "Default")
      (node (ref "R595") (pin "2") (pinfunction "2_2") (pintype "passive"))
      (node (ref "R596") (pin "1") (pinfunction "1_1") (pintype "passive"))
    )
    (net (code "565") (name "Net-(R596-Pad2)") (class "Default")
      (node (ref "R596") (pin "2") (pinfunction "2_2") (pintype "passive"))
      (node (ref "R597") (pin "1") (pinfunction "1_1") (pintype "passive"))
    )
    (net (code "566") (name "Net-(R597-Pad2)") (class "Default")
      (node (ref "R597") (pin "2") (pinfunction "2_2") (pintype "passive"))
      (node (ref "R598") (pin "1") (pinfunction "1_1") (pintype "passive"))
    )
    (net (code "567") (name "Net-(R598-Pad2)") (class "Default")
      (node (ref "R598") (pin "2") (pinfunction "2_2") (pintype "passive"))
      (node (ref "R599") (pin "1") (pinfunction "1_1") (pintype "passive"))
    )
    (net (code "568") (name "Net-(R599-Pad2)") (class "Default")
      (node (ref "R599") (pin "2") (pinfunction "2_2") (pintype "passive"))
      (node (ref "R600") (pin "1") (pinfunction "1_1") (pintype "passive"))
    )
    (net (code "569") (name "Net-(R601-Pad2)") (class "Default")
      (node (ref "R601") (pin "2") (pinfunction "2_2") (pintype "passive"))
      (node (ref "R602") (pin "1") (pinfunction "1_1") (pintype "passive"))
    )
    (net (code "570") (name "Net-(R602-Pad2)") (class "Default")
      (node (ref "R602") (pin "2") (pinfunction "2_2") (pintype "passive"))
      (node (ref "R603") (pin "1") (pinfunction "1_1") (pintype "passive"))
    )
    (net (code "571") (name "Net-(R603-Pad2)") (class "Default")
      (node (ref "R603") (pin "2") (pinfunction "2_2") (pintype "passive"))
      (node (ref "R604") (pin "1") (pinfunction "1_1") (pintype "passive"))
    )
    (net (code "572") (name "Net-(R604-Pad2)") (class "Default")
      (node (ref "R604") (pin "2") (pinfunction "2_2") (pintype "passive"))
      (node (ref "R605") (pin "1") (pinfunction "1_1") (pintype "passive"))
    )
    (net (code "573") (name "Net-(R605-Pad2)") (class "Default")
      (node (ref "R605") (pin "2") (pinfunction "2_2") (pintype "passive"))
      (node (ref "R606") (pin "1") (pinfunction "1_1") (pintype "passive"))
    )
    (net (code "574") (name "Net-(R606-Pad2)") (class "Default")
      (node (ref "R606") (pin "2") (pinfunction "2_2") (pintype "passive"))
      (node (ref "R607") (pin "1") (pinfunction "1_1") (pintype "passive"))
    )
    (net (code "575") (name "Net-(R607-Pad2)") (class "Default")
      (node (ref "R607") (pin "2") (pinfunction "2_2") (pintype "passive"))
      (node (ref "R608") (pin "1") (pinfunction "1_1") (pintype "passive"))
    )
    (net (code "576") (name "Net-(R608-Pad2)") (class "Default")
      (node (ref "R608") (pin "2") (pinfunction "2_2") (pintype "passive"))
      (node (ref "R609") (pin "1") (pinfunction "1_1") (pintype "passive"))
    )
    (net (code "577") (name "Net-(R609-Pad2)") (class "Default")
      (node (ref "R609") (pin "2") (pinfunction "2_2") (pintype "passive"))
      (node (ref "R610") (pin "1") (pinfunction "1_1") (pintype "passive"))
    )
    (net (code "578") (name "Net-(R610-Pad2)") (class "Default")
      (node (ref "R610") (pin "2") (pinfunction "2_2") (pintype "passive"))
      (node (ref "R611") (pin "1") (pinfunction "1_1") (pintype "passive"))
    )
    (net (code "579") (name "Net-(R611-Pad2)") (class "Default")
      (node (ref "R611") (pin "2") (pinfunction "2_2") (pintype "passive"))
      (node (ref "R612") (pin "1") (pinfunction "1_1") (pintype "passive"))
    )
    (net (code "580") (name "Net-(R612-Pad2)") (class "Default")
      (node (ref "R612") (pin "2") (pinfunction "2_2") (pintype "passive"))
      (node (ref "R613") (pin "1") (pinfunction "1_1") (pintype "passive"))
    )
    (net (code "581") (name "Net-(R613-Pad2)") (class "Default")
      (node (ref "R613") (pin "2") (pinfunction "2_2") (pintype "passive"))
      (node (ref "R614") (pin "1") (pinfunction "1_1") (pintype "passive"))
    )
    (net (code "582") (name "Net-(R614-Pad2)") (class "Default")
      (node (ref "R614") (pin "2") (pinfunction "2_2") (pintype "passive"))
      (node (ref "R615") (pin "1") (pinfunction "1_1") (pintype "passive"))
    )
    (net (code "583") (name "Net-(R615-Pad2)") (class "Default")
      (node (ref "R615") (pin "2") (pinfunction "2_2") (pintype "passive"))
      (node (ref "R616") (pin "1") (pinfunction "1_1") (pintype "passive"))
    )
    (net (code "584") (name "Net-(R616-Pad2)") (class "Default")
      (node (ref "R616") (pin "2") (pinfunction "2_2") (pintype "passive"))
      (node (ref "R617") (pin "1") (pinfunction "1_1") (pintype "passive"))
    )
    (net (code "585") (name "Net-(R617-Pad2)") (class "Default")
      (node (ref "R617") (pin "2") (pinfunction "2_2") (pintype "passive"))
      (node (ref "R618") (pin "1") (pinfunction "1_1") (pintype "passive"))
    )
    (net (code "586") (name "Net-(R618-Pad2)") (class "Default")
      (node (ref "R618") (pin "2") (pinfunction "2_2") (pintype "passive"))
      (node (ref "R619") (pin "1") (pinfunction "1_1") (pintype "passive"))
    )
    (net (code "587") (name "Net-(R620-Pad2)") (class "Default")
      (node (ref "R620") (pin "2") (pinfunction "2_2") (pintype "passive"))
      (node (ref "R621") (pin "1") (pinfunction "1_1") (pintype "passive"))
    )
    (net (code "588") (name "Net-(R621-Pad2)") (class "Default")
      (node (ref "R621") (pin "2") (pinfunction "2_2") (pintype "passive"))
      (node (ref "R622") (pin "1") (pinfunction "1_1") (pintype "passive"))
    )
    (net (code "589") (name "Net-(R622-Pad2)") (class "Default")
      (node (ref "R622") (pin "2") (pinfunction "2_2") (pintype "passive"))
      (node (ref "R623") (pin "1") (pinfunction "1_1") (pintype "passive"))
    )
    (net (code "590") (name "Net-(R623-Pad2)") (class "Default")
      (node (ref "R623") (pin "2") (pinfunction "2_2") (pintype "passive"))
      (node (ref "R624") (pin "1") (pinfunction "1_1") (pintype "passive"))
    )
    (net (code "591") (name "Net-(R624-Pad2)") (class "Default")
      (node (ref "R624") (pin "2") (pinfunction "2_2") (pintype "passive"))
      (node (ref "R625") (pin "1") (pinfunction "1_1") (pintype "passive"))
    )
    (net (code "592") (name "Net-(R625-Pad2)") (class "Default")
      (node (ref "R625") (pin "2") (pinfunction "2_2") (pintype "passive"))
      (node (ref "R626") (pin "1") (pinfunction "1_1") (pintype "passive"))
    )
    (net (code "593") (name "Net-(R626-Pad2)") (class "Default")
      (node (ref "R626") (pin "2") (pinfunction "2_2") (pintype "passive"))
      (node (ref "R627") (pin "1") (pinfunction "1_1") (pintype "passive"))
    )
    (net (code "594") (name "Net-(R627-Pad2)") (class "Default")
      (node (ref "R627") (pin "2") (pinfunction "2_2") (pintype "passive"))
      (node (ref "R628") (pin "1") (pinfunction "1_1") (pintype "passive"))
    )
    (net (code "595") (name "Net-(R628-Pad2)") (class "Default")
      (node (ref "R628") (pin "2") (pinfunction "2_2") (pintype "passive"))
      (node (ref "R629") (pin "1") (pinfunction "1_1") (pintype "passive"))
    )
    (net (code "596") (name "Net-(R629-Pad2)") (class "Default")
      (node (ref "R629") (pin "2") (pinfunction "2_2") (pintype "passive"))
      (node (ref "R630") (pin "1") (pinfunction "1_1") (pintype "passive"))
    )
    (net (code "597") (name "Net-(R630-Pad2)") (class "Default")
      (node (ref "R630") (pin "2") (pinfunction "2_2") (pintype "passive"))
      (node (ref "R631") (pin "1") (pinfunction "1_1") (pintype "passive"))
    )
    (net (code "598") (name "Net-(R631-Pad2)") (class "Default")
      (node (ref "R631") (pin "2") (pinfunction "2_2") (pintype "passive"))
      (node (ref "R632") (pin "1") (pinfunction "1_1") (pintype "passive"))
    )
    (net (code "599") (name "Net-(R632-Pad2)") (class "Default")
      (node (ref "R632") (pin "2") (pinfunction "2_2") (pintype "passive"))
      (node (ref "R633") (pin "1") (pinfunction "1_1") (pintype "passive"))
    )
    (net (code "600") (name "Net-(R633-Pad2)") (class "Default")
      (node (ref "R633") (pin "2") (pinfunction "2_2") (pintype "passive"))
      (node (ref "R634") (pin "1") (pinfunction "1_1") (pintype "passive"))
    )
    (net (code "601") (name "Net-(R634-Pad2)") (class "Default")
      (node (ref "R634") (pin "2") (pinfunction "2_2") (pintype "passive"))
      (node (ref "R635") (pin "1") (pinfunction "1_1") (pintype "passive"))
    )
    (net (code "602") (name "Net-(R635-Pad2)") (class "Default")
      (node (ref "R635") (pin "2") (pinfunction "2_2") (pintype "passive"))
      (node (ref "R636") (pin "1") (pinfunction "1_1") (pintype "passive"))
    )
    (net (code "603") (name "Net-(R636-Pad2)") (class "Default")
      (node (ref "R636") (pin "2") (pinfunction "2_2") (pintype "passive"))
      (node (ref "R637") (pin "1") (pinfunction "1_1") (pintype "passive"))
    )
    (net (code "604") (name "Net-(R637-Pad2)") (class "Default")
      (node (ref "R637") (pin "2") (pinfunction "2_2") (pintype "passive"))
      (node (ref "R638") (pin "1") (pinfunction "1_1") (pintype "passive"))
    )
    (net (code "605") (name "Net-(R639-Pad2)") (class "Default")
      (node (ref "R639") (pin "2") (pinfunction "2_2") (pintype "passive"))
      (node (ref "R640") (pin "1") (pinfunction "1_1") (pintype "passive"))
    )
    (net (code "606") (name "Net-(R640-Pad2)") (class "Default")
      (node (ref "R640") (pin "2") (pinfunction "2_2") (pintype "passive"))
      (node (ref "R641") (pin "1") (pinfunction "1_1") (pintype "passive"))
    )
    (net (code "607") (name "Net-(R641-Pad2)") (class "Default")
      (node (ref "R641") (pin "2") (pinfunction "2_2") (pintype "passive"))
      (node (ref "R642") (pin "1") (pinfunction "1_1") (pintype "passive"))
    )
    (net (code "608") (name "Net-(R642-Pad2)") (class "Default")
      (node (ref "R642") (pin "2") (pinfunction "2_2") (pintype "passive"))
      (node (ref "R643") (pin "1") (pinfunction "1_1") (pintype "passive"))
    )
    (net (code "609") (name "Net-(R643-Pad2)") (class "Default")
      (node (ref "R643") (pin "2") (pinfunction "2_2") (pintype "passive"))
      (node (ref "R644") (pin "1") (pinfunction "1_1") (pintype "passive"))
    )
    (net (code "610") (name "Net-(R644-Pad2)") (class "Default")
      (node (ref "R644") (pin "2") (pinfunction "2_2") (pintype "passive"))
      (node (ref "R645") (pin "1") (pinfunction "1_1") (pintype "passive"))
    )
    (net (code "611") (name "Net-(R645-Pad2)") (class "Default")
      (node (ref "R645") (pin "2") (pinfunction "2_2") (pintype "passive"))
      (node (ref "R646") (pin "1") (pinfunction "1_1") (pintype "passive"))
    )
    (net (code "612") (name "Net-(R646-Pad2)") (class "Default")
      (node (ref "R646") (pin "2") (pinfunction "2_2") (pintype "passive"))
      (node (ref "R647") (pin "1") (pinfunction "1_1") (pintype "passive"))
    )
    (net (code "613") (name "Net-(R647-Pad2)") (class "Default")
      (node (ref "R647") (pin "2") (pinfunction "2_2") (pintype "passive"))
      (node (ref "R648") (pin "1") (pinfunction "1_1") (pintype "passive"))
    )
    (net (code "614") (name "Net-(R648-Pad2)") (class "Default")
      (node (ref "R648") (pin "2") (pinfunction "2_2") (pintype "passive"))
      (node (ref "R649") (pin "1") (pinfunction "1_1") (pintype "passive"))
    )
    (net (code "615") (name "Net-(R649-Pad2)") (class "Default")
      (node (ref "R649") (pin "2") (pinfunction "2_2") (pintype "passive"))
      (node (ref "R650") (pin "1") (pinfunction "1_1") (pintype "passive"))
    )
    (net (code "616") (name "Net-(R650-Pad2)") (class "Default")
      (node (ref "R650") (pin "2") (pinfunction "2_2") (pintype "passive"))
      (node (ref "R651") (pin "1") (pinfunction "1_1") (pintype "passive"))
    )
    (net (code "617") (name "Net-(R651-Pad2)") (class "Default")
      (node (ref "R651") (pin "2") (pinfunction "2_2") (pintype "passive"))
      (node (ref "R652") (pin "1") (pinfunction "1_1") (pintype "passive"))
    )
    (net (code "618") (name "Net-(R652-Pad2)") (class "Default")
      (node (ref "R652") (pin "2") (pinfunction "2_2") (pintype "passive"))
      (node (ref "R653") (pin "1") (pinfunction "1_1") (pintype "passive"))
    )
    (net (code "619") (name "Net-(R653-Pad2)") (class "Default")
      (node (ref "R653") (pin "2") (pinfunction "2_2") (pintype "passive"))
      (node (ref "R654") (pin "1") (pinfunction "1_1") (pintype "passive"))
    )
    (net (code "620") (name "Net-(R654-Pad2)") (class "Default")
      (node (ref "R654") (pin "2") (pinfunction "2_2") (pintype "passive"))
      (node (ref "R655") (pin "1") (pinfunction "1_1") (pintype "passive"))
    )
    (net (code "621") (name "Net-(R655-Pad2)") (class "Default")
      (node (ref "R655") (pin "2") (pinfunction "2_2") (pintype "passive"))
      (node (ref "R656") (pin "1") (pinfunction "1_1") (pintype "passive"))
    )
    (net (code "622") (name "Net-(R656-Pad2)") (class "Default")
      (node (ref "R656") (pin "2") (pinfunction "2_2") (pintype "passive"))
      (node (ref "R657") (pin "1") (pinfunction "1_1") (pintype "passive"))
    )
    (net (code "623") (name "Net-(R658-Pad2)") (class "Default")
      (node (ref "R658") (pin "2") (pinfunction "2_2") (pintype "passive"))
      (node (ref "R659") (pin "1") (pinfunction "1_1") (pintype "passive"))
    )
    (net (code "624") (name "Net-(R659-Pad2)") (class "Default")
      (node (ref "R659") (pin "2") (pinfunction "2_2") (pintype "passive"))
      (node (ref "R660") (pin "1") (pinfunction "1_1") (pintype "passive"))
    )
    (net (code "625") (name "Net-(R660-Pad2)") (class "Default")
      (node (ref "R660") (pin "2") (pinfunction "2_2") (pintype "passive"))
      (node (ref "R661") (pin "1") (pinfunction "1_1") (pintype "passive"))
    )
    (net (code "626") (name "Net-(R661-Pad2)") (class "Default")
      (node (ref "R661") (pin "2") (pinfunction "2_2") (pintype "passive"))
      (node (ref "R662") (pin "1") (pinfunction "1_1") (pintype "passive"))
    )
    (net (code "627") (name "Net-(R662-Pad2)") (class "Default")
      (node (ref "R662") (pin "2") (pinfunction "2_2") (pintype "passive"))
      (node (ref "R663") (pin "1") (pinfunction "1_1") (pintype "passive"))
    )
    (net (code "628") (name "Net-(R663-Pad2)") (class "Default")
      (node (ref "R663") (pin "2") (pinfunction "2_2") (pintype "passive"))
      (node (ref "R664") (pin "1") (pinfunction "1_1") (pintype "passive"))
    )
    (net (code "629") (name "Net-(R664-Pad2)") (class "Default")
      (node (ref "R664") (pin "2") (pinfunction "2_2") (pintype "passive"))
      (node (ref "R665") (pin "1") (pinfunction "1_1") (pintype "passive"))
    )
    (net (code "630") (name "Net-(R665-Pad2)") (class "Default")
      (node (ref "R665") (pin "2") (pinfunction "2_2") (pintype "passive"))
      (node (ref "R666") (pin "1") (pinfunction "1_1") (pintype "passive"))
    )
    (net (code "631") (name "Net-(R666-Pad2)") (class "Default")
      (node (ref "R666") (pin "2") (pinfunction "2_2") (pintype "passive"))
      (node (ref "R667") (pin "1") (pinfunction "1_1") (pintype "passive"))
    )
    (net (code "632") (name "Net-(R667-Pad2)") (class "Default")
      (node (ref "R667") (pin "2") (pinfunction "2_2") (pintype "passive"))
      (node (ref "R668") (pin "1") (pinfunction "1_1") (pintype "passive"))
    )
    (net (code "633") (name "Net-(R668-Pad2)") (class "Default")
      (node (ref "R668") (pin "2") (pinfunction "2_2") (pintype "passive"))
      (node (ref "R669") (pin "1") (pinfunction "1_1") (pintype "passive"))
    )
    (net (code "634") (name "Net-(R669-Pad2)") (class "Default")
      (node (ref "R669") (pin "2") (pinfunction "2_2") (pintype "passive"))
      (node (ref "R670") (pin "1") (pinfunction "1_1") (pintype "passive"))
    )
    (net (code "635") (name "Net-(R670-Pad2)") (class "Default")
      (node (ref "R670") (pin "2") (pinfunction "2_2") (pintype "passive"))
      (node (ref "R671") (pin "1") (pinfunction "1_1") (pintype "passive"))
    )
    (net (code "636") (name "Net-(R671-Pad2)") (class "Default")
      (node (ref "R671") (pin "2") (pinfunction "2_2") (pintype "passive"))
      (node (ref "R672") (pin "1") (pinfunction "1_1") (pintype "passive"))
    )
    (net (code "637") (name "Net-(R672-Pad2)") (class "Default")
      (node (ref "R672") (pin "2") (pinfunction "2_2") (pintype "passive"))
      (node (ref "R673") (pin "1") (pinfunction "1_1") (pintype "passive"))
    )
    (net (code "638") (name "Net-(R673-Pad2)") (class "Default")
      (node (ref "R673") (pin "2") (pinfunction "2_2") (pintype "passive"))
      (node (ref "R674") (pin "1") (pinfunction "1_1") (pintype "passive"))
    )
    (net (code "639") (name "Net-(R674-Pad2)") (class "Default")
      (node (ref "R674") (pin "2") (pinfunction "2_2") (pintype "passive"))
      (node (ref "R675") (pin "1") (pinfunction "1_1") (pintype "passive"))
    )
    (net (code "640") (name "Net-(R675-Pad2)") (class "Default")
      (node (ref "R675") (pin "2") (pinfunction "2_2") (pintype "passive"))
      (node (ref "R676") (pin "1") (pinfunction "1_1") (pintype "passive"))
    )
    (net (code "641") (name "Net-(R677-Pad2)") (class "Default")
      (node (ref "R677") (pin "2") (pinfunction "2_2") (pintype "passive"))
      (node (ref "R678") (pin "1") (pinfunction "1_1") (pintype "passive"))
    )
    (net (code "642") (name "Net-(R678-Pad2)") (class "Default")
      (node (ref "R678") (pin "2") (pinfunction "2_2") (pintype "passive"))
      (node (ref "R679") (pin "1") (pinfunction "1_1") (pintype "passive"))
    )
    (net (code "643") (name "Net-(R679-Pad2)") (class "Default")
      (node (ref "R679") (pin "2") (pinfunction "2_2") (pintype "passive"))
      (node (ref "R680") (pin "1") (pinfunction "1_1") (pintype "passive"))
    )
    (net (code "644") (name "Net-(R680-Pad2)") (class "Default")
      (node (ref "R680") (pin "2") (pinfunction "2_2") (pintype "passive"))
      (node (ref "R681") (pin "1") (pinfunction "1_1") (pintype "passive"))
    )
    (net (code "645") (name "Net-(R681-Pad2)") (class "Default")
      (node (ref "R681") (pin "2") (pinfunction "2_2") (pintype "passive"))
      (node (ref "R682") (pin "1") (pinfunction "1_1") (pintype "passive"))
    )
    (net (code "646") (name "Net-(R682-Pad2)") (class "Default")
      (node (ref "R682") (pin "2") (pinfunction "2_2") (pintype "passive"))
      (node (ref "R683") (pin "1") (pinfunction "1_1") (pintype "passive"))
    )
    (net (code "647") (name "Net-(R683-Pad2)") (class "Default")
      (node (ref "R683") (pin "2") (pinfunction "2_2") (pintype "passive"))
      (node (ref "R684") (pin "1") (pinfunction "1_1") (pintype "passive"))
    )
    (net (code "648") (name "Net-(R684-Pad2)") (class "Default")
      (node (ref "R684") (pin "2") (pinfunction "2_2") (pintype "passive"))
      (node (ref "R685") (pin "1") (pinfunction "1_1") (pintype "passive"))
    )
    (net (code "649") (name "Net-(R685-Pad2)") (class "Default")
      (node (ref "R685") (pin "2") (pinfunction "2_2") (pintype "passive"))
      (node (ref "R686") (pin "1") (pinfunction "1_1") (pintype "passive"))
    )
    (net (code "650") (name "Net-(R686-Pad2)") (class "Default")
      (node (ref "R686") (pin "2") (pinfunction "2_2") (pintype "passive"))
      (node (ref "R687") (pin "1") (pinfunction "1_1") (pintype "passive"))
    )
    (net (code "651") (name "Net-(R687-Pad2)") (class "Default")
      (node (ref "R687") (pin "2") (pinfunction "2_2") (pintype "passive"))
      (node (ref "R688") (pin "1") (pinfunction "1_1") (pintype "passive"))
    )
    (net (code "652") (name "Net-(R688-Pad2)") (class "Default")
      (node (ref "R688") (pin "2") (pinfunction "2_2") (pintype "passive"))
      (node (ref "R689") (pin "1") (pinfunction "1_1") (pintype "passive"))
    )
    (net (code "653") (name "Net-(R689-Pad2)") (class "Default")
      (node (ref "R689") (pin "2") (pinfunction "2_2") (pintype "passive"))
      (node (ref "R690") (pin "1") (pinfunction "1_1") (pintype "passive"))
    )
    (net (code "654") (name "Net-(R690-Pad2)") (class "Default")
      (node (ref "R690") (pin "2") (pinfunction "2_2") (pintype "passive"))
      (node (ref "R691") (pin "1") (pinfunction "1_1") (pintype "passive"))
    )
    (net (code "655") (name "Net-(R691-Pad2)") (class "Default")
      (node (ref "R691") (pin "2") (pinfunction "2_2") (pintype "passive"))
      (node (ref "R692") (pin "1") (pinfunction "1_1") (pintype "passive"))
    )
    (net (code "656") (name "Net-(R692-Pad2)") (class "Default")
      (node (ref "R692") (pin "2") (pinfunction "2_2") (pintype "passive"))
      (node (ref "R693") (pin "1") (pinfunction "1_1") (pintype "passive"))
    )
    (net (code "657") (name "Net-(R693-Pad2)") (class "Default")
      (node (ref "R693") (pin "2") (pinfunction "2_2") (pintype "passive"))
      (node (ref "R694") (pin "1") (pinfunction "1_1") (pintype "passive"))
    )
    (net (code "658") (name "Net-(R694-Pad2)") (class "Default")
      (node (ref "R694") (pin "2") (pinfunction "2_2") (pintype "passive"))
      (node (ref "R695") (pin "1") (pinfunction "1_1") (pintype "passive"))
    )
    (net (code "659") (name "Net-(R696-Pad2)") (class "Default")
      (node (ref "R696") (pin "2") (pinfunction "2_2") (pintype "passive"))
      (node (ref "R697") (pin "1") (pinfunction "1_1") (pintype "passive"))
    )
    (net (code "660") (name "Net-(R697-Pad2)") (class "Default")
      (node (ref "R697") (pin "2") (pinfunction "2_2") (pintype "passive"))
      (node (ref "R698") (pin "1") (pinfunction "1_1") (pintype "passive"))
    )
    (net (code "661") (name "Net-(R698-Pad2)") (class "Default")
      (node (ref "R698") (pin "2") (pinfunction "2_2") (pintype "passive"))
      (node (ref "R699") (pin "1") (pinfunction "1_1") (pintype "passive"))
    )
    (net (code "662") (name "Net-(R699-Pad2)") (class "Default")
      (node (ref "R699") (pin "2") (pinfunction "2_2") (pintype "passive"))
      (node (ref "R700") (pin "1") (pinfunction "1_1") (pintype "passive"))
    )
    (net (code "663") (name "Net-(R700-Pad2)") (class "Default")
      (node (ref "R700") (pin "2") (pinfunction "2_2") (pintype "passive"))
      (node (ref "R701") (pin "1") (pinfunction "1_1") (pintype "passive"))
    )
    (net (code "664") (name "Net-(R701-Pad2)") (class "Default")
      (node (ref "R701") (pin "2") (pinfunction "2_2") (pintype "passive"))
      (node (ref "R702") (pin "1") (pinfunction "1_1") (pintype "passive"))
    )
    (net (code "665") (name "Net-(R702-Pad2)") (class "Default")
      (node (ref "R702") (pin "2") (pinfunction "2_2") (pintype "passive"))
      (node (ref "R703") (pin "1") (pinfunction "1_1") (pintype "passive"))
    )
    (net (code "666") (name "Net-(R703-Pad2)") (class "Default")
      (node (ref "R703") (pin "2") (pinfunction "2_2") (pintype "passive"))
      (node (ref "R704") (pin "1") (pinfunction "1_1") (pintype "passive"))
    )
    (net (code "667") (name "Net-(R704-Pad2)") (class "Default")
      (node (ref "R704") (pin "2") (pinfunction "2_2") (pintype "passive"))
      (node (ref "R705") (pin "1") (pinfunction "1_1") (pintype "passive"))
    )
    (net (code "668") (name "Net-(R705-Pad2)") (class "Default")
      (node (ref "R705") (pin "2") (pinfunction "2_2") (pintype "passive"))
      (node (ref "R706") (pin "1") (pinfunction "1_1") (pintype "passive"))
    )
    (net (code "669") (name "Net-(R706-Pad2)") (class "Default")
      (node (ref "R706") (pin "2") (pinfunction "2_2") (pintype "passive"))
      (node (ref "R707") (pin "1") (pinfunction "1_1") (pintype "passive"))
    )
    (net (code "670") (name "Net-(R707-Pad2)") (class "Default")
      (node (ref "R707") (pin "2") (pinfunction "2_2") (pintype "passive"))
      (node (ref "R708") (pin "1") (pinfunction "1_1") (pintype "passive"))
    )
    (net (code "671") (name "Net-(R708-Pad2)") (class "Default")
      (node (ref "R708") (pin "2") (pinfunction "2_2") (pintype "passive"))
      (node (ref "R709") (pin "1") (pinfunction "1_1") (pintype "passive"))
    )
    (net (code "672") (name "Net-(R709-Pad2)") (class "Default")
      (node (ref "R709") (pin "2") (pinfunction "2_2") (pintype "passive"))
      (node (ref "R710") (pin "1") (pinfunction "1_1") (pintype "passive"))
    )
    (net (code "673") (name "Net-(R710-Pad2)") (class "Default")
      (node (ref "R710") (pin "2") (pinfunction "2_2") (pintype "passive"))
      (node (ref "R711") (pin "1") (pinfunction "1_1") (pintype "passive"))
    )
    (net (code "674") (name "Net-(R711-Pad2)") (class "Default")
      (node (ref "R711") (pin "2") (pinfunction "2_2") (pintype "passive"))
      (node (ref "R712") (pin "1") (pinfunction "1_1") (pintype "passive"))
    )
    (net (code "675") (name "Net-(TP1-2)") (class "Default")
      (node (ref "R1") (pin "1") (pinfunction "1_1") (pintype "passive"))
      (node (ref "TP1") (pin "1") (pinfunction "2_1") (pintype "passive"))
    )
    (net (code "676") (name "Net-(TP2-2)") (class "Default")
      (node (ref "R17") (pin "2") (pinfunction "2_2") (pintype "passive"))
      (node (ref "R18") (pin "1") (pinfunction "1_1") (pintype "passive"))
      (node (ref "TP2") (pin "1") (pinfunction "2_1") (pintype "passive"))
    )
    (net (code "677") (name "Net-(TP3-2)") (class "Default")
      (node (ref "R36") (pin "2") (pinfunction "2_2") (pintype "passive"))
      (node (ref "R37") (pin "1") (pinfunction "1_1") (pintype "passive"))
      (node (ref "TP3") (pin "1") (pinfunction "2_1") (pintype "passive"))
    )
    (net (code "678") (name "Net-(TP4-2)") (class "Default")
      (node (ref "R55") (pin "2") (pinfunction "2_2") (pintype "passive"))
      (node (ref "R56") (pin "1") (pinfunction "1_1") (pintype "passive"))
      (node (ref "TP4") (pin "1") (pinfunction "2_1") (pintype "passive"))
    )
    (net (code "679") (name "Net-(TP5-2)") (class "Default")
      (node (ref "R74") (pin "2") (pinfunction "2_2") (pintype "passive"))
      (node (ref "R75") (pin "1") (pinfunction "1_1") (pintype "passive"))
      (node (ref "TP5") (pin "1") (pinfunction "2_1") (pintype "passive"))
    )
    (net (code "680") (name "Net-(TP6-2)") (class "Default")
      (node (ref "R93") (pin "2") (pinfunction "2_2") (pintype "passive"))
      (node (ref "R94") (pin "1") (pinfunction "1_1") (pintype "passive"))
      (node (ref "TP6") (pin "1") (pinfunction "2_1") (pintype "passive"))
    )
    (net (code "681") (name "Net-(TP7-2)") (class "Default")
      (node (ref "R112") (pin "2") (pinfunction "2_2") (pintype "passive"))
      (node (ref "R113") (pin "1") (pinfunction "1_1") (pintype "passive"))
      (node (ref "TP7") (pin "1") (pinfunction "2_1") (pintype "passive"))
    )
    (net (code "682") (name "Net-(TP8-2)") (class "Default")
      (node (ref "R131") (pin "2") (pinfunction "2_2") (pintype "passive"))
      (node (ref "R132") (pin "1") (pinfunction "1_1") (pintype "passive"))
      (node (ref "TP8") (pin "1") (pinfunction "2_1") (pintype "passive"))
    )
    (net (code "683") (name "Net-(TP9-2)") (class "Default")
      (node (ref "R150") (pin "2") (pinfunction "2_2") (pintype "passive"))
      (node (ref "R151") (pin "1") (pinfunction "1_1") (pintype "passive"))
      (node (ref "TP9") (pin "1") (pinfunction "2_1") (pintype "passive"))
    )
    (net (code "684") (name "Net-(TP10-2)") (class "Default")
      (node (ref "R169") (pin "2") (pinfunction "2_2") (pintype "passive"))
      (node (ref "R170") (pin "1") (pinfunction "1_1") (pintype "passive"))
      (node (ref "TP10") (pin "1") (pinfunction "2_1") (pintype "passive"))
    )
    (net (code "685") (name "Net-(TP11-2)") (class "Default")
      (node (ref "R188") (pin "2") (pinfunction "2_2") (pintype "passive"))
      (node (ref "R189") (pin "1") (pinfunction "1_1") (pintype "passive"))
      (node (ref "TP11") (pin "1") (pinfunction "2_1") (pintype "passive"))
    )
    (net (code "686") (name "Net-(TP12-2)") (class "Default")
      (node (ref "R207") (pin "2") (pinfunction "2_2") (pintype "passive"))
      (node (ref "R208") (pin "1") (pinfunction "1_1") (pintype "passive"))
      (node (ref "TP12") (pin "1") (pinfunction "2_1") (pintype "passive"))
    )
    (net (code "687") (name "Net-(TP13-2)") (class "Default")
      (node (ref "R226") (pin "2") (pinfunction "2_2") (pintype "passive"))
      (node (ref "R227") (pin "1") (pinfunction "1_1") (pintype "passive"))
      (node (ref "TP13") (pin "1") (pinfunction "2_1") (pintype "passive"))
    )
    (net (code "688") (name "Net-(TP14-2)") (class "Default")
      (node (ref "R245") (pin "2") (pinfunction "2_2") (pintype "passive"))
      (node (ref "R246") (pin "1") (pinfunction "1_1") (pintype "passive"))
      (node (ref "TP14") (pin "1") (pinfunction "2_1") (pintype "passive"))
    )
    (net (code "689") (name "Net-(TP15-2)") (class "Default")
      (node (ref "R264") (pin "2") (pinfunction "2_2") (pintype "passive"))
      (node (ref "R265") (pin "1") (pinfunction "1_1") (pintype "passive"))
      (node (ref "TP15") (pin "1") (pinfunction "2_1") (pintype "passive"))
    )
    (net (code "690") (name "Net-(TP16-2)") (class "Default")
      (node (ref "R283") (pin "2") (pinfunction "2_2") (pintype "passive"))
      (node (ref "R284") (pin "1") (pinfunction "1_1") (pintype "passive"))
      (node (ref "TP16") (pin "1") (pinfunction "2_1") (pintype "passive"))
    )
    (net (code "691") (name "Net-(TP17-2)") (class "Default")
      (node (ref "R302") (pin "2") (pinfunction "2_2") (pintype "passive"))
      (node (ref "R303") (pin "1") (pinfunction "1_1") (pintype "passive"))
      (node (ref "TP17") (pin "1") (pinfunction "2_1") (pintype "passive"))
    )
    (net (code "692") (name "Net-(TP18-2)") (class "Default")
      (node (ref "R321") (pin "2") (pinfunction "2_2") (pintype "passive"))
      (node (ref "R322") (pin "1") (pinfunction "1_1") (pintype "passive"))
      (node (ref "TP18") (pin "1") (pinfunction "2_1") (pintype "passive"))
    )
    (net (code "693") (name "Net-(TP19-2)") (class "Default")
      (node (ref "R340") (pin "2") (pinfunction "2_2") (pintype "passive"))
      (node (ref "R341") (pin "1") (pinfunction "1_1") (pintype "passive"))
      (node (ref "TP19") (pin "1") (pinfunction "2_1") (pintype "passive"))
    )
    (net (code "694") (name "Net-(TP20-2)") (class "Default")
      (node (ref "R357") (pin "2") (pinfunction "2_2") (pintype "passive"))
      (node (ref "TP20") (pin "1") (pinfunction "2_1") (pintype "passive"))
    )
    (net (code "695") (name "Net-(TP21-2)") (class "Default")
      (node (ref "R179") (pin "1") (pinfunction "1_1") (pintype "passive"))
      (node (ref "TP21") (pin "1") (pinfunction "2_1") (pintype "passive"))
    )
    (net (code "696") (name "Net-(TP22-2)") (class "Default")
      (node (ref "R373") (pin "2") (pinfunction "2_2") (pintype "passive"))
      (node (ref "R374") (pin "1") (pinfunction "1_1") (pintype "passive"))
      (node (ref "TP22") (pin "1") (pinfunction "2_1") (pintype "passive"))
    )
    (net (code "697") (name "Net-(TP23-2)") (class "Default")
      (node (ref "R392") (pin "2") (pinfunction "2_2") (pintype "passive"))
      (node (ref "R393") (pin "1") (pinfunction "1_1") (pintype "passive"))
      (node (ref "TP23") (pin "1") (pinfunction "2_1") (pintype "passive"))
    )
    (net (code "698") (name "Net-(TP24-2)") (class "Default")
      (node (ref "R411") (pin "2") (pinfunction "2_2") (pintype "passive"))
      (node (ref "R412") (pin "1") (pinfunction "1_1") (pintype "passive"))
      (node (ref "TP24") (pin "1") (pinfunction "2_1") (pintype "passive"))
    )
    (net (code "699") (name "Net-(TP25-2)") (class "Default")
      (node (ref "R430") (pin "2") (pinfunction "2_2") (pintype "passive"))
      (node (ref "R431") (pin "1") (pinfunction "1_1") (pintype "passive"))
      (node (ref "TP25") (pin "1") (pinfunction "2_1") (pintype "passive"))
    )
    (net (code "700") (name "Net-(TP26-2)") (class "Default")
      (node (ref "R449") (pin "2") (pinfunction "2_2") (pintype "passive"))
      (node (ref "R450") (pin "1") (pinfunction "1_1") (pintype "passive"))
      (node (ref "TP26") (pin "1") (pinfunction "2_1") (pintype "passive"))
    )
    (net (code "701") (name "Net-(TP27-2)") (class "Default")
      (node (ref "R468") (pin "2") (pinfunction "2_2") (pintype "passive"))
      (node (ref "R469") (pin "1") (pinfunction "1_1") (pintype "passive"))
      (node (ref "TP27") (pin "1") (pinfunction "2_1") (pintype "passive"))
    )
    (net (code "702") (name "Net-(TP28-2)") (class "Default")
      (node (ref "R487") (pin "2") (pinfunction "2_2") (pintype "passive"))
      (node (ref "R488") (pin "1") (pinfunction "1_1") (pintype "passive"))
      (node (ref "TP28") (pin "1") (pinfunction "2_1") (pintype "passive"))
    )
    (net (code "703") (name "Net-(TP29-2)") (class "Default")
      (node (ref "R506") (pin "2") (pinfunction "2_2") (pintype "passive"))
      (node (ref "R507") (pin "1") (pinfunction "1_1") (pintype "passive"))
      (node (ref "TP29") (pin "1") (pinfunction "2_1") (pintype "passive"))
    )
    (net (code "704") (name "Net-(TP30-2)") (class "Default")
      (node (ref "R525") (pin "2") (pinfunction "2_2") (pintype "passive"))
      (node (ref "R526") (pin "1") (pinfunction "1_1") (pintype "passive"))
      (node (ref "TP30") (pin "1") (pinfunction "2_1") (pintype "passive"))
    )
    (net (code "705") (name "Net-(TP31-2)") (class "Default")
      (node (ref "R543") (pin "2") (pinfunction "2_2") (pintype "passive"))
      (node (ref "R544") (pin "1") (pinfunction "1_1") (pintype "passive"))
      (node (ref "TP31") (pin "1") (pinfunction "2_1") (pintype "passive"))
    )
    (net (code "706") (name "Net-(TP32-2)") (class "Default")
      (node (ref "R562") (pin "2") (pinfunction "2_2") (pintype "passive"))
      (node (ref "R563") (pin "1") (pinfunction "1_1") (pintype "passive"))
      (node (ref "TP32") (pin "1") (pinfunction "2_1") (pintype "passive"))
    )
    (net (code "707") (name "Net-(TP33-2)") (class "Default")
      (node (ref "R581") (pin "2") (pinfunction "2_2") (pintype "passive"))
      (node (ref "R582") (pin "1") (pinfunction "1_1") (pintype "passive"))
      (node (ref "TP33") (pin "1") (pinfunction "2_1") (pintype "passive"))
    )
    (net (code "708") (name "Net-(TP34-2)") (class "Default")
      (node (ref "R600") (pin "2") (pinfunction "2_2") (pintype "passive"))
      (node (ref "R601") (pin "1") (pinfunction "1_1") (pintype "passive"))
      (node (ref "TP34") (pin "1") (pinfunction "2_1") (pintype "passive"))
    )
    (net (code "709") (name "Net-(TP35-2)") (class "Default")
      (node (ref "R619") (pin "2") (pinfunction "2_2") (pintype "passive"))
      (node (ref "R620") (pin "1") (pinfunction "1_1") (pintype "passive"))
      (node (ref "TP35") (pin "1") (pinfunction "2_1") (pintype "passive"))
    )
    (net (code "710") (name "Net-(TP36-2)") (class "Default")
      (node (ref "R638") (pin "2") (pinfunction "2_2") (pintype "passive"))
      (node (ref "R639") (pin "1") (pinfunction "1_1") (pintype "passive"))
      (node (ref "TP36") (pin "1") (pinfunction "2_1") (pintype "passive"))
    )
    (net (code "711") (name "Net-(TP37-2)") (class "Default")
      (node (ref "R657") (pin "2") (pinfunction "2_2") (pintype "passive"))
      (node (ref "R658") (pin "1") (pinfunction "1_1") (pintype "passive"))
      (node (ref "TP37") (pin "1") (pinfunction "2_1") (pintype "passive"))
    )
    (net (code "712") (name "Net-(TP38-2)") (class "Default")
      (node (ref "R676") (pin "2") (pinfunction "2_2") (pintype "passive"))
      (node (ref "R677") (pin "1") (pinfunction "1_1") (pintype "passive"))
      (node (ref "TP38") (pin "1") (pinfunction "2_1") (pintype "passive"))
    )
    (net (code "713") (name "Net-(TP39-2)") (class "Default")
      (node (ref "R695") (pin "2") (pinfunction "2_2") (pintype "passive"))
      (node (ref "R696") (pin "1") (pinfunction "1_1") (pintype "passive"))
      (node (ref "TP39") (pin "1") (pinfunction "2_1") (pintype "passive"))
    )
    (net (code "714") (name "Net-(TP40-2)") (class "Default")
      (node (ref "R712") (pin "2") (pinfunction "2_2") (pintype "passive"))
      (node (ref "TP40") (pin "1") (pinfunction "2_1") (pintype "passive"))
    )
  )
)
